# PX4FMUv2_4_6.net
KiCad netlist of a schematic drawn in EAGLE
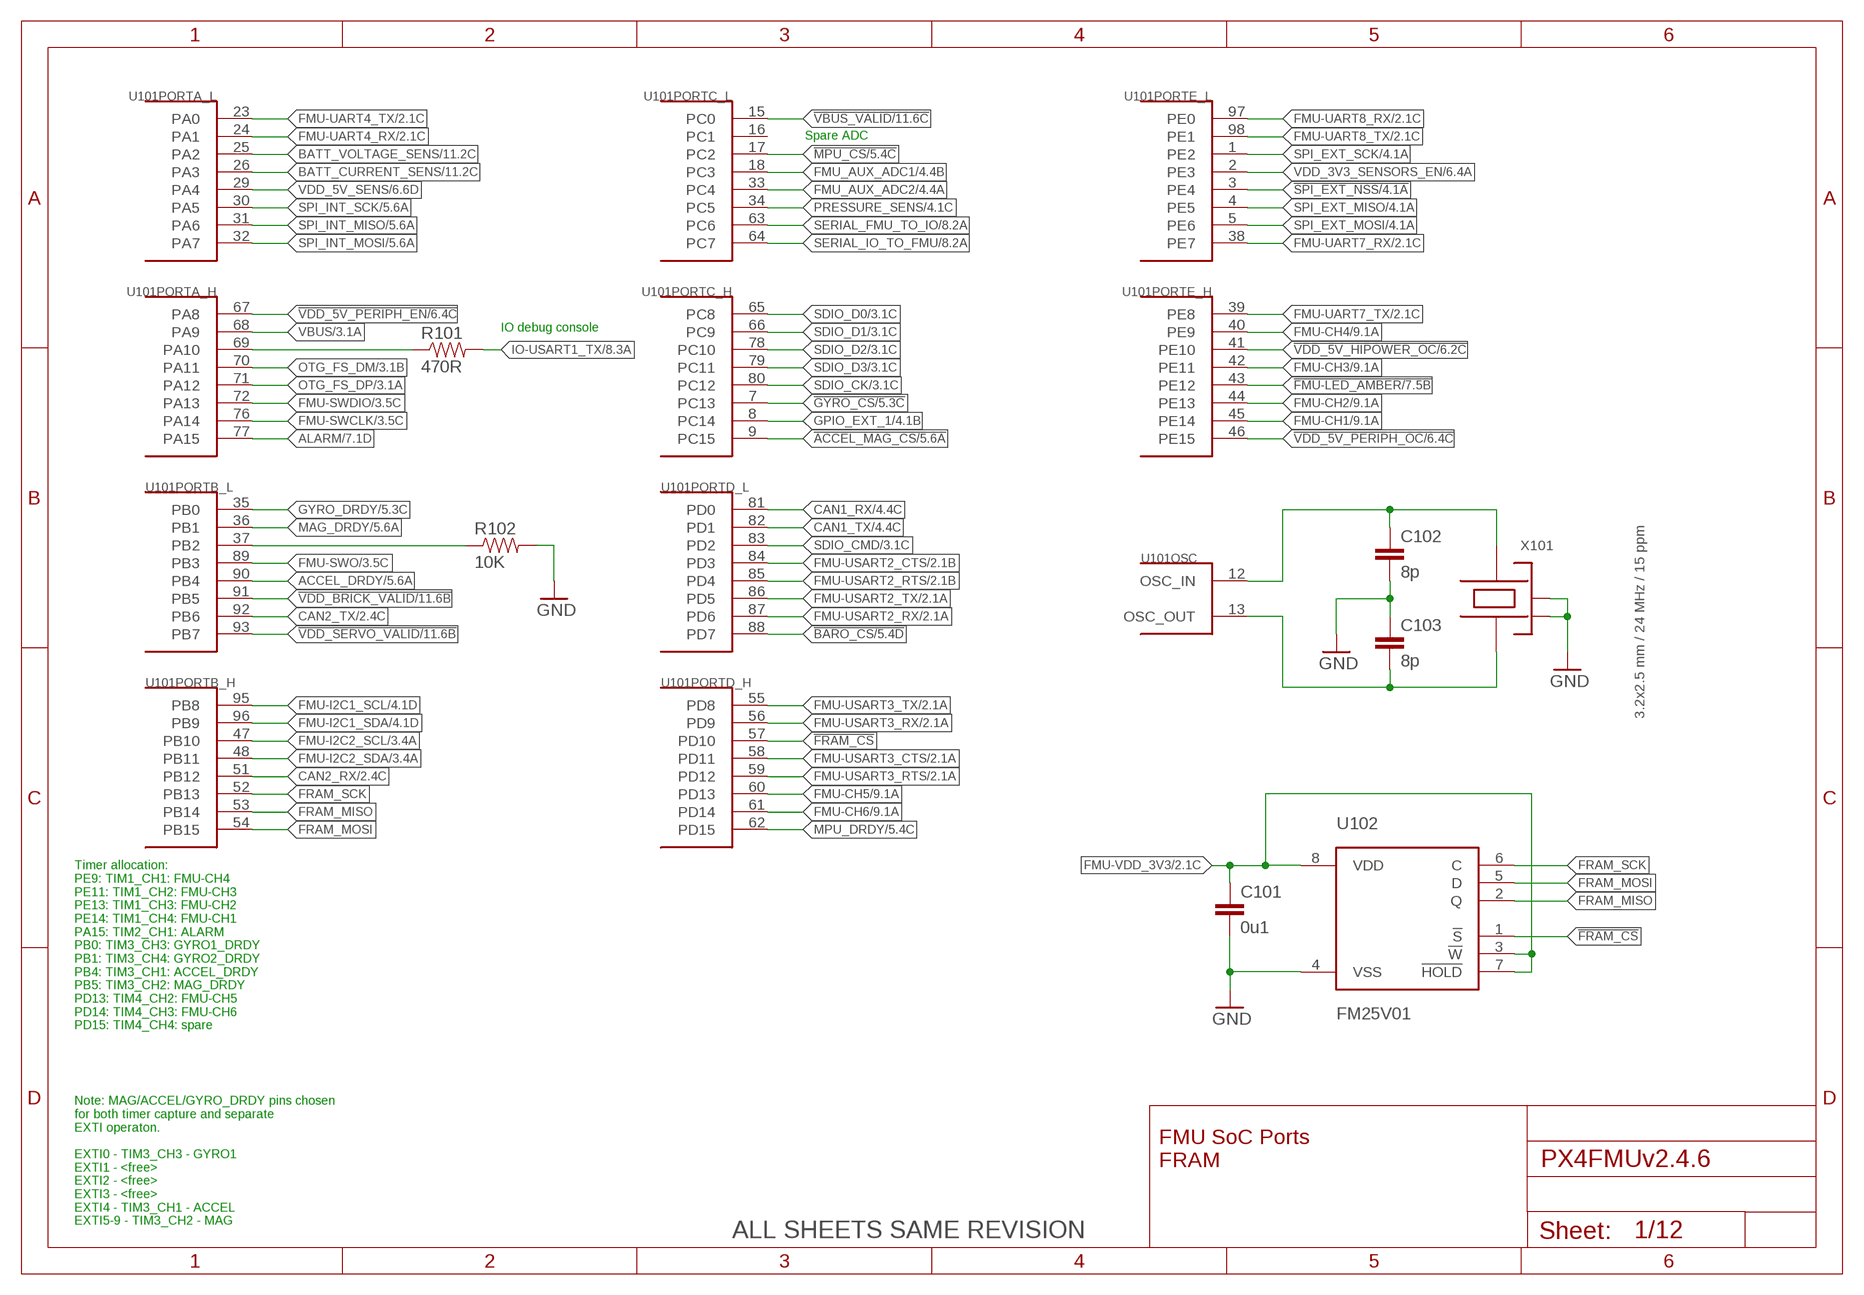
[diagram p0: schematic, sheet 1]
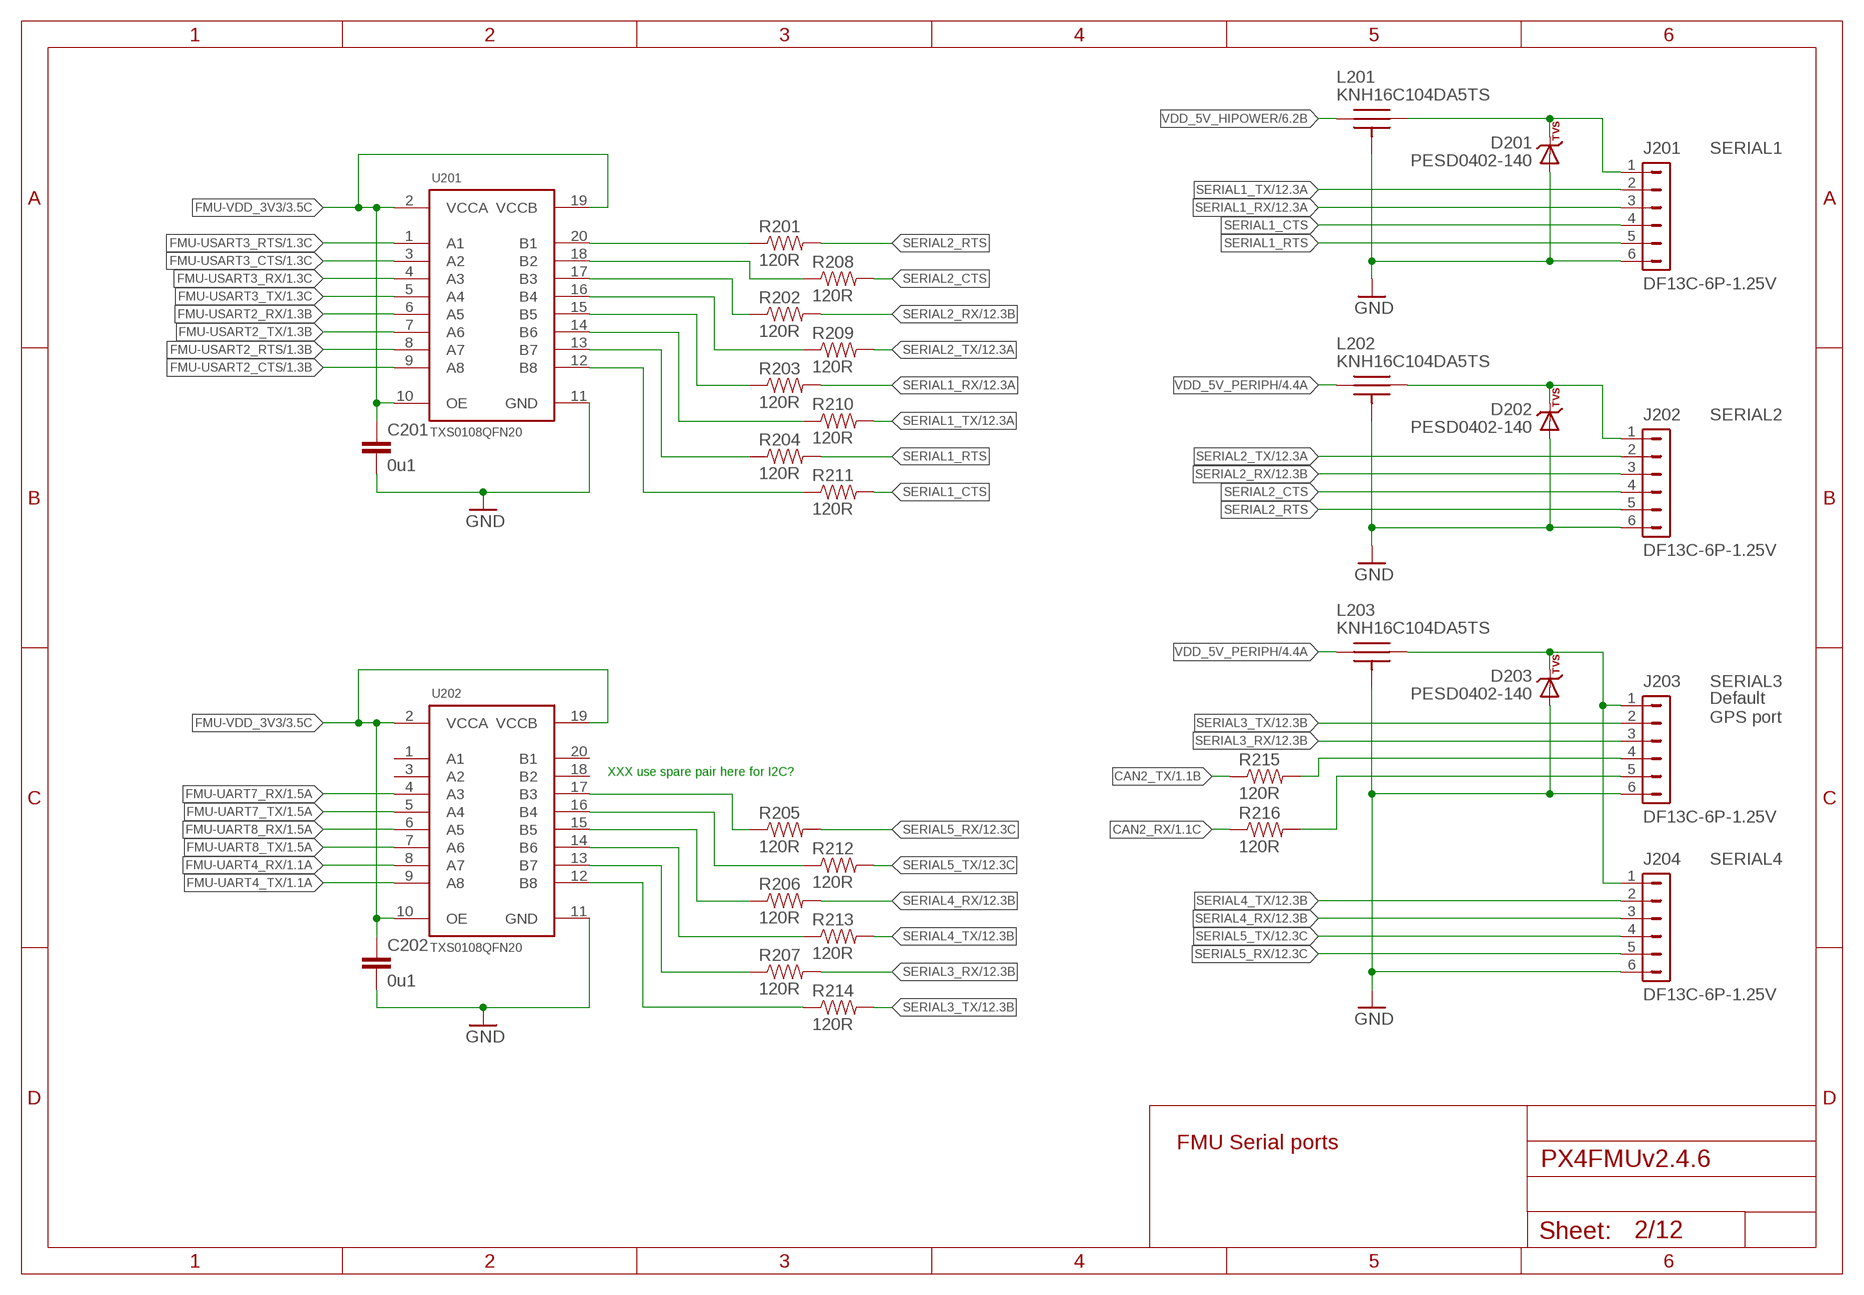
[diagram p1: schematic, sheet 2]
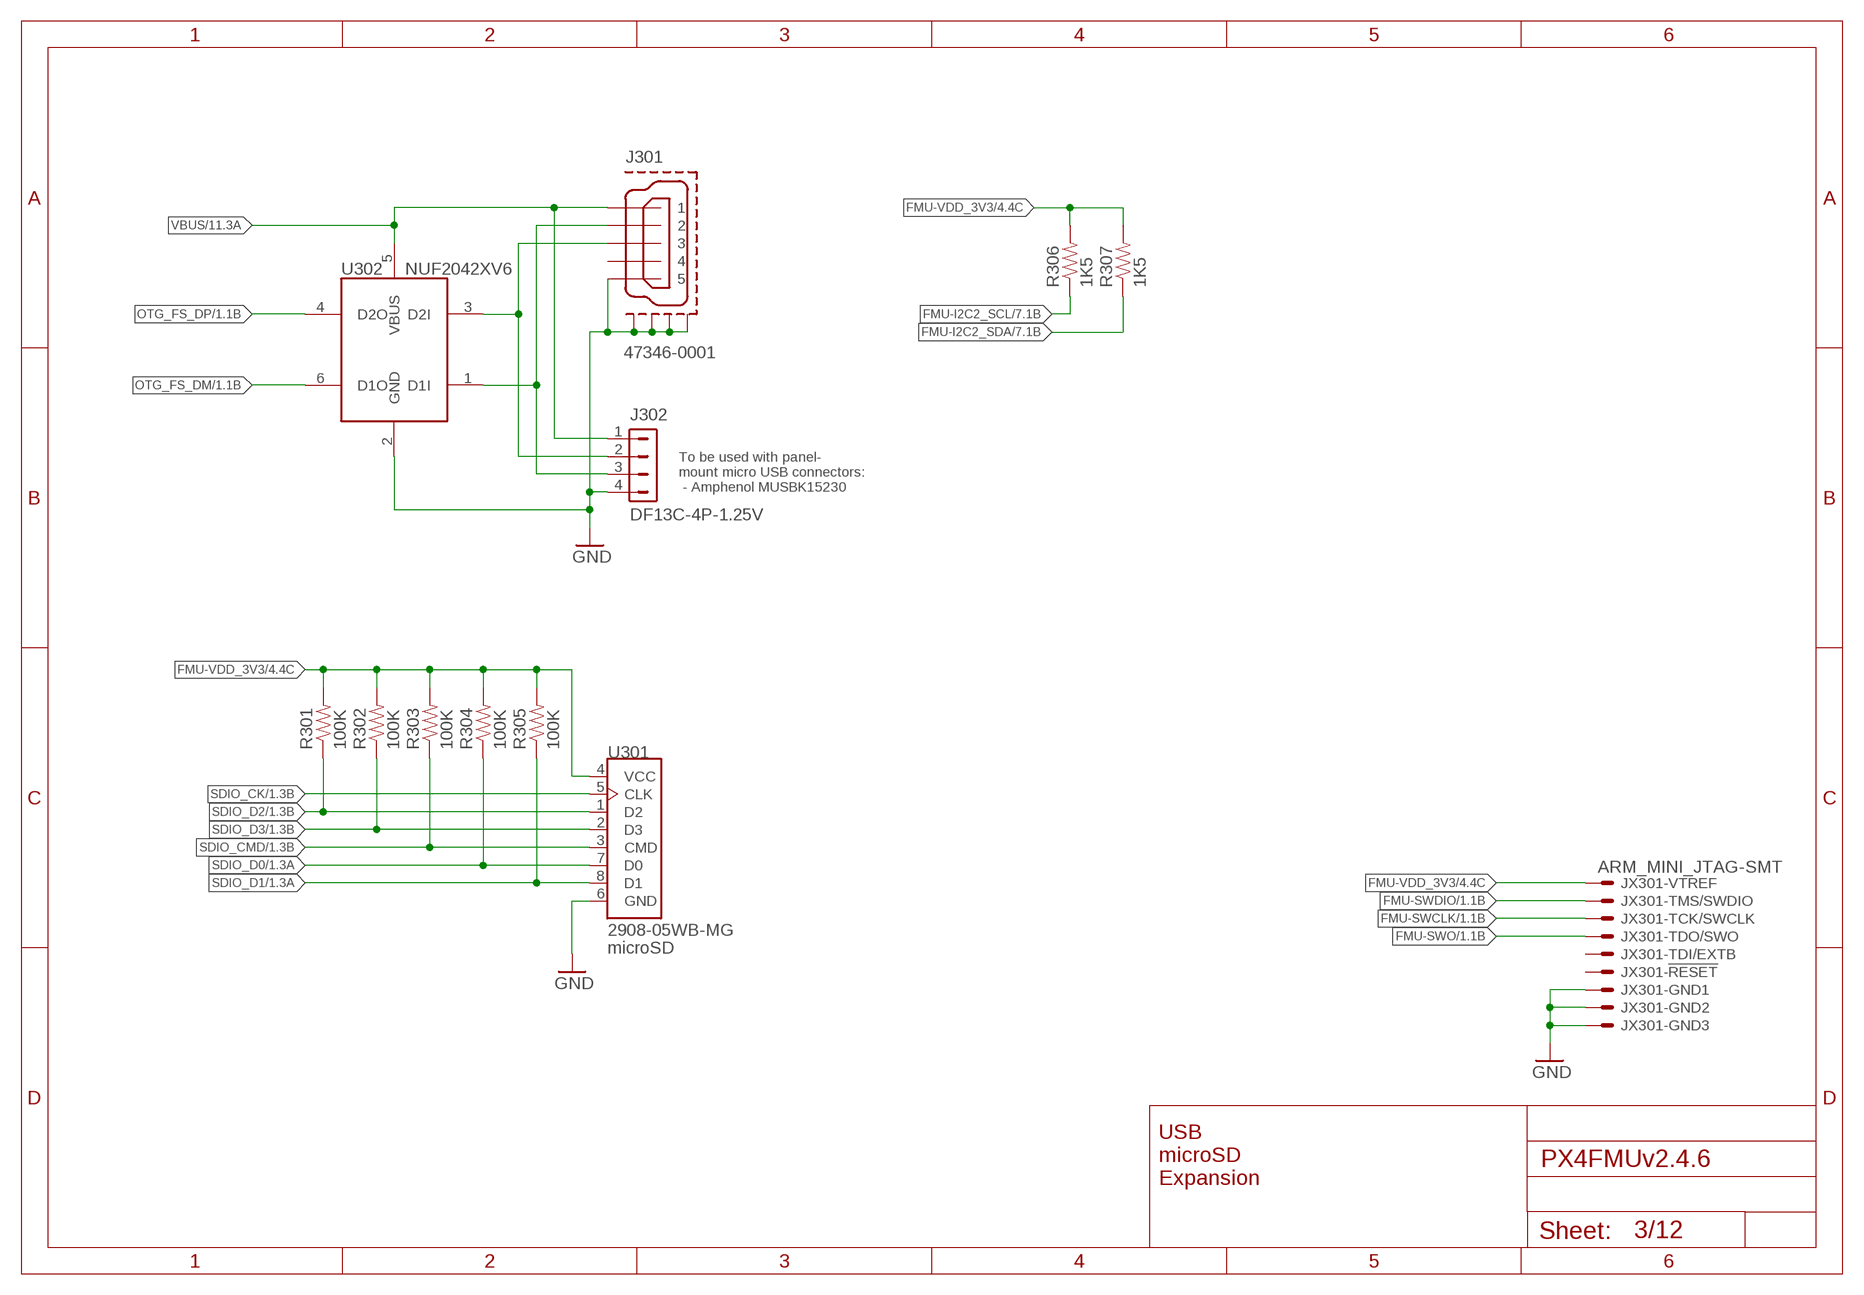
[diagram p2: schematic, sheet 3]
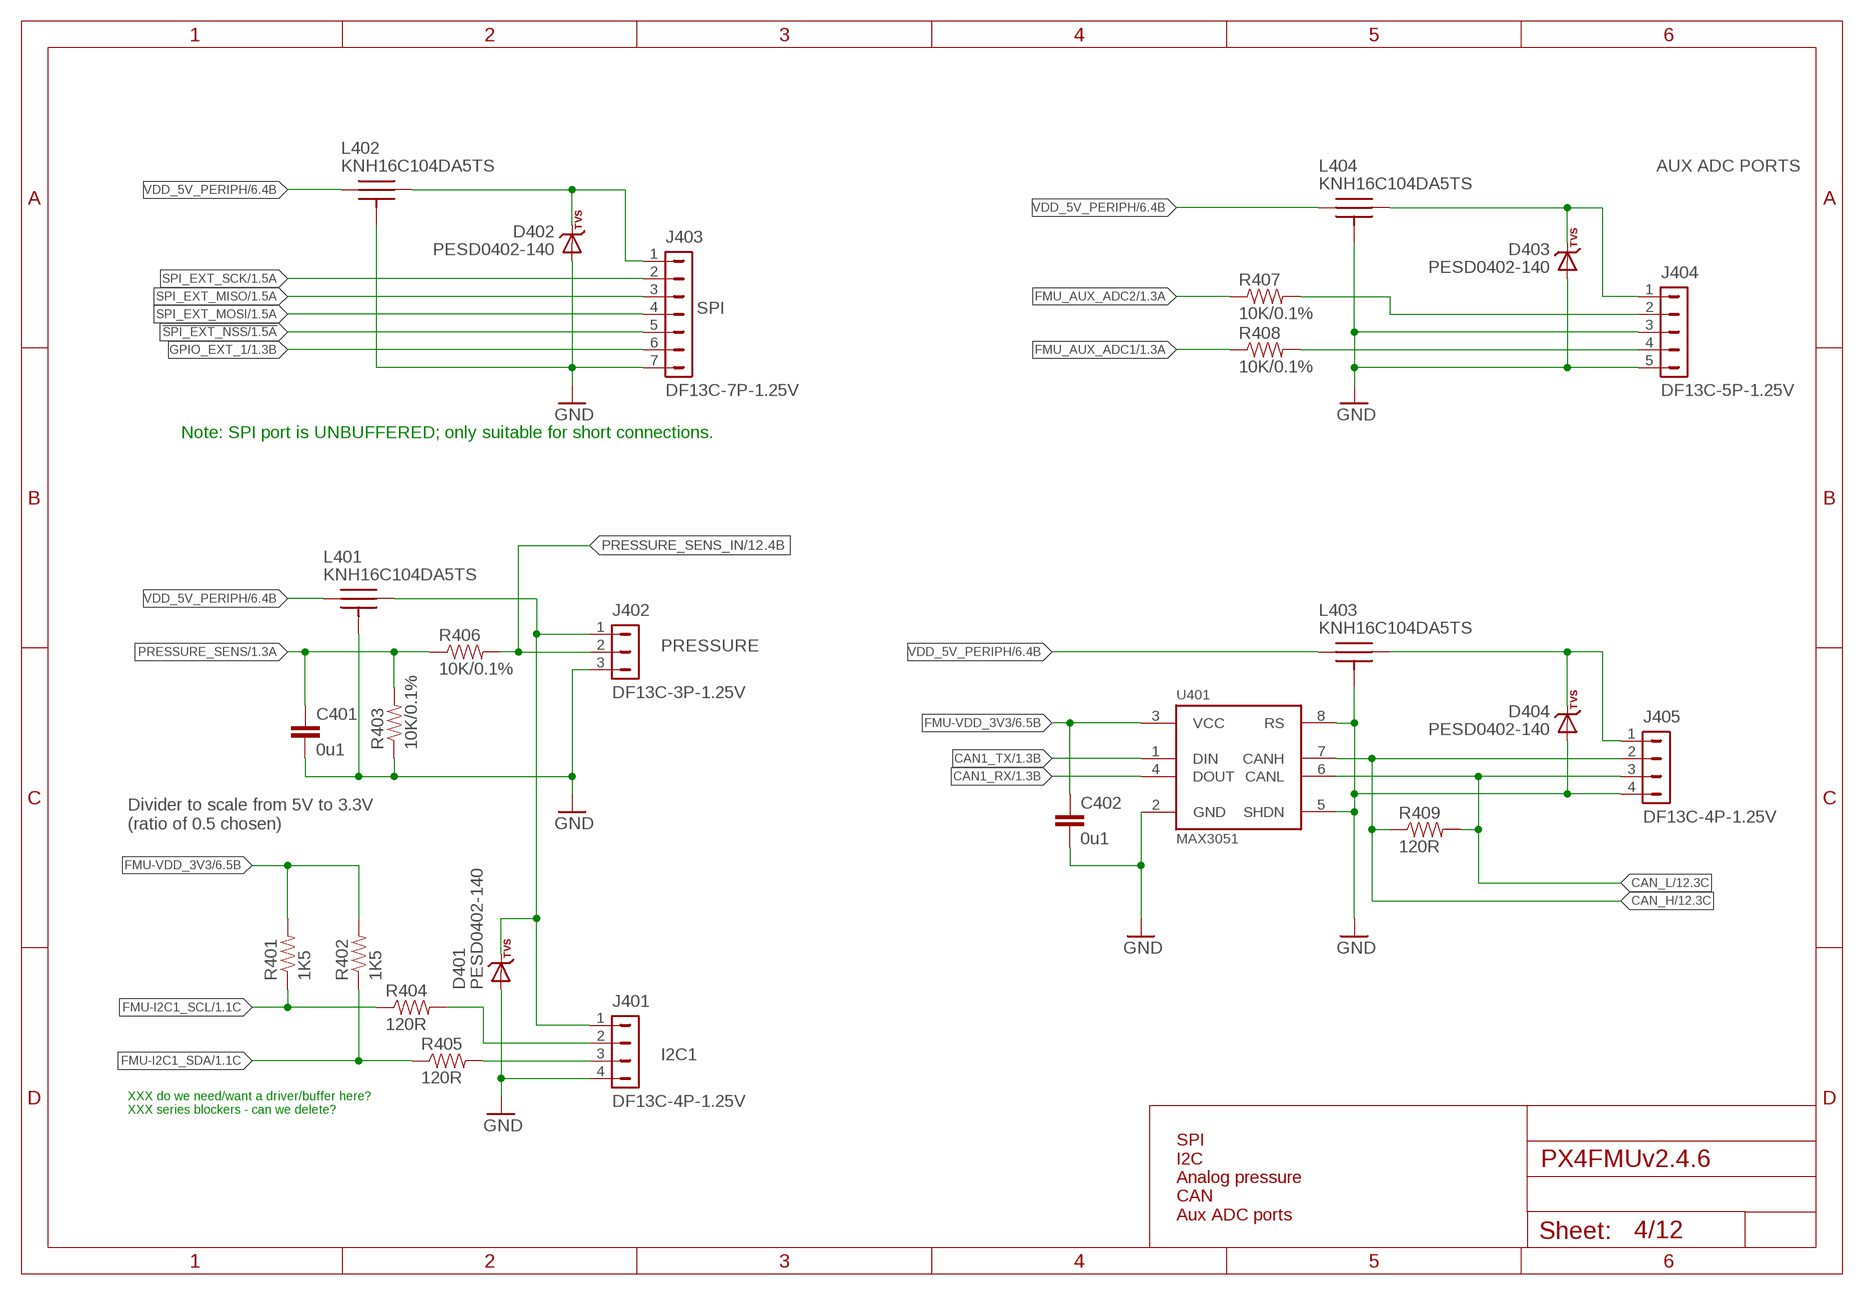
[diagram p3: schematic, sheet 4]
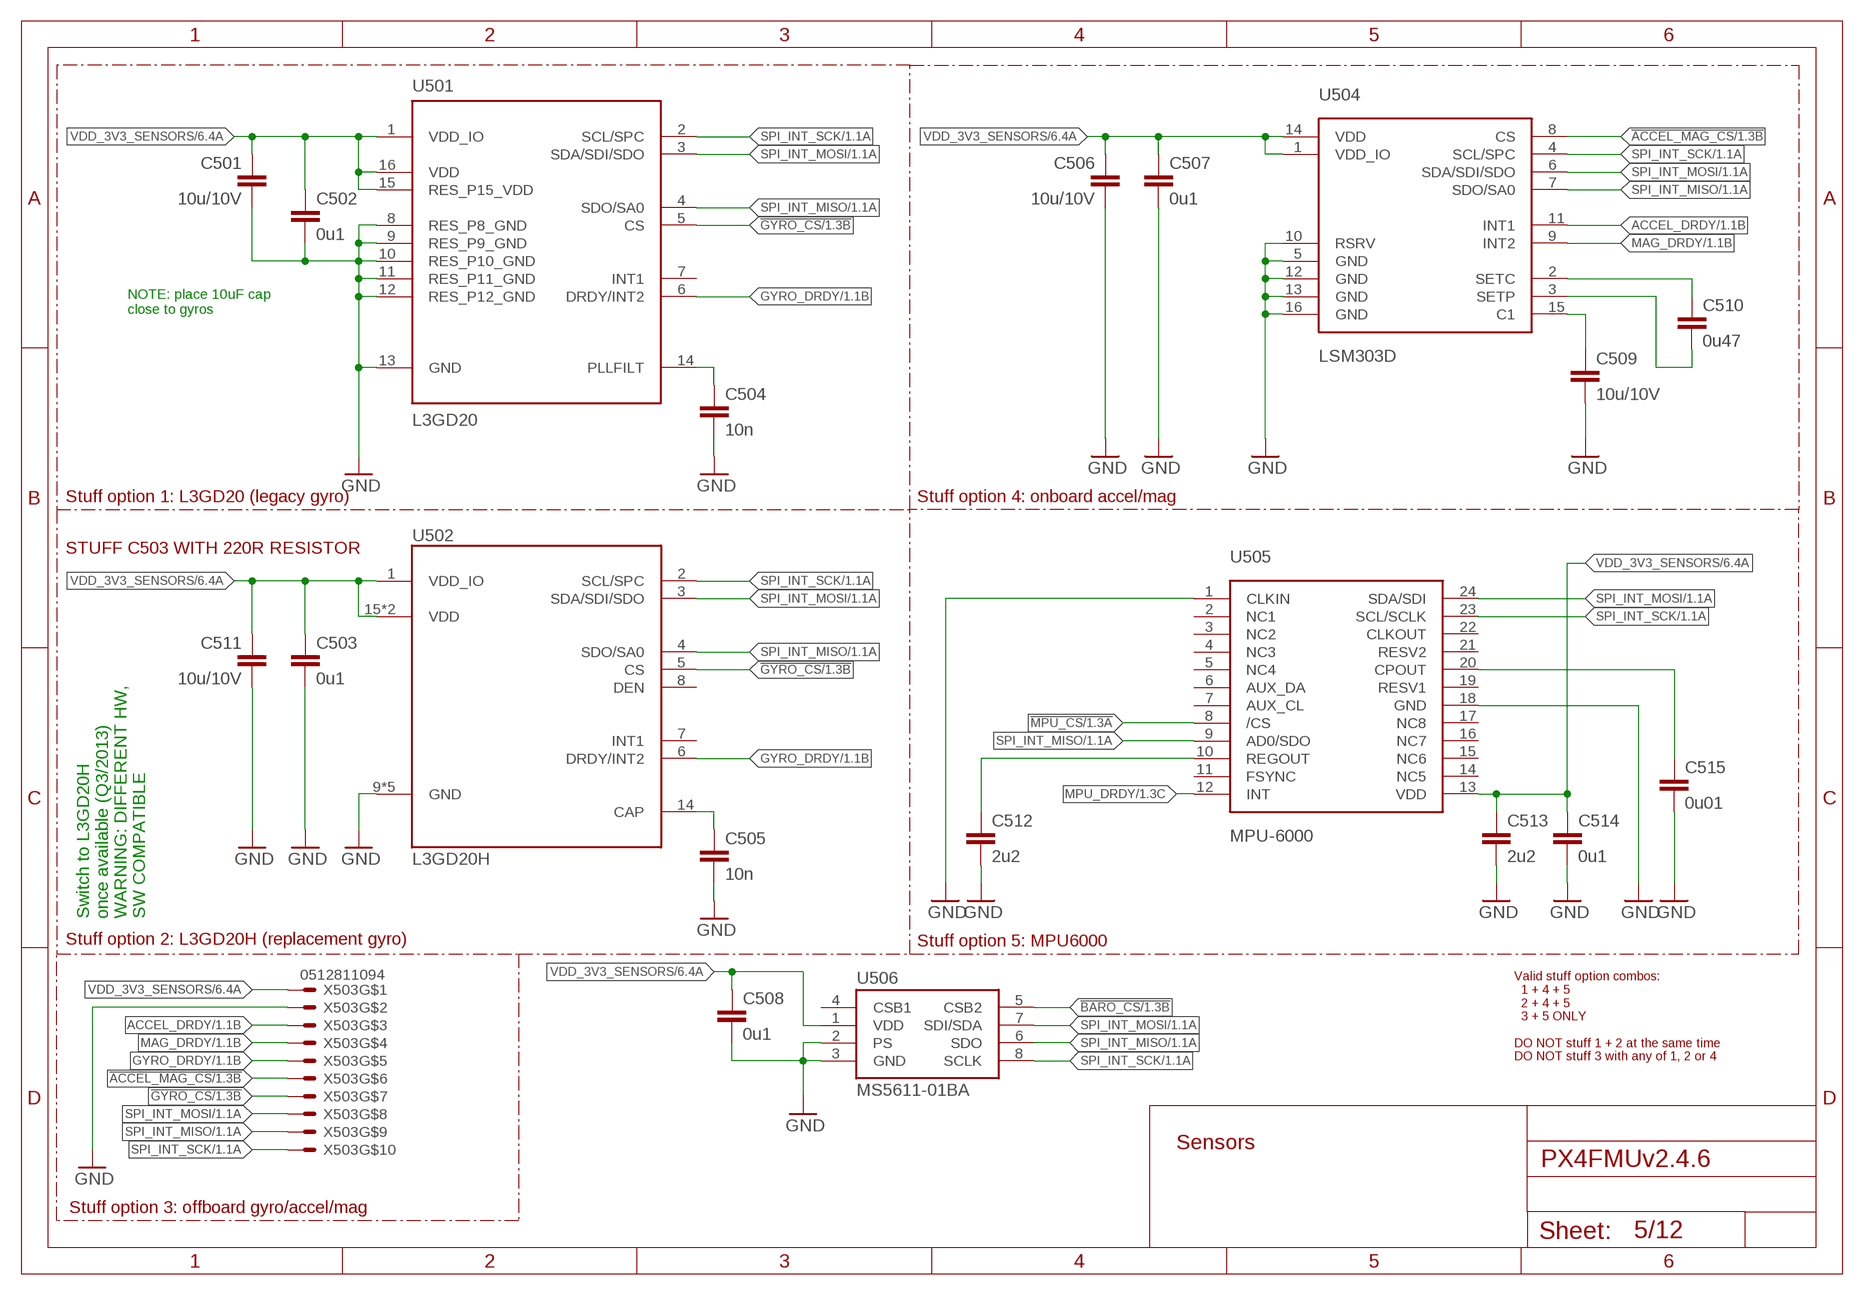
[diagram p4: schematic, sheet 5]
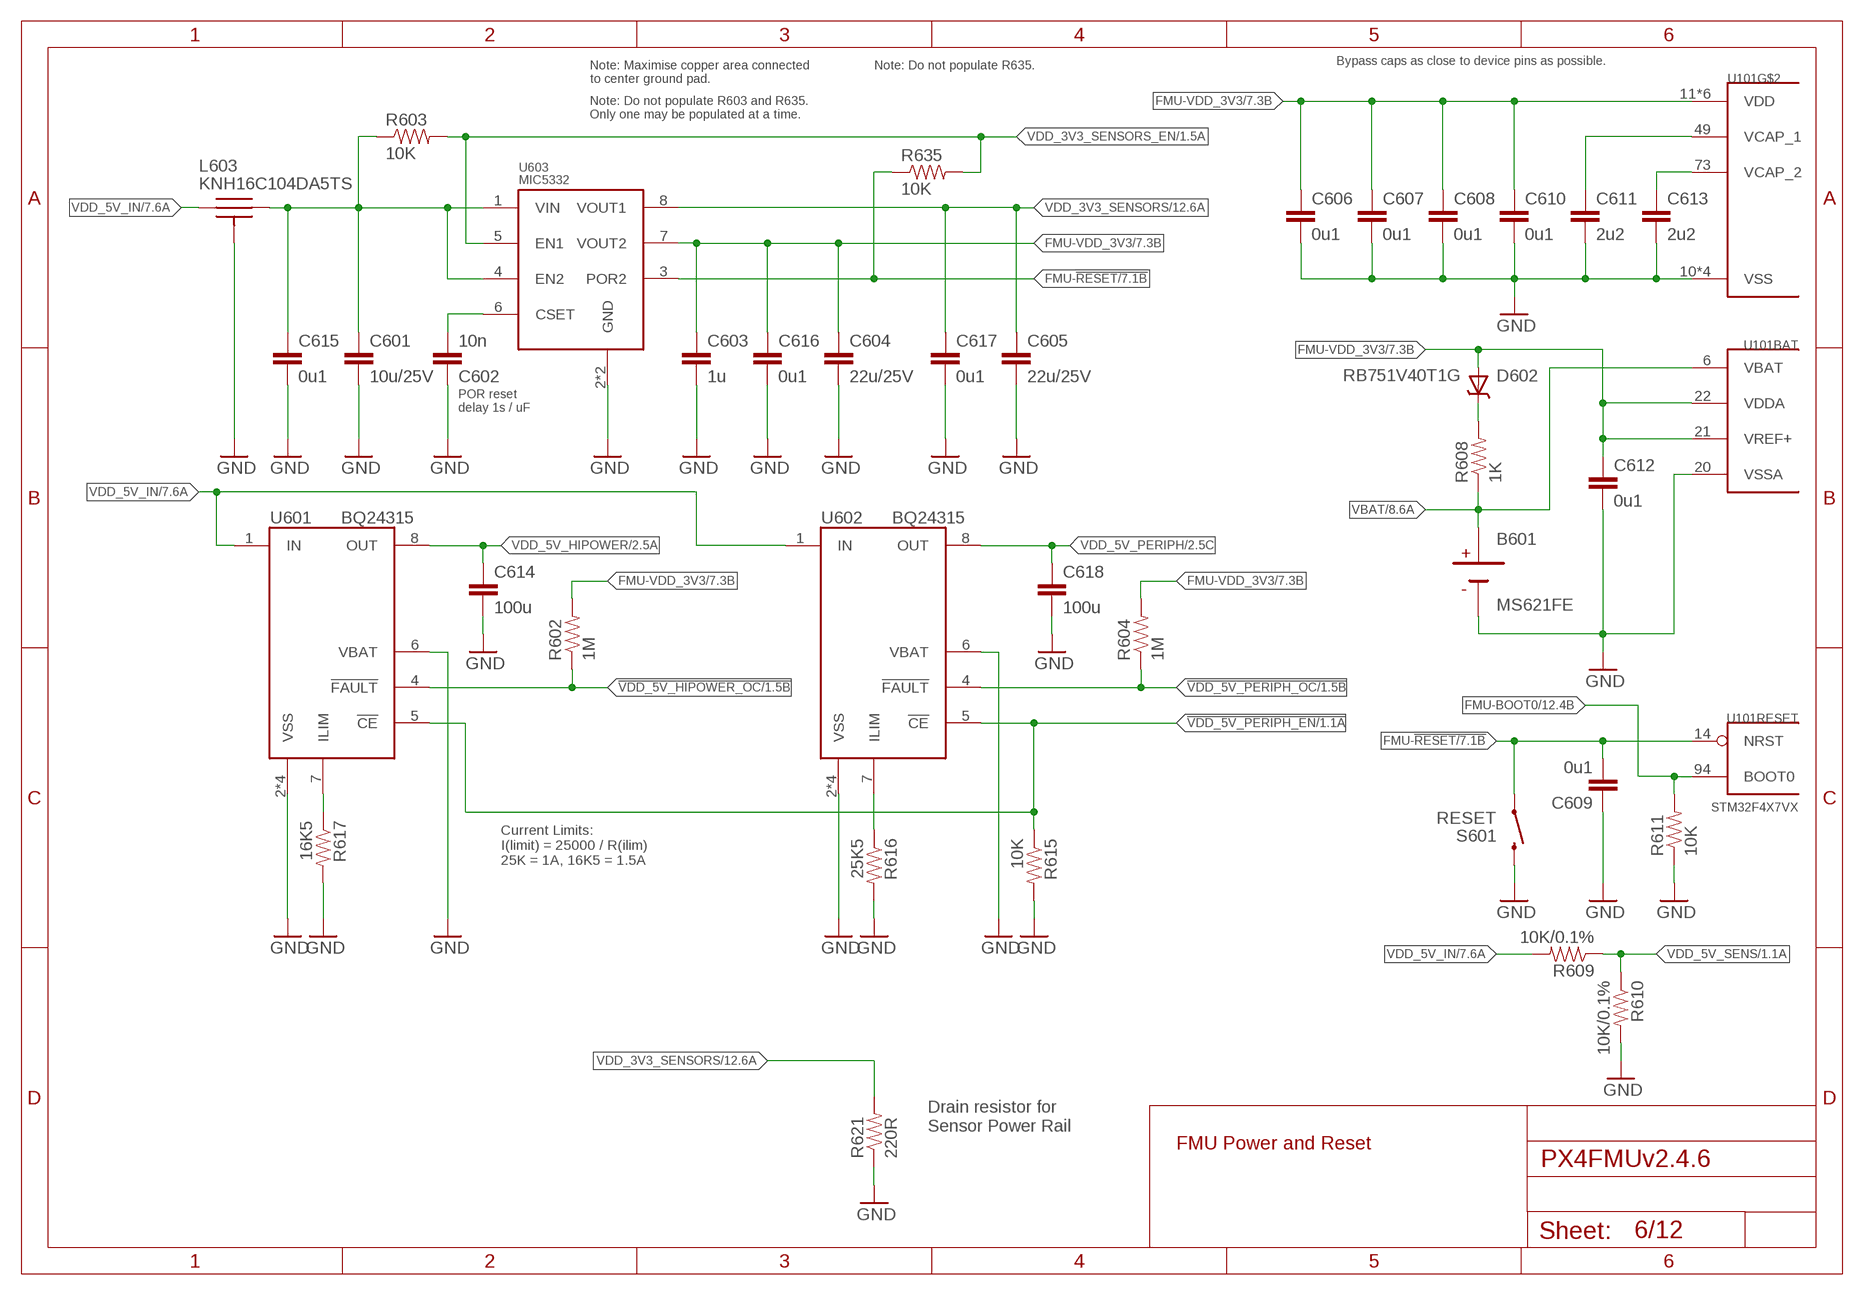
[diagram p5: schematic, sheet 6]
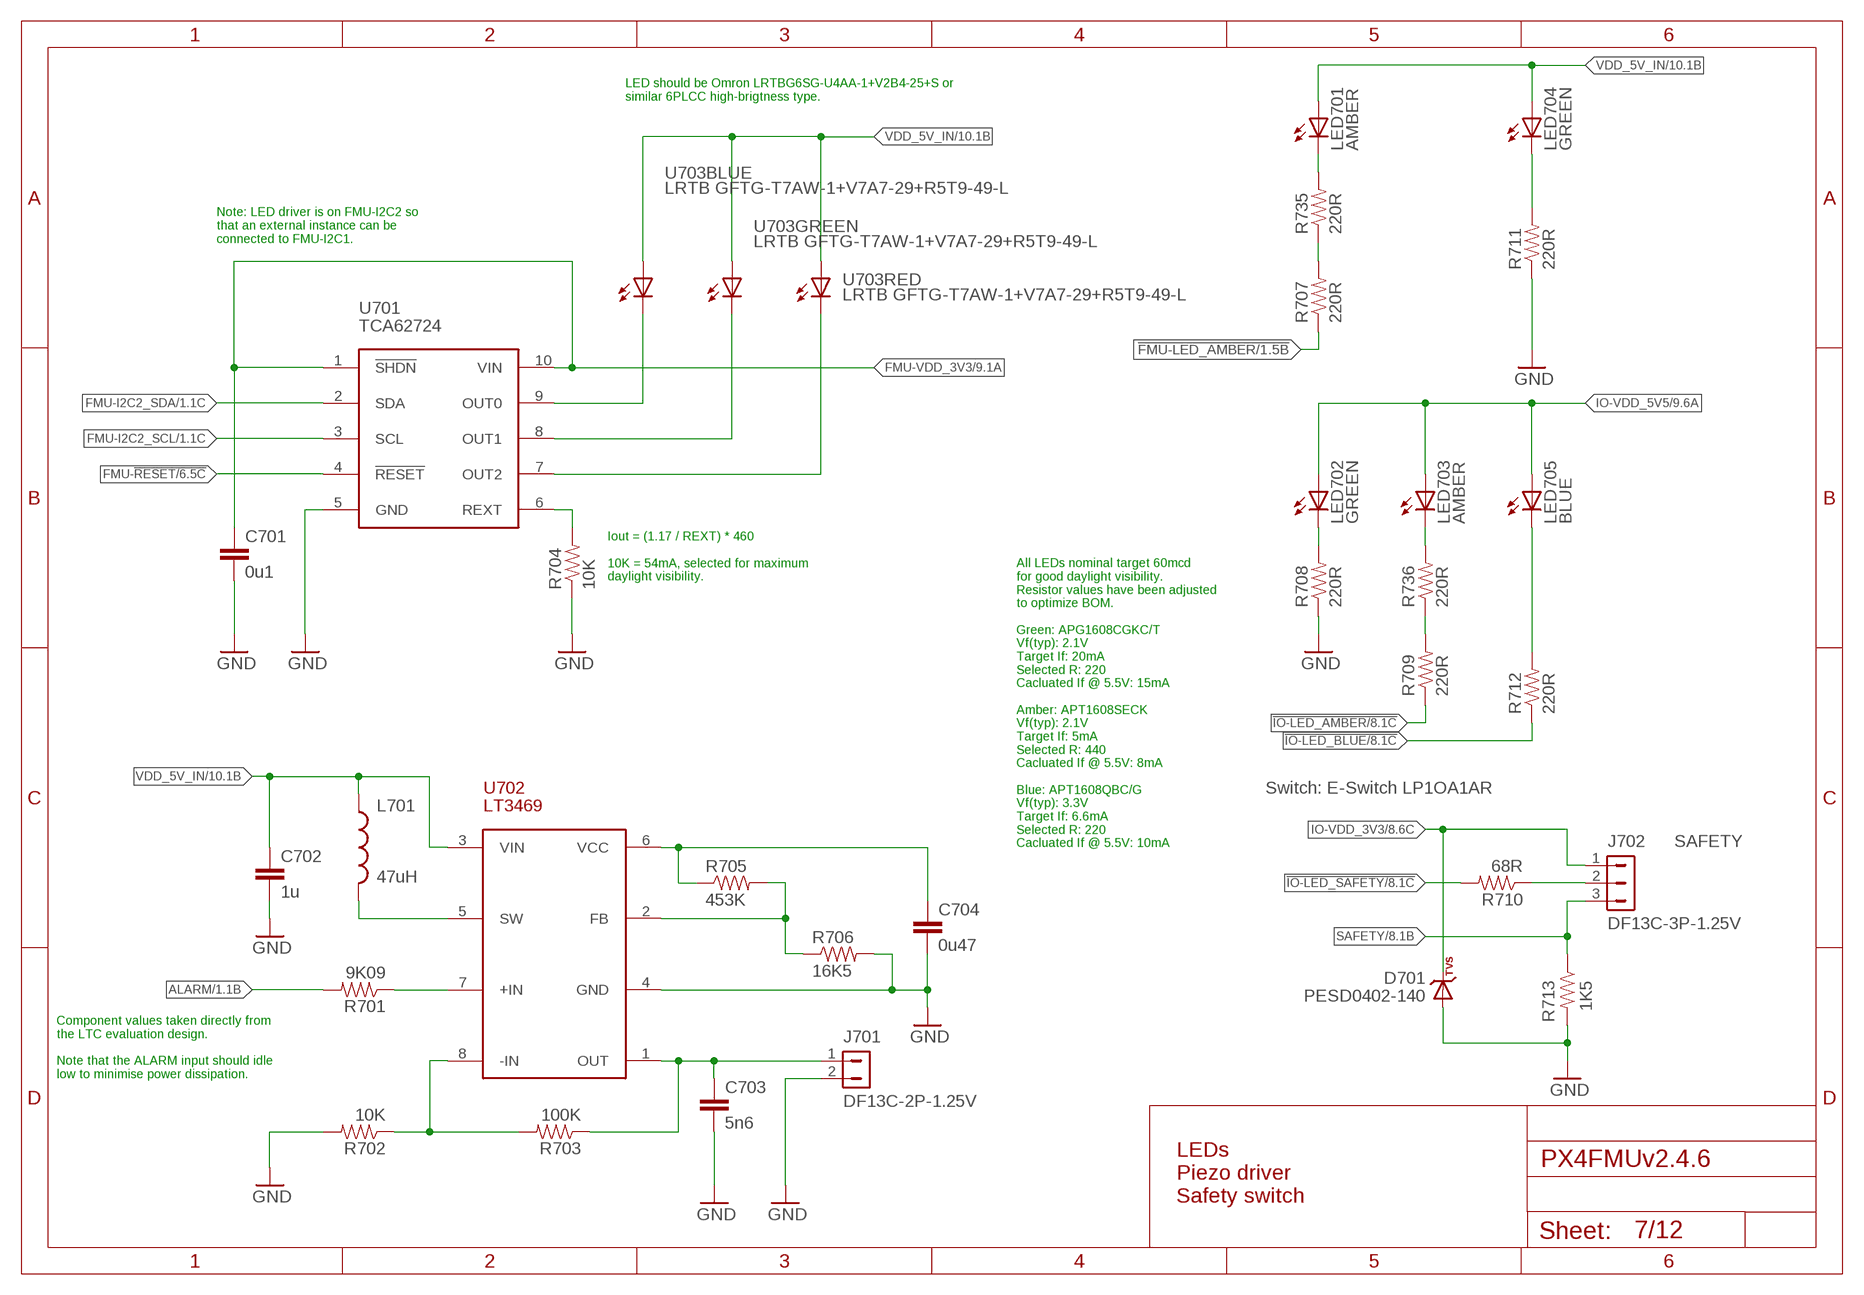
[diagram p6: schematic, sheet 7]
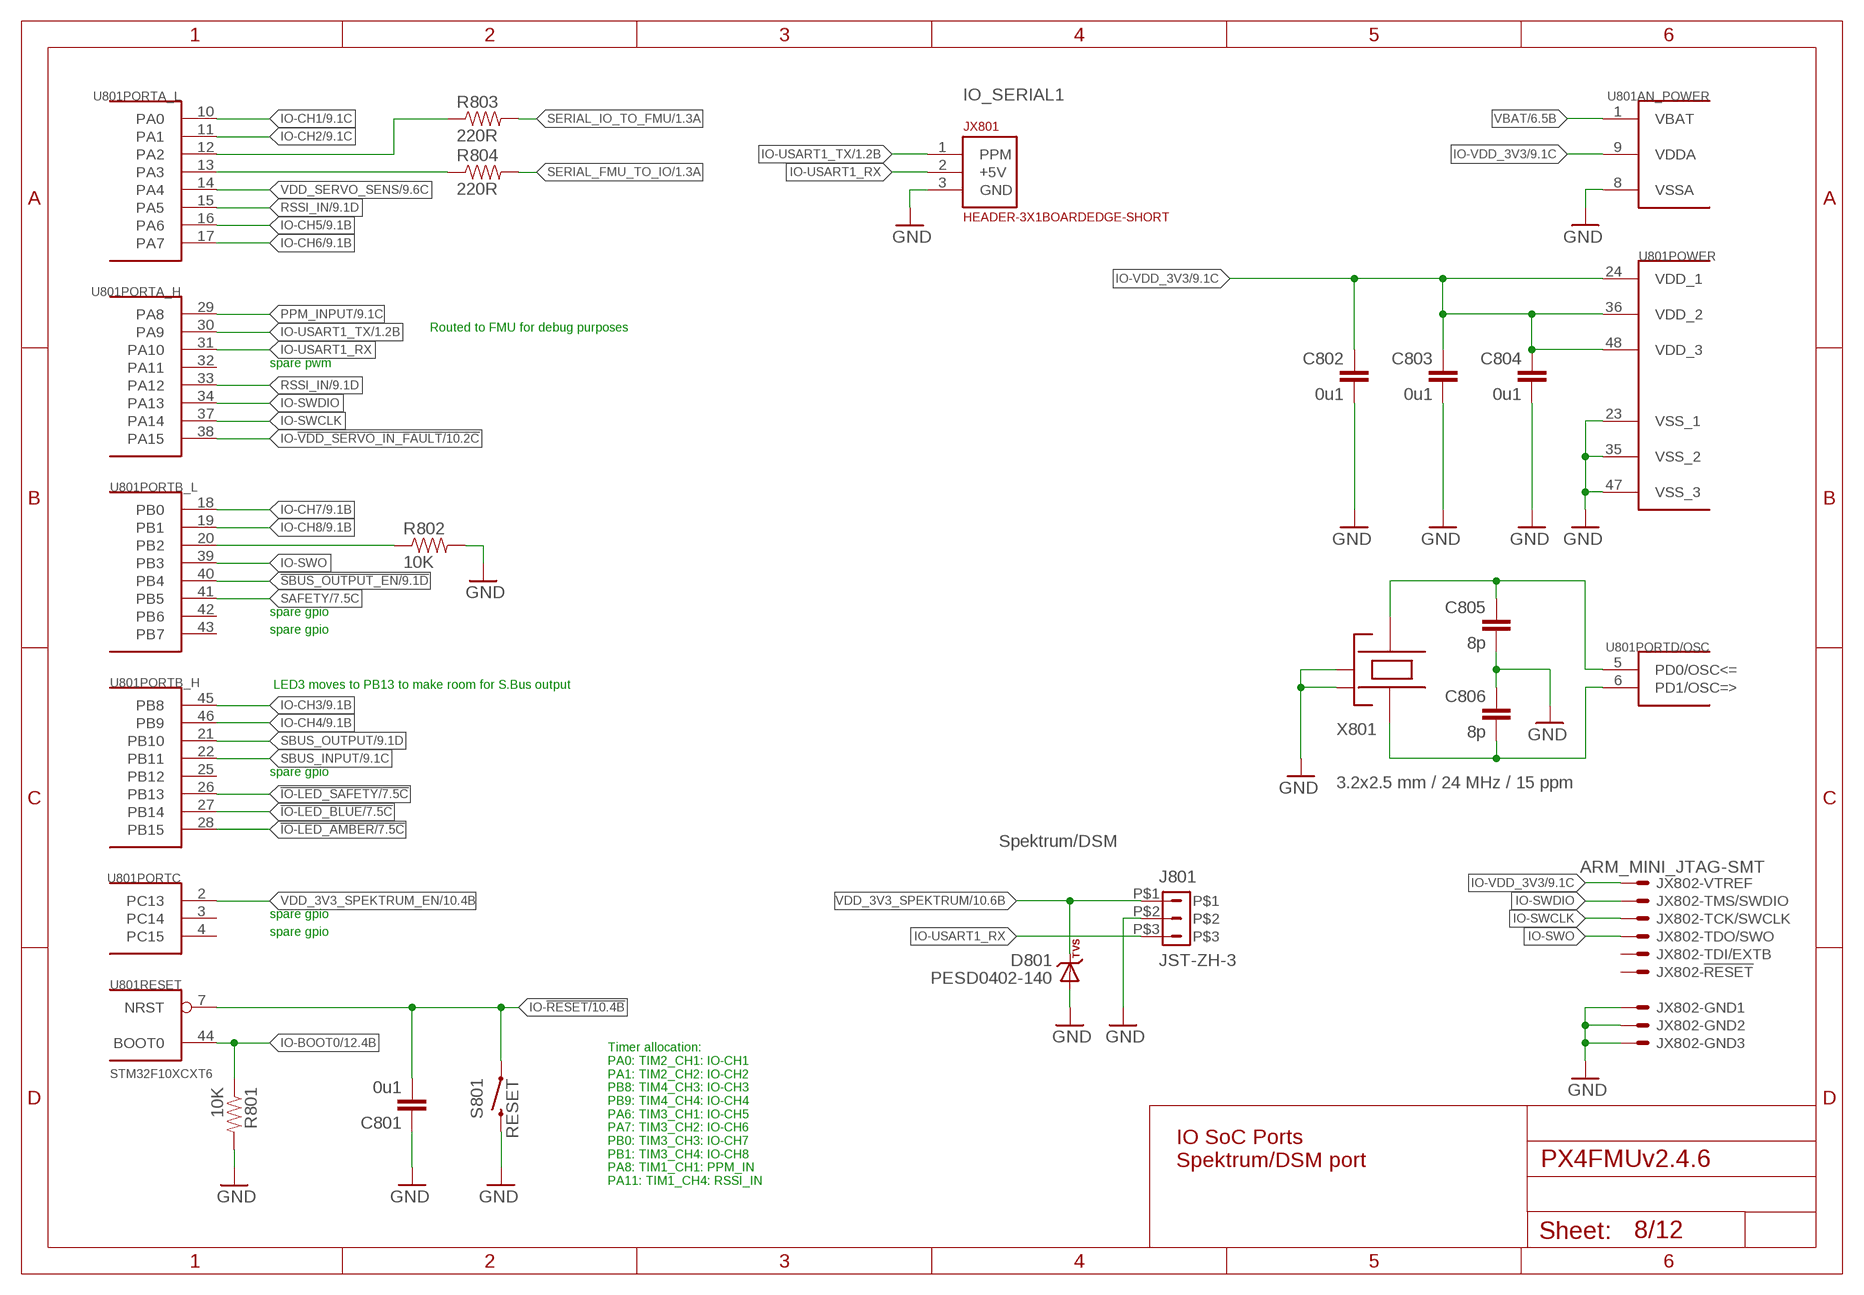
[diagram p7: schematic, sheet 8]
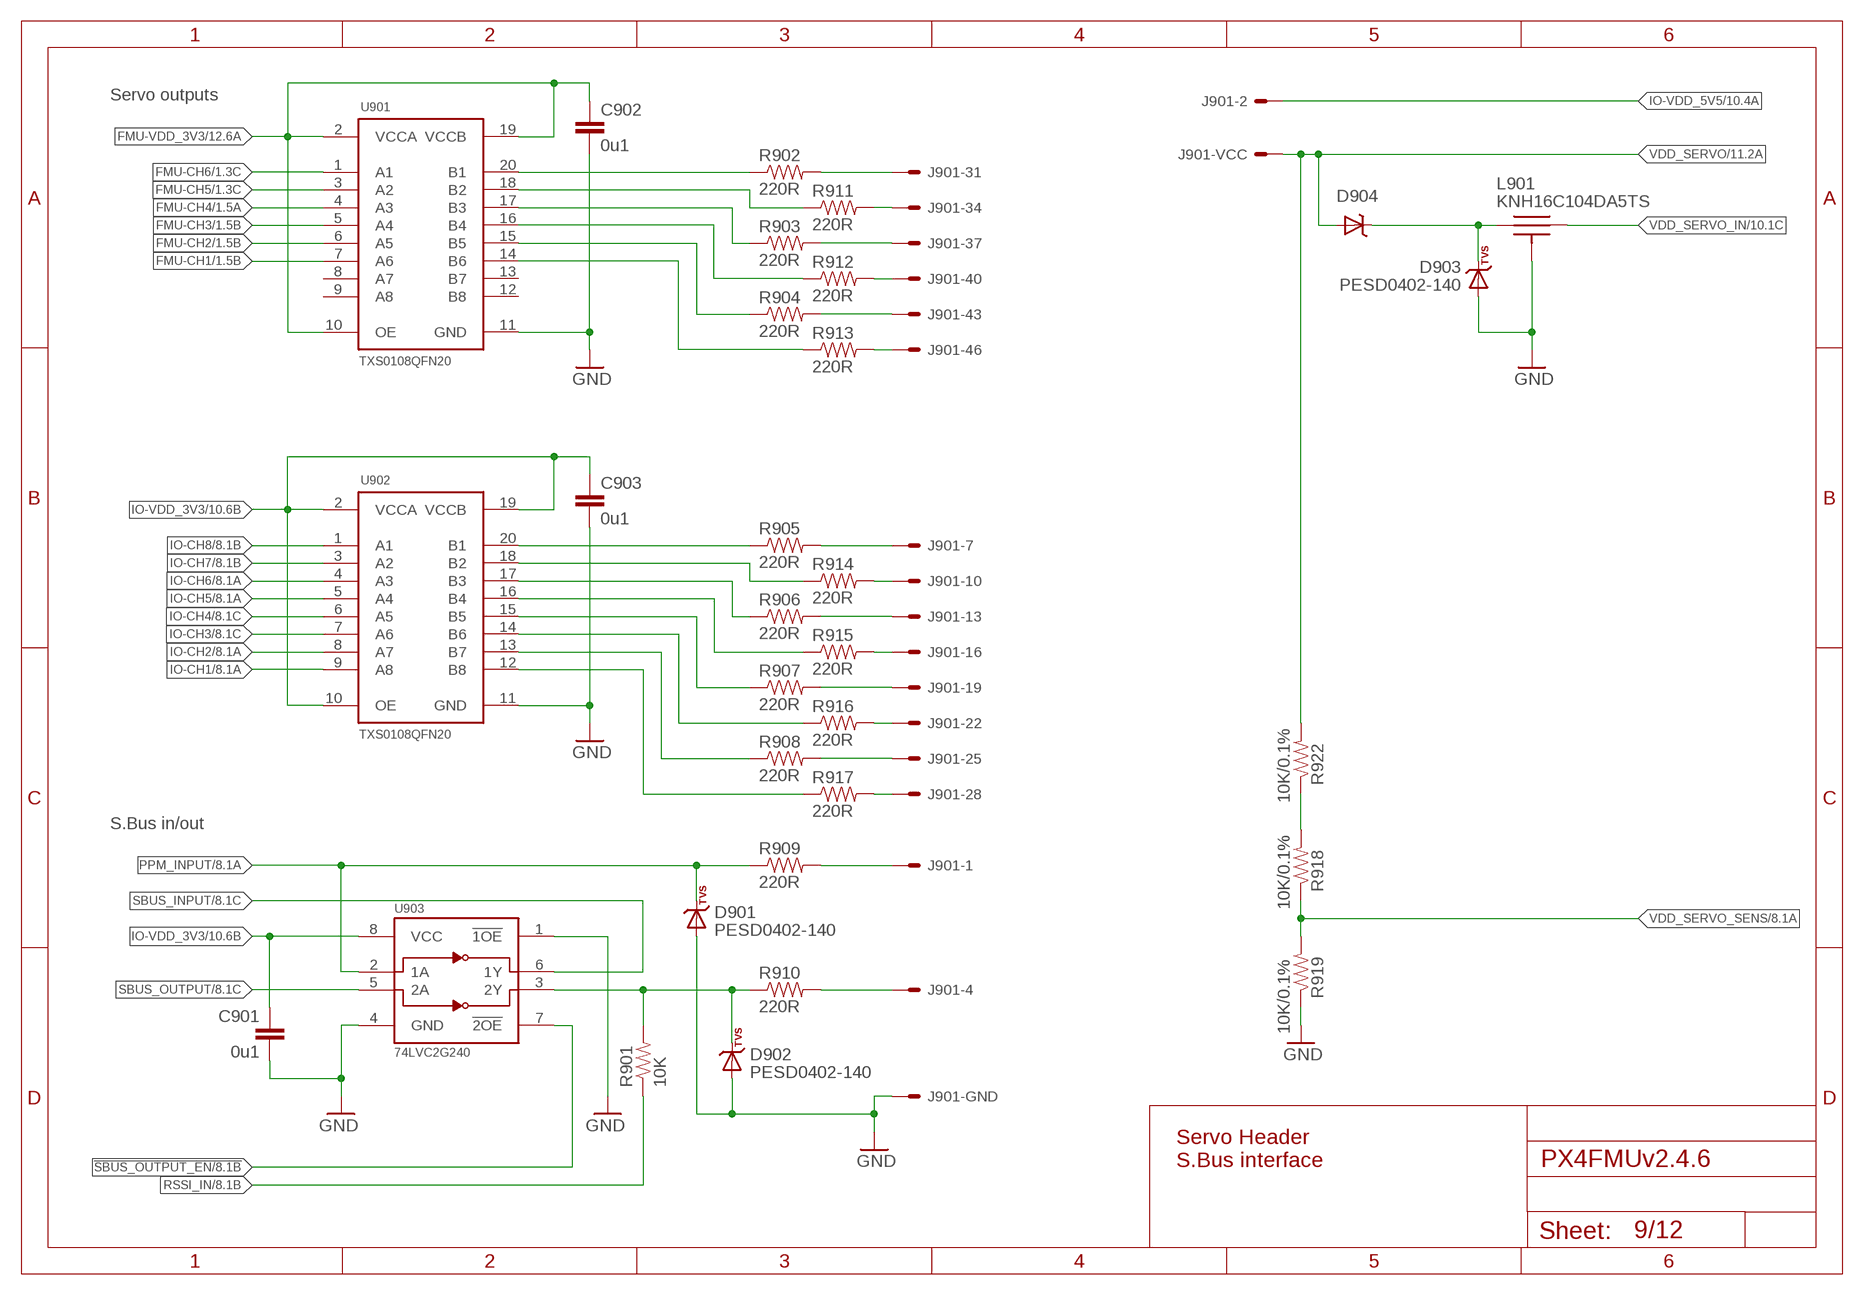
[diagram p8: schematic, sheet 9]
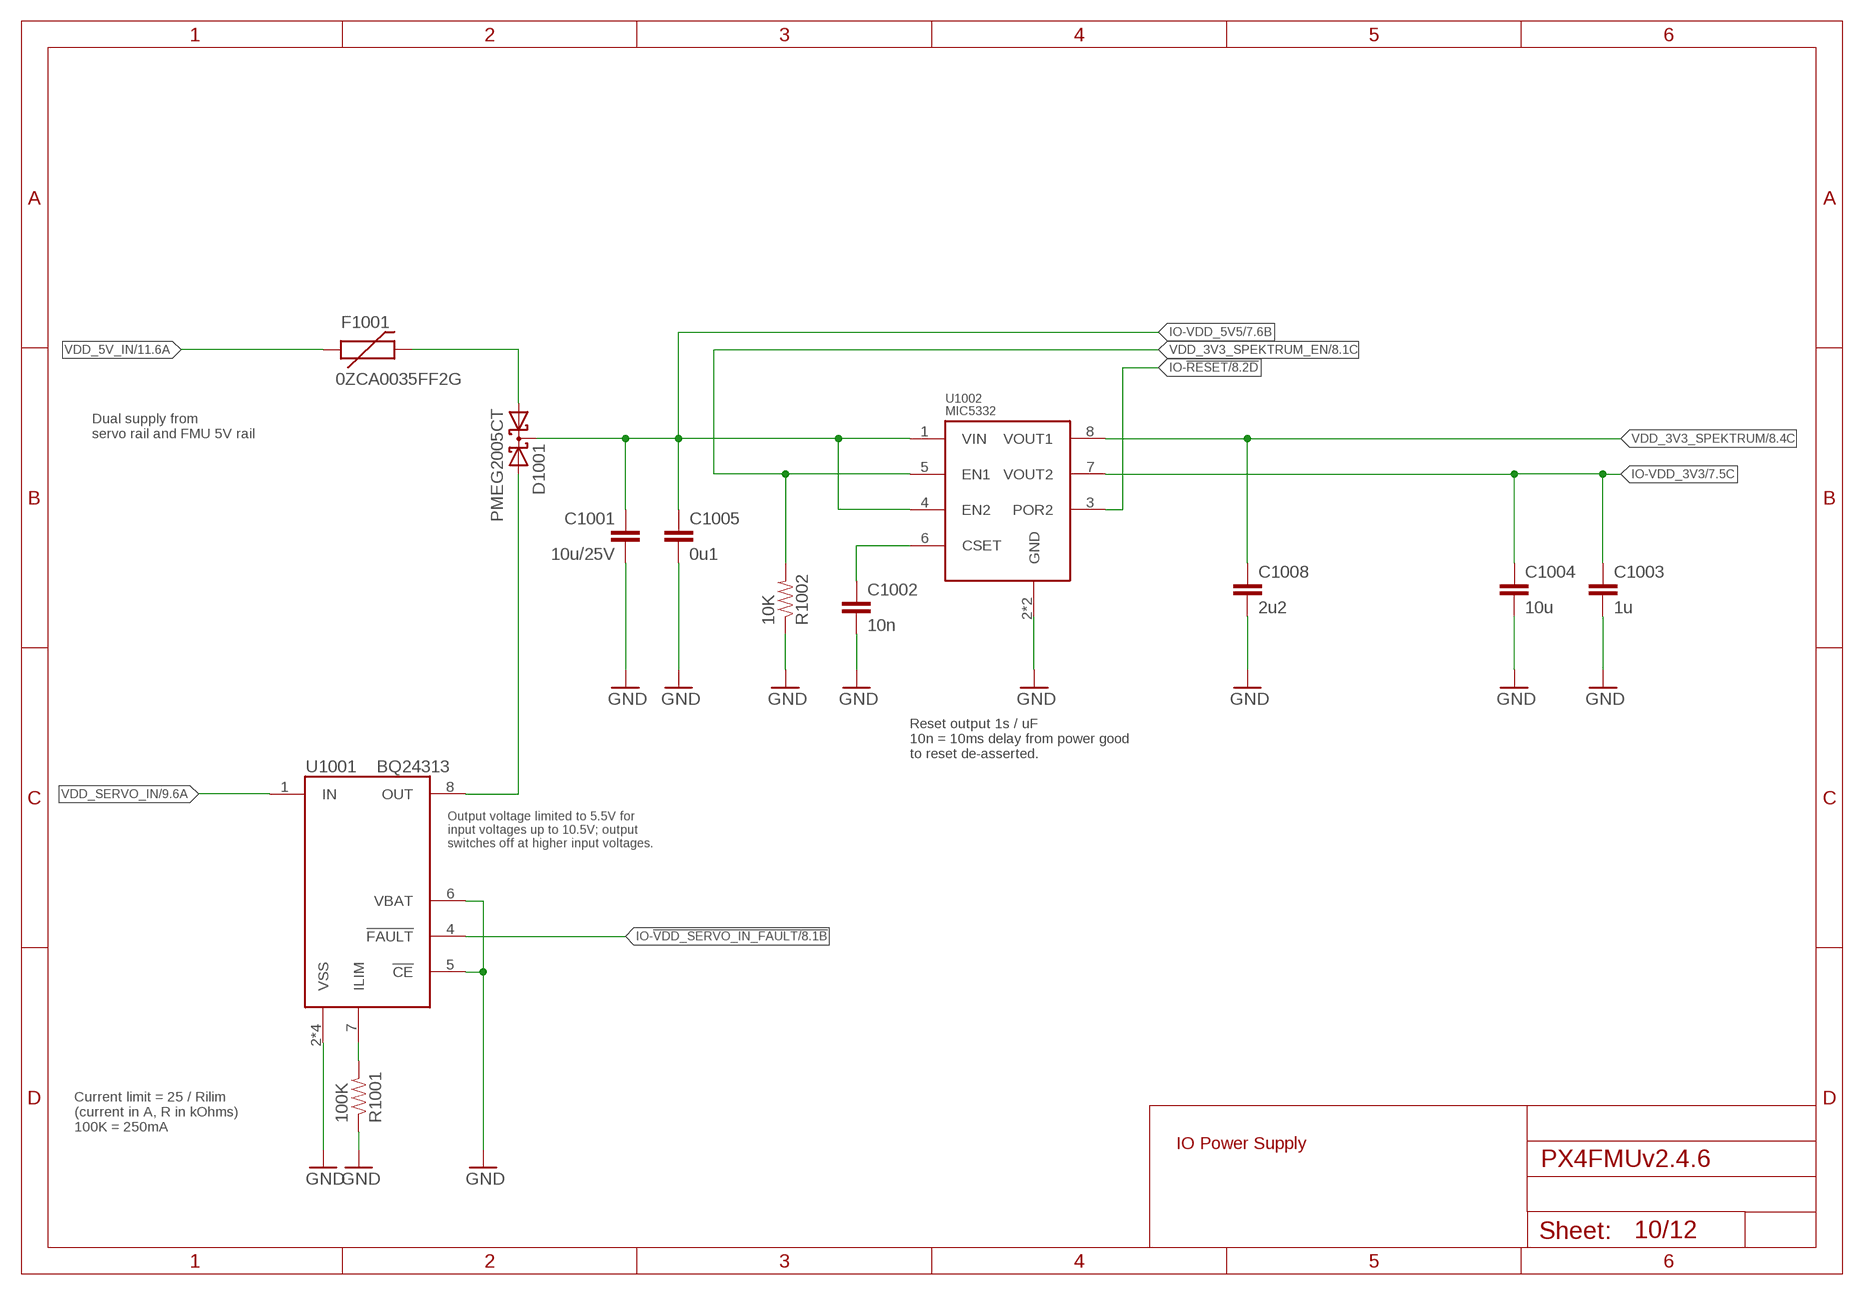
[diagram p9: schematic, sheet 10]
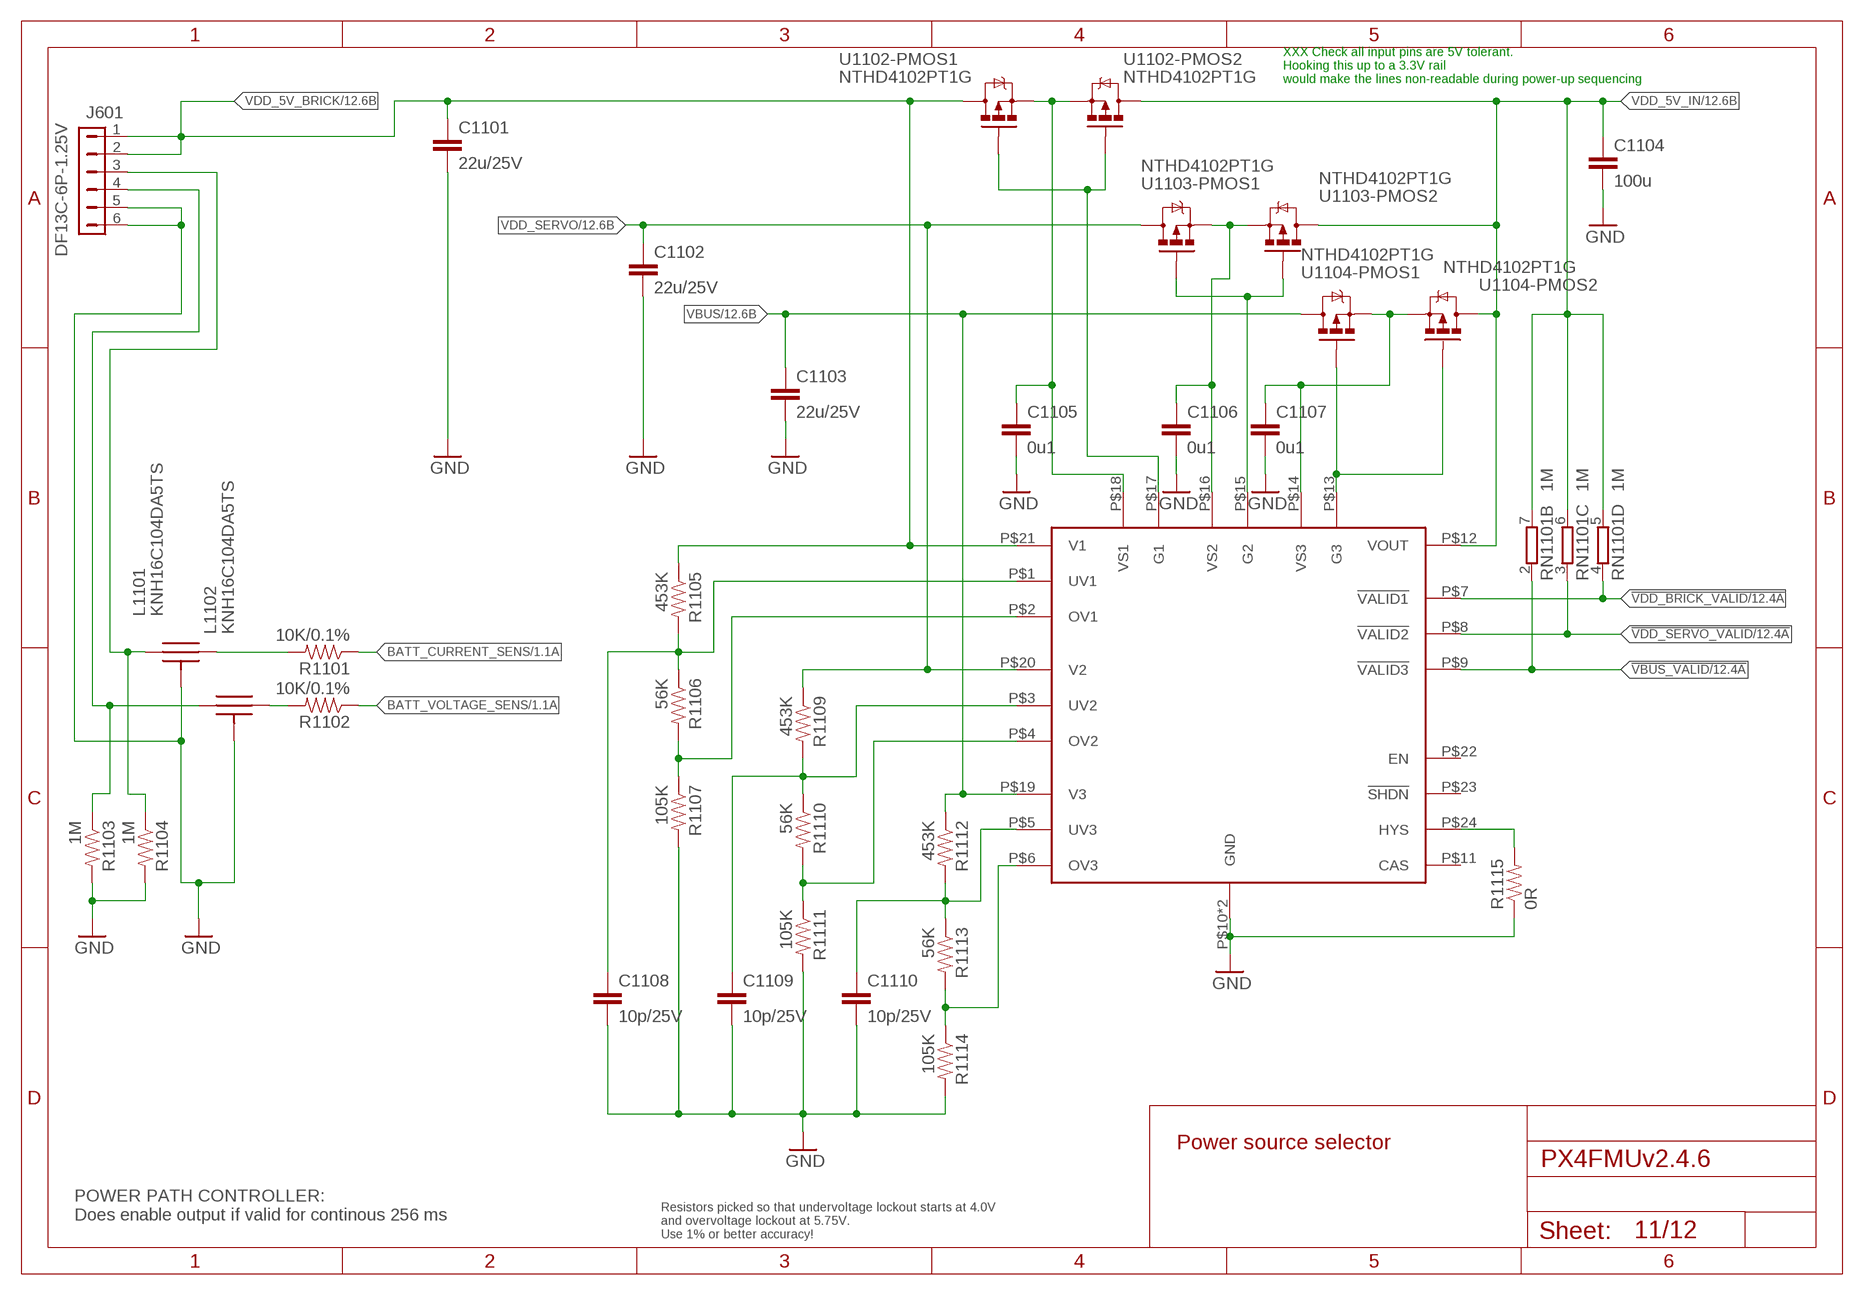
[diagram p10: schematic, sheet 11]
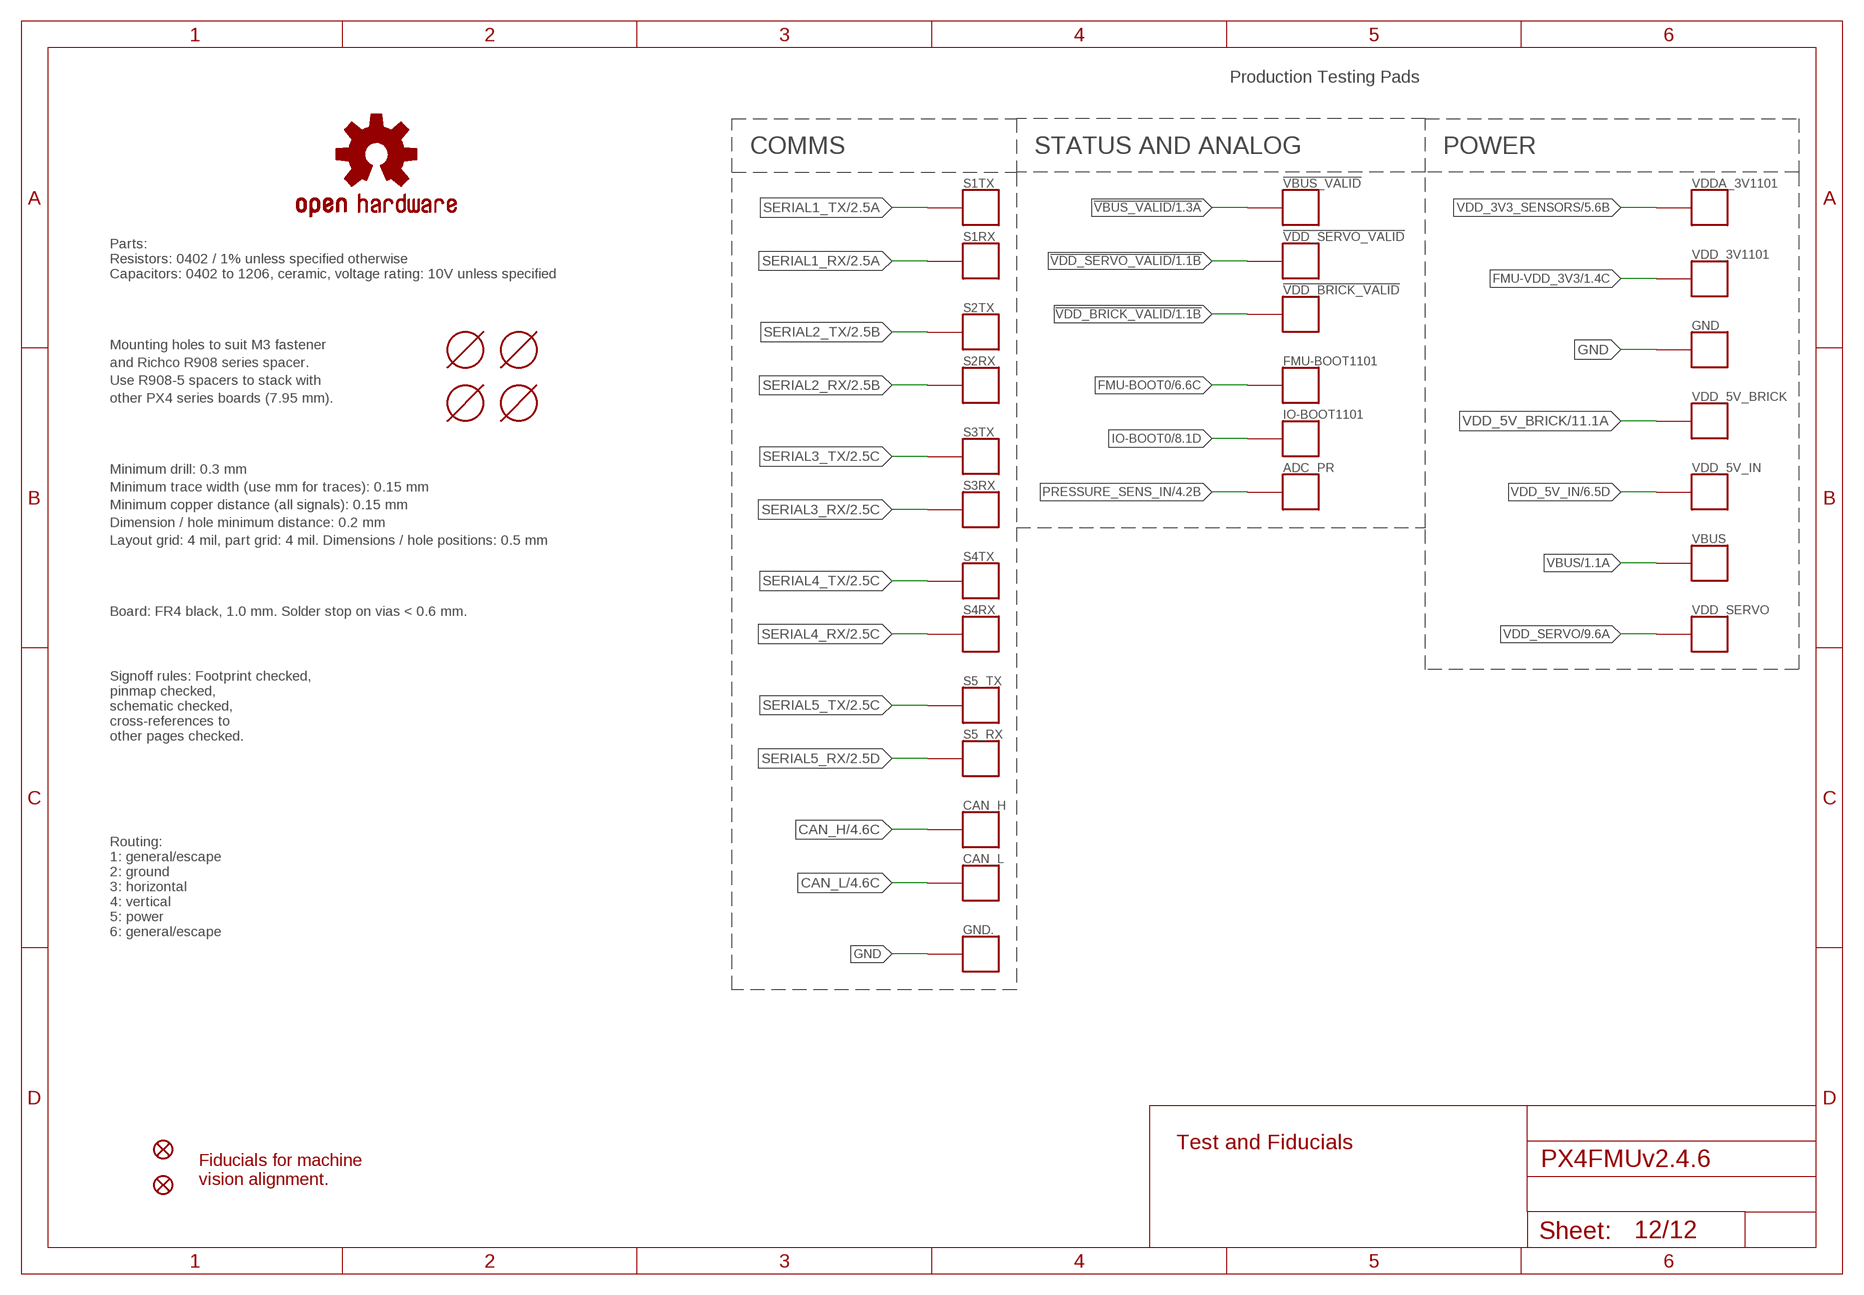
[diagram p11: schematic, sheet 12]

(export (version "E")
  (design (tool "Eeschema 10.0.6"))
  (components
    (comp (ref "C701")
      (value "0u1")
      (footprint "eagle-import:0402-CAP")
      (fields (field (name "PARTNO") "CC0402ZRY5V7BB104"))
      (libsource (lib "eagle-import") (part "CAP0402"))
    )
    (comp (ref "C702")
      (value "1u")
      (footprint "eagle-import:0603-CAP")
      (fields (field (name "PARTNO") "CC0603ZRY5V7BB105"))
      (libsource (lib "eagle-import") (part "CAP0603"))
    )
    (comp (ref "C703")
      (value "5n6")
      (footprint "eagle-import:0402-CAP")
      (fields (field (name "PARTNO") "C0402C562K5RACTU"))
      (libsource (lib "eagle-import") (part "CAP0402"))
    )
    (comp (ref "C704")
      (value "0u47")
      (footprint "eagle-import:0402-CAP")
      (fields (field (name "PARTNO") "C1005X5R1C474K050BC"))
      (libsource (lib "eagle-import") (part "CAP0402"))
    )
    (comp (ref "D701")
      (value "PESD0402-140")
      (footprint "eagle-import:0402-TVS")
      (libsource (lib "eagle-import") (part "DIODE-TVS"))
    )
    (comp (ref "J701")
      (value "DF13C-2P-1.25V")
      (footprint "eagle-import:DF13C-2P-1.25V")
      (fields (field (name "PARTNO") "DF13C-2P-1.25V(20)"))
      (libsource (lib "eagle-import") (part "DF13-2P-1.25V"))
    )
    (comp (ref "J702")
      (value "DF13C-3P-1.25V")
      (footprint "eagle-import:DF13C-3P-1.25V")
      (fields (field (name "PARTNO") "DF13C-3P-1.25V(20)"))
      (libsource (lib "eagle-import") (part "DF13-3P-1.25V"))
    )
    (comp (ref "L701")
      (value "47uH")
      (footprint "eagle-import:0805-IND")
      (fields (field (name "PARTNO") "MLZ2012M470W"))
      (libsource (lib "eagle-import") (part "INDUCTOR0805"))
    )
    (comp (ref "LED701")
      (value "AMBER")
      (footprint "eagle-import:0603-LED")
      (fields (field (name "PARTNO") "APTD1608SECK"))
      (libsource (lib "eagle-import") (part "LED0603"))
    )
    (comp (ref "LED702")
      (value "GREEN")
      (footprint "eagle-import:0603-LED")
      (fields (field (name "PARTNO") "APTD1608CGCK"))
      (libsource (lib "eagle-import") (part "LED0603"))
    )
    (comp (ref "LED703")
      (value "AMBER")
      (footprint "eagle-import:0603-LED")
      (fields (field (name "PARTNO") "APTD1608SECK"))
      (libsource (lib "eagle-import") (part "LED0603"))
    )
    (comp (ref "LED704")
      (value "GREEN")
      (footprint "eagle-import:0603-LED")
      (fields (field (name "PARTNO") "APTD1608CGCK"))
      (libsource (lib "eagle-import") (part "LED0603"))
    )
    (comp (ref "LED705")
      (value "BLUE")
      (footprint "eagle-import:0603-LED")
      (fields (field (name "PARTNO") "APTD1608QBC/D"))
      (libsource (lib "eagle-import") (part "LED0603"))
    )
    (comp (ref "R701")
      (value "9K09")
      (footprint "eagle-import:0402-RES")
      (fields (field (name "PARTNO") "RMCF0402FT9K09"))
      (libsource (lib "eagle-import") (part "RESISTOR0402-RES"))
    )
    (comp (ref "R702")
      (value "10K")
      (footprint "eagle-import:0402-RES")
      (fields (field (name "PARTNO") "RC0402FR-0710KL"))
      (libsource (lib "eagle-import") (part "RESISTOR0402-RES"))
    )
    (comp (ref "R703")
      (value "100K")
      (footprint "eagle-import:0402-RES")
      (fields (field (name "PARTNO") "RC0402FR-07100KL"))
      (libsource (lib "eagle-import") (part "RESISTOR0402-RES"))
    )
    (comp (ref "R704")
      (value "10K")
      (footprint "eagle-import:0402-RES")
      (fields (field (name "PARTNO") "RC0402FR-0710KL"))
      (libsource (lib "eagle-import") (part "RESISTOR0402-RES"))
    )
    (comp (ref "R705")
      (value "453K")
      (footprint "eagle-import:0402-RES")
      (fields (field (name "PARTNO") "RMCF0402FT453K"))
      (libsource (lib "eagle-import") (part "RESISTOR0402-RES"))
    )
    (comp (ref "R706")
      (value "16K5")
      (footprint "eagle-import:0402-RES")
      (fields (field (name "PARTNO") "RMCF0402FT16K5"))
      (libsource (lib "eagle-import") (part "RESISTOR0402-RES"))
    )
    (comp (ref "R707")
      (value "220R")
      (footprint "eagle-import:0402-RES")
      (fields (field (name "PARTNO") "RC0402FR-07220RL"))
      (libsource (lib "eagle-import") (part "RESISTOR0402-RES"))
    )
    (comp (ref "R708")
      (value "220R")
      (footprint "eagle-import:0402-RES")
      (fields (field (name "PARTNO") "RC0402FR-07220RL"))
      (libsource (lib "eagle-import") (part "RESISTOR0402-RES"))
    )
    (comp (ref "R709")
      (value "220R")
      (footprint "eagle-import:0402-RES")
      (fields (field (name "PARTNO") "RC0402FR-07220RL"))
      (libsource (lib "eagle-import") (part "RESISTOR0402-RES"))
    )
    (comp (ref "R710")
      (value "68R")
      (footprint "eagle-import:0402-RES")
      (fields (field (name "PARTNO") "ERJ-2GEJ680X"))
      (libsource (lib "eagle-import") (part "RESISTOR0402-RES"))
    )
    (comp (ref "R711")
      (value "220R")
      (footprint "eagle-import:0402-RES")
      (fields (field (name "PARTNO") "RC0402FR-07220RL"))
      (libsource (lib "eagle-import") (part "RESISTOR0402-RES"))
    )
    (comp (ref "R712")
      (value "220R")
      (footprint "eagle-import:0402-RES")
      (fields (field (name "PARTNO") "RC0402FR-07220RL"))
      (libsource (lib "eagle-import") (part "RESISTOR0402-RES"))
    )
    (comp (ref "R713")
      (value "1K5")
      (footprint "eagle-import:0402-RES")
      (fields (field (name "PARTNO") "RC0402FR-071K5L"))
      (libsource (lib "eagle-import") (part "RESISTOR0402-RES"))
    )
    (comp (ref "R735")
      (value "220R")
      (footprint "eagle-import:0402-RES")
      (fields (field (name "PARTNO") "RC0402FR-07220RL"))
      (libsource (lib "eagle-import") (part "RESISTOR0402-RES"))
    )
    (comp (ref "R736")
      (value "220R")
      (footprint "eagle-import:0402-RES")
      (fields (field (name "PARTNO") "RC0402FR-07220RL"))
      (libsource (lib "eagle-import") (part "RESISTOR0402-RES"))
    )
    (comp (ref "U701")
      (value "TCA62724FMG")
      (footprint "eagle-import:SON10")
      (libsource (lib "eagle-import") (part "TCA62724FMG"))
    )
    (comp (ref "U702")
      (value "LT3469")
      (footprint "eagle-import:SOT23-8")
      (fields (field (name "PARTNO") "LT3469ETS8"))
      (libsource (lib "eagle-import") (part "LT3469"))
    )
    (comp (ref "U703")
      (value "LRTB GFTG-T7AW-1+V7A7-29+R5T9-49-L")
      (footprint "eagle-import:6-PLCC")
      (fields (field (name "PARTNO") "LRTB GFTG-T7AW-1+V7A7-29+R5T9-49-L"))
      (libsource (lib "eagle-import") (part "RGB-LED6-PLCC"))
    )
    (comp (ref "C1101")
      (value "22u/25V")
      (footprint "eagle-import:0805-CAP")
      (fields (field (name "PARTNO") "CL21A226MAQNNNE"))
      (libsource (lib "eagle-import") (part "CAP0805"))
    )
    (comp (ref "C1102")
      (value "22u/25V")
      (footprint "eagle-import:0805-CAP")
      (fields (field (name "PARTNO") "CL21A226MAQNNNE"))
      (libsource (lib "eagle-import") (part "CAP0805"))
    )
    (comp (ref "C1103")
      (value "22u/25V")
      (footprint "eagle-import:0805-CAP")
      (fields (field (name "PARTNO") "CL21A226MAQNNNE"))
      (libsource (lib "eagle-import") (part "CAP0805"))
    )
    (comp (ref "C1104")
      (value "100u")
      (footprint "eagle-import:1206-CAP")
      (fields (field (name "PARTNO") "C3216X5R1A107M160AC"))
      (libsource (lib "eagle-import") (part "CAP1206"))
    )
    (comp (ref "C1105")
      (value "0u1")
      (footprint "eagle-import:0402-CAP")
      (fields (field (name "PARTNO") "C1005X7R1E104K050BB"))
      (libsource (lib "eagle-import") (part "CAP0402"))
    )
    (comp (ref "C1106")
      (value "0u1")
      (footprint "eagle-import:0402-CAP")
      (fields (field (name "PARTNO") "C1005X7R1E104K050BB"))
      (libsource (lib "eagle-import") (part "CAP0402"))
    )
    (comp (ref "C1107")
      (value "0u1")
      (footprint "eagle-import:0402-CAP")
      (fields (field (name "PARTNO") "C1005X7R1E104K050BB"))
      (libsource (lib "eagle-import") (part "CAP0402"))
    )
    (comp (ref "C1108")
      (value "10p/25V")
      (footprint "eagle-import:0402-CAP")
      (fields (field (name "PARTNO") "C0402C100J3GACTU"))
      (libsource (lib "eagle-import") (part "CAP0402"))
    )
    (comp (ref "C1109")
      (value "10p/25V")
      (footprint "eagle-import:0402-CAP")
      (fields (field (name "PARTNO") "C0402C100J3GACTU"))
      (libsource (lib "eagle-import") (part "CAP0402"))
    )
    (comp (ref "C1110")
      (value "10p/25V")
      (footprint "eagle-import:0402-CAP")
      (fields (field (name "PARTNO") "C0402C100J3GACTU"))
      (libsource (lib "eagle-import") (part "CAP0402"))
    )
    (comp (ref "J601")
      (value "DF13C-6P-1.25V")
      (footprint "eagle-import:DF13C-6P-1.25V")
      (fields (field (name "PARTNO") "DF13C-6P-1.25V(20)"))
      (libsource (lib "eagle-import") (part "DF13-6P-1.25V"))
    )
    (comp (ref "L1101")
      (value "KNH16C104DA5TS")
      (footprint "eagle-import:KYOCERA-KNH16-DA")
      (libsource (lib "eagle-import") (part "KNH16C104DA5TS"))
    )
    (comp (ref "L1102")
      (value "KNH16C104DA5TS")
      (footprint "eagle-import:KYOCERA-KNH16-DA")
      (libsource (lib "eagle-import") (part "KNH16C104DA5TS"))
    )
    (comp (ref "R1101")
      (value "10K/0.1%")
      (footprint "eagle-import:0402-RES")
      (fields (field (name "PARTNO") "ERA-2AEB103X"))
      (libsource (lib "eagle-import") (part "RESISTOR0402-RES"))
    )
    (comp (ref "R1102")
      (value "10K/0.1%")
      (footprint "eagle-import:0402-RES")
      (fields (field (name "PARTNO") "ERA-2AEB103X"))
      (libsource (lib "eagle-import") (part "RESISTOR0402-RES"))
    )
    (comp (ref "R1103")
      (value "1M")
      (footprint "eagle-import:0402-RES")
      (fields (field (name "PARTNO") "RC0402FR-071ML"))
      (libsource (lib "eagle-import") (part "RESISTOR0402-RES"))
    )
    (comp (ref "R1104")
      (value "1M")
      (footprint "eagle-import:0402-RES")
      (fields (field (name "PARTNO") "RC0402FR-071ML"))
      (libsource (lib "eagle-import") (part "RESISTOR0402-RES"))
    )
    (comp (ref "R1105")
      (value "453K")
      (footprint "eagle-import:0402-RES")
      (fields (field (name "PARTNO") "RMCF0402FT453K"))
      (libsource (lib "eagle-import") (part "RESISTOR0402-RES"))
    )
    (comp (ref "R1106")
      (value "56K")
      (footprint "eagle-import:0402-RES")
      (fields (field (name "PARTNO") "ERA-2AEB563X"))
      (libsource (lib "eagle-import") (part "RESISTOR0402-RES"))
    )
    (comp (ref "R1107")
      (value "105K")
      (footprint "eagle-import:0402-RES")
      (fields (field (name "PARTNO") "ERJ-2RKF1053X"))
      (libsource (lib "eagle-import") (part "RESISTOR0402-RES"))
    )
    (comp (ref "R1109")
      (value "453K")
      (footprint "eagle-import:0402-RES")
      (fields (field (name "PARTNO") "RMCF0402FT453K"))
      (libsource (lib "eagle-import") (part "RESISTOR0402-RES"))
    )
    (comp (ref "R1110")
      (value "56K")
      (footprint "eagle-import:0402-RES")
      (fields (field (name "PARTNO") "ERA-2AEB563X"))
      (libsource (lib "eagle-import") (part "RESISTOR0402-RES"))
    )
    (comp (ref "R1111")
      (value "105K")
      (footprint "eagle-import:0402-RES")
      (fields (field (name "PARTNO") "ERJ-2RKF1053X"))
      (libsource (lib "eagle-import") (part "RESISTOR0402-RES"))
    )
    (comp (ref "R1112")
      (value "453K")
      (footprint "eagle-import:0402-RES")
      (fields (field (name "PARTNO") "RMCF0402FT453K"))
      (libsource (lib "eagle-import") (part "RESISTOR0402-RES"))
    )
    (comp (ref "R1113")
      (value "56K")
      (footprint "eagle-import:0402-RES")
      (fields (field (name "PARTNO") "ERA-2AEB563X"))
      (libsource (lib "eagle-import") (part "RESISTOR0402-RES"))
    )
    (comp (ref "R1114")
      (value "105K")
      (footprint "eagle-import:0402-RES")
      (fields (field (name "PARTNO") "ERJ-2RKF1053X"))
      (libsource (lib "eagle-import") (part "RESISTOR0402-RES"))
    )
    (comp (ref "R1115")
      (value "0R")
      (footprint "eagle-import:0402-RES")
      (fields (field (name "PARTNO") "ERJ-2GE0R00X"))
      (libsource (lib "eagle-import") (part "RESISTOR0402-RES"))
    )
    (comp (ref "RN1101")
      (value "1M")
      (footprint "eagle-import:EXB28V")
      (fields (field (name "PARTNO") "EXB-28V105JX"))
      (libsource (lib "eagle-import") (part "4R-NEXB28V"))
    )
    (comp (ref "U1101")
      (value "LTC4417")
      (footprint "eagle-import:MO-220")
      (fields (field (name "PARTNO") "LTC4417IUF#PBF"))
      (libsource (lib "eagle-import") (part "LTC4117"))
    )
    (comp (ref "U1102")
      (value "NTHD4102PT1G")
      (footprint "eagle-import:1206-8")
      (fields (field (name "PARTNO") "NTHD4102PT1G"))
      (libsource (lib "eagle-import") (part "MOSFET-DUAL-PCHANNEL-CHIPFET"))
    )
    (comp (ref "U1103")
      (value "NTHD4102PT1G")
      (footprint "eagle-import:1206-8")
      (fields (field (name "PARTNO") "NTHD4102PT1G"))
      (libsource (lib "eagle-import") (part "MOSFET-DUAL-PCHANNEL-CHIPFET"))
    )
    (comp (ref "U1104")
      (value "NTHD4102PT1G")
      (footprint "eagle-import:1206-8")
      (fields (field (name "PARTNO") "NTHD4102PT1G"))
      (libsource (lib "eagle-import") (part "MOSFET-DUAL-PCHANNEL-CHIPFET"))
    )
    (comp (ref "C501")
      (value "10u/10V")
      (footprint "eagle-import:0805-CAP")
      (fields (field (name "PARTNO") "CC0805ZKY5V6BB106"))
      (libsource (lib "eagle-import") (part "CAP0805"))
    )
    (comp (ref "C502")
      (value "0u1")
      (footprint "eagle-import:0402-CAP")
      (fields (field (name "PARTNO") "CC0402ZRY5V7BB104"))
      (libsource (lib "eagle-import") (part "CAP0402"))
    )
    (comp (ref "C503")
      (value "0u1")
      (footprint "eagle-import:0402-CAP")
      (fields (field (name "PARTNO") "CC0402ZRY5V7BB104"))
      (libsource (lib "eagle-import") (part "CAP0402"))
    )
    (comp (ref "C504")
      (value "10n")
      (footprint "eagle-import:0402-CAP")
      (fields (field (name "PARTNO") "CC0402KRX7R7BB103"))
      (libsource (lib "eagle-import") (part "CAP0402"))
    )
    (comp (ref "C505")
      (value "10n")
      (footprint "eagle-import:0402-CAP")
      (fields (field (name "PARTNO") "CC0402KRX7R7BB103"))
      (libsource (lib "eagle-import") (part "CAP0402"))
    )
    (comp (ref "C506")
      (value "10u/10V")
      (footprint "eagle-import:0805-CAP")
      (fields (field (name "PARTNO") "CC0805ZKY5V6BB106"))
      (libsource (lib "eagle-import") (part "CAP0805"))
    )
    (comp (ref "C507")
      (value "0u1")
      (footprint "eagle-import:0402-CAP")
      (fields (field (name "PARTNO") "CC0402ZRY5V7BB104"))
      (libsource (lib "eagle-import") (part "CAP0402"))
    )
    (comp (ref "C508")
      (value "0u1")
      (footprint "eagle-import:0402-CAP")
      (fields (field (name "PARTNO") "CC0402ZRY5V7BB104"))
      (libsource (lib "eagle-import") (part "CAP0402"))
    )
    (comp (ref "C509")
      (value "10u/10V")
      (footprint "eagle-import:0805-CAP")
      (fields (field (name "PARTNO") "CC0805ZKY5V6BB106"))
      (libsource (lib "eagle-import") (part "CAP0805"))
    )
    (comp (ref "C510")
      (value "0u47")
      (footprint "eagle-import:0402-CAP")
      (fields (field (name "PARTNO") "C1005X5R1C474K050BC"))
      (libsource (lib "eagle-import") (part "CAP0402"))
    )
    (comp (ref "C511")
      (value "10u/10V")
      (footprint "eagle-import:0805-CAP")
      (fields (field (name "PARTNO") "CC0805ZKY5V6BB106"))
      (libsource (lib "eagle-import") (part "CAP0805"))
    )
    (comp (ref "C512")
      (value "2u2")
      (footprint "eagle-import:0603-CAP")
      (fields (field (name "PARTNO") "C1608X6S1C225K080AC"))
      (libsource (lib "eagle-import") (part "CAP0603"))
    )
    (comp (ref "C513")
      (value "2u2")
      (footprint "eagle-import:0603-CAP")
      (fields (field (name "PARTNO") "C1608X6S1C225K080AC"))
      (libsource (lib "eagle-import") (part "CAP0603"))
    )
    (comp (ref "C514")
      (value "0u1")
      (footprint "eagle-import:0402-CAP")
      (fields (field (name "PARTNO") "CC0402ZRY5V7BB104"))
      (libsource (lib "eagle-import") (part "CAP0402"))
    )
    (comp (ref "C515")
      (value "0u01")
      (footprint "eagle-import:0603-CAP")
      (fields (field (name "PARTNO") "06033C103JAT2A"))
      (libsource (lib "eagle-import") (part "CAP0603"))
    )
    (comp (ref "U501")
      (value "L3GD20")
      (footprint "eagle-import:L3G4200DH-MAN")
      (libsource (lib "eagle-import") (part "L3G4200DH-LL"))
    )
    (comp (ref "U502")
      (value "L3GD20H")
      (footprint "eagle-import:LGA-16L")
      (libsource (lib "eagle-import") (part "L3GD20H"))
    )
    (comp (ref "U504")
      (value "LSM303D")
      (footprint "eagle-import:LGA-16L")
      (libsource (lib "eagle-import") (part "LSM303D"))
    )
    (comp (ref "U505")
      (value "MPU-6000")
      (footprint "eagle-import:QFN-24")
      (libsource (lib "eagle-import") (part "MPU-6000"))
    )
    (comp (ref "U506")
      (value "MS5611-01BA")
      (footprint "eagle-import:MS5611-01BA")
      (libsource (lib "eagle-import") (part "MS5611-01BA"))
    )
    (comp (ref "X503")
      (value "0512811094")
      (footprint "eagle-import:51281-1094")
      (fields (field (name "PARTNO") "0781191109") (field (name "BOM") "EXCLUDE"))
      (libsource (lib "eagle-import") (part "CONN_FPC_10RA"))
    )
    (comp (ref "C901")
      (value "0u1")
      (footprint "eagle-import:0402-CAP")
      (fields (field (name "PARTNO") "CC0402ZRY5V7BB104"))
      (libsource (lib "eagle-import") (part "CAP0402"))
    )
    (comp (ref "C902")
      (value "0u1")
      (footprint "eagle-import:0402-CAP")
      (fields (field (name "PARTNO") "CC0402ZRY5V7BB104"))
      (libsource (lib "eagle-import") (part "CAP0402"))
    )
    (comp (ref "C903")
      (value "0u1")
      (footprint "eagle-import:0402-CAP")
      (fields (field (name "PARTNO") "CC0402ZRY5V7BB104"))
      (libsource (lib "eagle-import") (part "CAP0402"))
    )
    (comp (ref "D901")
      (value "PESD0402-140")
      (footprint "eagle-import:0402-TVS")
      (libsource (lib "eagle-import") (part "DIODE-TVS"))
    )
    (comp (ref "D902")
      (value "PESD0402-140")
      (footprint "eagle-import:0402-TVS")
      (libsource (lib "eagle-import") (part "DIODE-TVS"))
    )
    (comp (ref "D903")
      (value "PESD0402-140")
      (footprint "eagle-import:0402-TVS")
      (libsource (lib "eagle-import") (part "DIODE-TVS"))
    )
    (comp (ref "D904")
      (value "MSS1P4-M3")
      (footprint "eagle-import:MICROSMP")
      (fields (field (name "PARTNO") "MSS1P4-M3/89A"))
      (libsource (lib "eagle-import") (part "DIODE-SCHOTTKY_MSMP"))
    )
    (comp (ref "J901")
      (value "HEADER-3X163X16RA")
      (footprint "eagle-import:3X16RA")
      (fields (field (name "BOM") "EXCLUDE"))
      (libsource (lib "eagle-import") (part "HEADER-3X163X16RA"))
    )
    (comp (ref "L901")
      (value "KNH16C104DA5TS")
      (footprint "eagle-import:KYOCERA-KNH16-DA")
      (libsource (lib "eagle-import") (part "KNH16C104DA5TS"))
    )
    (comp (ref "R901")
      (value "10K")
      (footprint "eagle-import:0402-RES")
      (fields (field (name "PARTNO") "RC0402FR-0710KL"))
      (libsource (lib "eagle-import") (part "RESISTOR0402-RES"))
    )
    (comp (ref "R902")
      (value "220R")
      (footprint "eagle-import:0402-RES")
      (fields (field (name "PARTNO") "RC0402FR-07220RL"))
      (libsource (lib "eagle-import") (part "RESISTOR0402-RES"))
    )
    (comp (ref "R903")
      (value "220R")
      (footprint "eagle-import:0402-RES")
      (fields (field (name "PARTNO") "RC0402FR-07220RL"))
      (libsource (lib "eagle-import") (part "RESISTOR0402-RES"))
    )
    (comp (ref "R904")
      (value "220R")
      (footprint "eagle-import:0402-RES")
      (fields (field (name "PARTNO") "RC0402FR-07220RL"))
      (libsource (lib "eagle-import") (part "RESISTOR0402-RES"))
    )
    (comp (ref "R905")
      (value "220R")
      (footprint "eagle-import:0402-RES")
      (fields (field (name "PARTNO") "RC0402FR-07220RL"))
      (libsource (lib "eagle-import") (part "RESISTOR0402-RES"))
    )
    (comp (ref "R906")
      (value "220R")
      (footprint "eagle-import:0402-RES")
      (fields (field (name "PARTNO") "RC0402FR-07220RL"))
      (libsource (lib "eagle-import") (part "RESISTOR0402-RES"))
    )
    (comp (ref "R907")
      (value "220R")
      (footprint "eagle-import:0402-RES")
      (fields (field (name "PARTNO") "RC0402FR-07220RL"))
      (libsource (lib "eagle-import") (part "RESISTOR0402-RES"))
    )
    (comp (ref "R908")
      (value "220R")
      (footprint "eagle-import:0402-RES")
      (fields (field (name "PARTNO") "RC0402FR-07220RL"))
      (libsource (lib "eagle-import") (part "RESISTOR0402-RES"))
    )
    (comp (ref "R909")
      (value "220R")
      (footprint "eagle-import:0402-RES")
      (fields (field (name "PARTNO") "RC0402FR-07220RL"))
      (libsource (lib "eagle-import") (part "RESISTOR0402-RES"))
    )
    (comp (ref "R910")
      (value "220R")
      (footprint "eagle-import:0402-RES")
      (fields (field (name "PARTNO") "RC0402FR-07220RL"))
      (libsource (lib "eagle-import") (part "RESISTOR0402-RES"))
    )
    (comp (ref "R911")
      (value "220R")
      (footprint "eagle-import:0402-RES")
      (fields (field (name "PARTNO") "RC0402FR-07220RL"))
      (libsource (lib "eagle-import") (part "RESISTOR0402-RES"))
    )
    (comp (ref "R912")
      (value "220R")
      (footprint "eagle-import:0402-RES")
      (fields (field (name "PARTNO") "RC0402FR-07220RL"))
      (libsource (lib "eagle-import") (part "RESISTOR0402-RES"))
    )
    (comp (ref "R913")
      (value "220R")
      (footprint "eagle-import:0402-RES")
      (fields (field (name "PARTNO") "RC0402FR-07220RL"))
      (libsource (lib "eagle-import") (part "RESISTOR0402-RES"))
    )
    (comp (ref "R914")
      (value "220R")
      (footprint "eagle-import:0402-RES")
      (fields (field (name "PARTNO") "RC0402FR-07220RL"))
      (libsource (lib "eagle-import") (part "RESISTOR0402-RES"))
    )
    (comp (ref "R915")
      (value "220R")
      (footprint "eagle-import:0402-RES")
      (fields (field (name "PARTNO") "RC0402FR-07220RL"))
      (libsource (lib "eagle-import") (part "RESISTOR0402-RES"))
    )
    (comp (ref "R916")
      (value "220R")
      (footprint "eagle-import:0402-RES")
      (fields (field (name "PARTNO") "RC0402FR-07220RL"))
      (libsource (lib "eagle-import") (part "RESISTOR0402-RES"))
    )
    (comp (ref "R917")
      (value "220R")
      (footprint "eagle-import:0402-RES")
      (fields (field (name "PARTNO") "RC0402FR-07220RL"))
      (libsource (lib "eagle-import") (part "RESISTOR0402-RES"))
    )
    (comp (ref "R918")
      (value "10K/0.1%")
      (footprint "eagle-import:0402-RES")
      (fields (field (name "PARTNO") "ERA-2AEB103X"))
      (libsource (lib "eagle-import") (part "RESISTOR0402-RES"))
    )
    (comp (ref "R919")
      (value "10K/0.1%")
      (footprint "eagle-import:0402-RES")
      (fields (field (name "PARTNO") "ERA-2AEB103X"))
      (libsource (lib "eagle-import") (part "RESISTOR0402-RES"))
    )
    (comp (ref "R922")
      (value "10K/0.1%")
      (footprint "eagle-import:0402-RES")
      (fields (field (name "PARTNO") "ERA-2AEB103X"))
      (libsource (lib "eagle-import") (part "RESISTOR0402-RES"))
    )
    (comp (ref "U901")
      (value "TXS0108QFN20")
      (footprint "eagle-import:QFN20-RGY")
      (fields (field (name "PARTNO") "TXS0108ERGYR"))
      (libsource (lib "eagle-import") (part "TXS0108QFN20"))
    )
    (comp (ref "U902")
      (value "TXS0108QFN20")
      (footprint "eagle-import:QFN20-RGY")
      (fields (field (name "PARTNO") "TXS0108ERGYR"))
      (libsource (lib "eagle-import") (part "TXS0108QFN20"))
    )
    (comp (ref "U903")
      (value "74LVC2G240")
      (footprint "eagle-import:TSSOP8_SOT505-2")
      (fields (field (name "PARTNO") "74LVC2G240DP,125"))
      (libsource (lib "eagle-import") (part "74LVC2G240-TSSOP-8"))
    )
    (comp (ref "C801")
      (value "0u1")
      (footprint "eagle-import:0402-CAP")
      (fields (field (name "PARTNO") "CC0402ZRY5V7BB104"))
      (libsource (lib "eagle-import") (part "CAP0402"))
    )
    (comp (ref "C802")
      (value "0u1")
      (footprint "eagle-import:0402-CAP")
      (fields (field (name "PARTNO") "CC0402ZRY5V7BB104"))
      (libsource (lib "eagle-import") (part "CAP0402"))
    )
    (comp (ref "C803")
      (value "0u1")
      (footprint "eagle-import:0402-CAP")
      (fields (field (name "PARTNO") "CC0402ZRY5V7BB104"))
      (libsource (lib "eagle-import") (part "CAP0402"))
    )
    (comp (ref "C804")
      (value "0u1")
      (footprint "eagle-import:0402-CAP")
      (fields (field (name "PARTNO") "CC0402ZRY5V7BB104"))
      (libsource (lib "eagle-import") (part "CAP0402"))
    )
    (comp (ref "C805")
      (value "8p")
      (footprint "eagle-import:0402-CAP")
      (fields (field (name "PARTNO") "C1005C0G1H080C"))
      (libsource (lib "eagle-import") (part "CAP0402"))
    )
    (comp (ref "C806")
      (value "8p")
      (footprint "eagle-import:0402-CAP")
      (fields (field (name "PARTNO") "C1005C0G1H080C"))
      (libsource (lib "eagle-import") (part "CAP0402"))
    )
    (comp (ref "D801")
      (value "PESD0402-140")
      (footprint "eagle-import:0402-TVS")
      (libsource (lib "eagle-import") (part "DIODE-TVS"))
    )
    (comp (ref "J801")
      (value "JST-ZH-3")
      (footprint "eagle-import:JST-ZH-SMT-VERTICAL")
      (fields (field (name "PARTNO") "B3B-ZR-SM4-TF (LF)(SN)(P)"))
      (libsource (lib "eagle-import") (part "JST-ZH-3"))
    )
    (comp (ref "JX801")
      (value "HEADER-3X1BOARDEDGE-SHORT")
      (footprint "eagle-import:HEADER_3X01_SMD_H_BOARD_EDGE_SHORT")
      (libsource (lib "eagle-import") (part "HEADER-3X1BOARDEDGE-SHORT"))
    )
    (comp (ref "JX802")
      (value "ARM_MINI_JTAG-SMT")
      (footprint "eagle-import:FTSH-105-01-XXX-DV-K")
      (fields (field (name "BOM") "EXCLUDE") (field (name "PARTNO") "M50-3900542"))
      (libsource (lib "eagle-import") (part "ARM_MINI_JTAG-SMT"))
    )
    (comp (ref "R801")
      (value "10K")
      (footprint "eagle-import:0402-RES")
      (fields (field (name "PARTNO") "RC0402FR-0710KL"))
      (libsource (lib "eagle-import") (part "RESISTOR0402-RES"))
    )
    (comp (ref "R802")
      (value "10K")
      (footprint "eagle-import:0402-RES")
      (fields (field (name "PARTNO") "RC0402FR-0710KL"))
      (libsource (lib "eagle-import") (part "RESISTOR0402-RES"))
    )
    (comp (ref "R803")
      (value "220R")
      (footprint "eagle-import:0402-RES")
      (fields (field (name "PARTNO") "RC0402FR-07220RL"))
      (libsource (lib "eagle-import") (part "RESISTOR0402-RES"))
    )
    (comp (ref "R804")
      (value "220R")
      (footprint "eagle-import:0402-RES")
      (fields (field (name "PARTNO") "RC0402FR-07220RL"))
      (libsource (lib "eagle-import") (part "RESISTOR0402-RES"))
    )
    (comp (ref "S801")
      (value "RESET")
      (footprint "eagle-import:EVQP7J01K")
      (fields (field (name "PARTNO") "EVQ-P7J01P"))
      (libsource (lib "eagle-import") (part "SWITCH-MOMENTARY-2"))
    )
    (comp (ref "U801")
      (value "STM32F10XCXT6")
      (footprint "eagle-import:TQFP48")
      (fields (field (name "PARTNO") "STM32F100C8T6B"))
      (libsource (lib "eagle-import") (part "STM32F10XCXT6"))
    )
    (comp (ref "X801")
      (value "3.2x2.5 mm / 24 MHz / 15 ppm")
      (footprint "eagle-import:OSCILLATOR-3.2X2.5")
      (fields (field (name "PARTNO") "NX3225SA-24.000000MHZ"))
      (libsource (lib "eagle-import") (part "OSCILLATOR-3.2X2.5"))
    )
    (comp (ref "C101")
      (value "0u1")
      (footprint "eagle-import:0402-CAP")
      (fields (field (name "PARTNO") "CC0402ZRY5V7BB104"))
      (libsource (lib "eagle-import") (part "CAP0402"))
    )
    (comp (ref "C102")
      (value "8p")
      (footprint "eagle-import:0402-CAP")
      (fields (field (name "PARTNO") "C1005C0G1H080C"))
      (libsource (lib "eagle-import") (part "CAP0402"))
    )
    (comp (ref "C103")
      (value "8p")
      (footprint "eagle-import:0402-CAP")
      (fields (field (name "PARTNO") "C1005C0G1H080C"))
      (libsource (lib "eagle-import") (part "CAP0402"))
    )
    (comp (ref "R101")
      (value "470R")
      (footprint "eagle-import:0402-RES")
      (fields (field (name "PARTNO") "RC0402FR-07470RL"))
      (libsource (lib "eagle-import") (part "RESISTOR0402-RES"))
    )
    (comp (ref "R102")
      (value "10K")
      (footprint "eagle-import:0402-RES")
      (fields (field (name "PARTNO") "RC0402FR-0710KL"))
      (libsource (lib "eagle-import") (part "RESISTOR0402-RES"))
    )
    (comp (ref "U101")
      (value "STM32F4X7VX")
      (footprint "eagle-import:TQFP100")
      (fields (field (name "PARTNO") "STM32F427VI"))
      (libsource (lib "eagle-import") (part "STM32F4X7VX"))
    )
    (comp (ref "U102")
      (value "FM25V01")
      (footprint "eagle-import:SO08")
      (fields (field (name "PARTNO") "FM25V01-G"))
      (libsource (lib "eagle-import") (part "FM25V01"))
    )
    (comp (ref "X101")
      (value "3.2x2.5 mm / 24 MHz / 15 ppm")
      (footprint "eagle-import:OSCILLATOR-3.2X2.5")
      (fields (field (name "PARTNO") "NX3225SA-24.000000MHZ"))
      (libsource (lib "eagle-import") (part "OSCILLATOR-3.2X2.5"))
    )
    (comp (ref "B601")
      (value "MS621FE")
      (footprint "eagle-import:MS621FE")
      (fields (field (name "PARTNO") "MS621FE-FL11E"))
      (libsource (lib "eagle-import") (part "MS621FE"))
    )
    (comp (ref "C601")
      (value "10u/25V")
      (footprint "eagle-import:0805-CAP")
      (fields (field (name "PARTNO") "CL21A106KAYNNNE"))
      (libsource (lib "eagle-import") (part "CAP0805"))
    )
    (comp (ref "C602")
      (value "10n")
      (footprint "eagle-import:0402-CAP")
      (fields (field (name "PARTNO") "CC0402KRX7R7BB103"))
      (libsource (lib "eagle-import") (part "CAP0402"))
    )
    (comp (ref "C603")
      (value "1u")
      (footprint "eagle-import:0603-CAP")
      (fields (field (name "PARTNO") "CC0603ZRY5V7BB105"))
      (libsource (lib "eagle-import") (part "CAP0603"))
    )
    (comp (ref "C604")
      (value "22u/25V")
      (footprint "eagle-import:0805-CAP")
      (fields (field (name "PARTNO") "CL21A226MAQNNNE"))
      (libsource (lib "eagle-import") (part "CAP0805"))
    )
    (comp (ref "C605")
      (value "22u/25V")
      (footprint "eagle-import:0805-CAP")
      (fields (field (name "PARTNO") "CL21A226MAQNNNE"))
      (libsource (lib "eagle-import") (part "CAP0805"))
    )
    (comp (ref "C606")
      (value "0u1")
      (footprint "eagle-import:0402-CAP")
      (fields (field (name "PARTNO") "CC0402ZRY5V7BB104"))
      (libsource (lib "eagle-import") (part "CAP0402"))
    )
    (comp (ref "C607")
      (value "0u1")
      (footprint "eagle-import:0402-CAP")
      (fields (field (name "PARTNO") "CC0402ZRY5V7BB104"))
      (libsource (lib "eagle-import") (part "CAP0402"))
    )
    (comp (ref "C608")
      (value "0u1")
      (footprint "eagle-import:0402-CAP")
      (fields (field (name "PARTNO") "CC0402ZRY5V7BB104"))
      (libsource (lib "eagle-import") (part "CAP0402"))
    )
    (comp (ref "C609")
      (value "0u1")
      (footprint "eagle-import:0402-CAP")
      (fields (field (name "PARTNO") "CC0402ZRY5V7BB104"))
      (libsource (lib "eagle-import") (part "CAP0402"))
    )
    (comp (ref "C610")
      (value "0u1")
      (footprint "eagle-import:0402-CAP")
      (fields (field (name "PARTNO") "CC0402ZRY5V7BB104"))
      (libsource (lib "eagle-import") (part "CAP0402"))
    )
    (comp (ref "C611")
      (value "2u2")
      (footprint "eagle-import:0603-CAP")
      (fields (field (name "PARTNO") "C1608X6S1C225K080AC"))
      (libsource (lib "eagle-import") (part "CAP0603"))
    )
    (comp (ref "C612")
      (value "0u1")
      (footprint "eagle-import:0402-CAP")
      (fields (field (name "PARTNO") "CC0402ZRY5V7BB104"))
      (libsource (lib "eagle-import") (part "CAP0402"))
    )
    (comp (ref "C613")
      (value "2u2")
      (footprint "eagle-import:0603-CAP")
      (fields (field (name "PARTNO") "C1608X6S1C225K080AC"))
      (libsource (lib "eagle-import") (part "CAP0603"))
    )
    (comp (ref "C614")
      (value "100u")
      (footprint "eagle-import:1206-CAP")
      (fields (field (name "PARTNO") "C3216X5R1A107M160AC"))
      (libsource (lib "eagle-import") (part "CAP1206"))
    )
    (comp (ref "C615")
      (value "0u1")
      (footprint "eagle-import:0402-CAP")
      (fields (field (name "PARTNO") "CC0402ZRY5V7BB104"))
      (libsource (lib "eagle-import") (part "CAP0402"))
    )
    (comp (ref "C616")
      (value "0u1")
      (footprint "eagle-import:0402-CAP")
      (fields (field (name "PARTNO") "CC0402ZRY5V7BB104"))
      (libsource (lib "eagle-import") (part "CAP0402"))
    )
    (comp (ref "C617")
      (value "0u1")
      (footprint "eagle-import:0402-CAP")
      (fields (field (name "PARTNO") "CC0402ZRY5V7BB104"))
      (libsource (lib "eagle-import") (part "CAP0402"))
    )
    (comp (ref "C618")
      (value "100u")
      (footprint "eagle-import:1206-CAP")
      (fields (field (name "PARTNO") "C3216X5R1A107M160AC"))
      (libsource (lib "eagle-import") (part "CAP1206"))
    )
    (comp (ref "D602")
      (value "RB751V40T1G")
      (footprint "eagle-import:SOD323")
      (libsource (lib "eagle-import") (part "DIODE-SCHOTTKY_SOD323"))
    )
    (comp (ref "L603")
      (value "KNH16C104DA5TS")
      (footprint "eagle-import:KYOCERA-KNH16-DA")
      (libsource (lib "eagle-import") (part "KNH16C104DA5TS"))
    )
    (comp (ref "R602")
      (value "1M")
      (footprint "eagle-import:0402-RES")
      (fields (field (name "PARTNO") "RC0402FR-071ML"))
      (libsource (lib "eagle-import") (part "RESISTOR0402-RES"))
    )
    (comp (ref "R603")
      (value "10K")
      (footprint "eagle-import:0402-RES")
      (fields (field (name "PARTNO") "RC0402FR-0710KL"))
      (libsource (lib "eagle-import") (part "RESISTOR0402-RES"))
    )
    (comp (ref "R604")
      (value "1M")
      (footprint "eagle-import:0402-RES")
      (fields (field (name "PARTNO") "RC0402FR-071ML"))
      (libsource (lib "eagle-import") (part "RESISTOR0402-RES"))
    )
    (comp (ref "R608")
      (value "1K")
      (footprint "eagle-import:0402-RES")
      (fields (field (name "PARTNO") "RC0402FR-071KL"))
      (libsource (lib "eagle-import") (part "RESISTOR0402-RES"))
    )
    (comp (ref "R609")
      (value "10K/0.1%")
      (footprint "eagle-import:0402-RES")
      (fields (field (name "PARTNO") "ERA-2AEB103X"))
      (libsource (lib "eagle-import") (part "RESISTOR0402-RES"))
    )
    (comp (ref "R610")
      (value "10K/0.1%")
      (footprint "eagle-import:0402-RES")
      (fields (field (name "PARTNO") "ERA-2AEB103X"))
      (libsource (lib "eagle-import") (part "RESISTOR0402-RES"))
    )
    (comp (ref "R611")
      (value "10K")
      (footprint "eagle-import:0402-RES")
      (fields (field (name "PARTNO") "RC0402FR-0710KL"))
      (libsource (lib "eagle-import") (part "RESISTOR0402-RES"))
    )
    (comp (ref "R615")
      (value "10K")
      (footprint "eagle-import:0402-RES")
      (fields (field (name "PARTNO") "RC0402FR-0710KL"))
      (libsource (lib "eagle-import") (part "RESISTOR0402-RES"))
    )
    (comp (ref "R616")
      (value "25K5")
      (footprint "eagle-import:0402-RES")
      (fields (field (name "PARTNO") "RMCF0402FT25K5"))
      (libsource (lib "eagle-import") (part "RESISTOR0402-RES"))
    )
    (comp (ref "R617")
      (value "16K5")
      (footprint "eagle-import:0402-RES")
      (fields (field (name "PARTNO") "RMCF0402FT16K5"))
      (libsource (lib "eagle-import") (part "RESISTOR0402-RES"))
    )
    (comp (ref "R621")
      (value "220R")
      (footprint "eagle-import:0603-RES")
      (fields (field (name "PARTNO") "RC1608J100CS"))
      (libsource (lib "eagle-import") (part "RESISTOR0603-RES"))
    )
    (comp (ref "R635")
      (value "10K")
      (footprint "eagle-import:0402-RES")
      (fields (field (name "PARTNO") "RC0402FR-0710KL"))
      (libsource (lib "eagle-import") (part "RESISTOR0402-RES"))
    )
    (comp (ref "S601")
      (value "RESET")
      (footprint "eagle-import:EVQP7J01K")
      (fields (field (name "PARTNO") "EVQ-P7J01P"))
      (libsource (lib "eagle-import") (part "SWITCH-MOMENTARY-2"))
    )
    (comp (ref "U601")
      (value "BQ24315")
      (footprint "eagle-import:QFN8-DSG")
      (fields (field (name "PARTNO") "BQ24315DSGR"))
      (libsource (lib "eagle-import") (part "BQ24315"))
    )
    (comp (ref "U602")
      (value "BQ24315")
      (footprint "eagle-import:QFN8-DSG")
      (fields (field (name "PARTNO") "BQ24315DSGR"))
      (libsource (lib "eagle-import") (part "BQ24315"))
    )
    (comp (ref "U603")
      (value "MIC5332")
      (footprint "eagle-import:MLF-8-EPAD")
      (fields (field (name "PARTNO") "MIC5332-SSYMT"))
      (libsource (lib "eagle-import") (part "MIC5332"))
    )
    (comp (ref "C401")
      (value "0u1")
      (footprint "eagle-import:0402-CAP")
      (fields (field (name "PARTNO") "CC0402ZRY5V7BB104"))
      (libsource (lib "eagle-import") (part "CAP0402"))
    )
    (comp (ref "C402")
      (value "0u1")
      (footprint "eagle-import:0402-CAP")
      (fields (field (name "PARTNO") "CC0402ZRY5V7BB104"))
      (libsource (lib "eagle-import") (part "CAP0402"))
    )
    (comp (ref "D401")
      (value "PESD0402-140")
      (footprint "eagle-import:0402-TVS")
      (libsource (lib "eagle-import") (part "DIODE-TVS"))
    )
    (comp (ref "D402")
      (value "PESD0402-140")
      (footprint "eagle-import:0402-TVS")
      (libsource (lib "eagle-import") (part "DIODE-TVS"))
    )
    (comp (ref "D403")
      (value "PESD0402-140")
      (footprint "eagle-import:0402-TVS")
      (libsource (lib "eagle-import") (part "DIODE-TVS"))
    )
    (comp (ref "D404")
      (value "PESD0402-140")
      (footprint "eagle-import:0402-TVS")
      (libsource (lib "eagle-import") (part "DIODE-TVS"))
    )
    (comp (ref "J401")
      (value "DF13C-4P-1.25V")
      (footprint "eagle-import:DF13C-4P-1.25V")
      (fields (field (name "PARTNO") "DF13C-4P-1.25V(20)"))
      (libsource (lib "eagle-import") (part "DF13-4P-1.25V"))
    )
    (comp (ref "J402")
      (value "DF13C-3P-1.25V")
      (footprint "eagle-import:DF13C-3P-1.25V")
      (fields (field (name "PARTNO") "DF13C-3P-1.25V(20)"))
      (libsource (lib "eagle-import") (part "DF13-3P-1.25V"))
    )
    (comp (ref "J403")
      (value "DF13C-7P-1.25V")
      (footprint "eagle-import:DF13C-7P-1.25V")
      (fields (field (name "PARTNO") "DF13C-7P-1.25V(20)"))
      (libsource (lib "eagle-import") (part "DF13-7P-1.25V"))
    )
    (comp (ref "J404")
      (value "DF13C-5P-1.25V")
      (footprint "eagle-import:DF13C-5P-1.25V")
      (fields (field (name "PARTNO") "DF13C-5P-1.25V(20)"))
      (libsource (lib "eagle-import") (part "DF13-5P-1.25V"))
    )
    (comp (ref "J405")
      (value "DF13C-4P-1.25V")
      (footprint "eagle-import:DF13C-4P-1.25V")
      (fields (field (name "PARTNO") "DF13C-4P-1.25V(20)"))
      (libsource (lib "eagle-import") (part "DF13-4P-1.25V"))
    )
    (comp (ref "L401")
      (value "KNH16C104DA5TS")
      (footprint "eagle-import:KYOCERA-KNH16-DA")
      (libsource (lib "eagle-import") (part "KNH16C104DA5TS"))
    )
    (comp (ref "L402")
      (value "KNH16C104DA5TS")
      (footprint "eagle-import:KYOCERA-KNH16-DA")
      (libsource (lib "eagle-import") (part "KNH16C104DA5TS"))
    )
    (comp (ref "L403")
      (value "KNH16C104DA5TS")
      (footprint "eagle-import:KYOCERA-KNH16-DA")
      (libsource (lib "eagle-import") (part "KNH16C104DA5TS"))
    )
    (comp (ref "L404")
      (value "KNH16C104DA5TS")
      (footprint "eagle-import:KYOCERA-KNH16-DA")
      (libsource (lib "eagle-import") (part "KNH16C104DA5TS"))
    )
    (comp (ref "R401")
      (value "1K5")
      (footprint "eagle-import:0402-RES")
      (fields (field (name "PARTNO") "RC0402FR-071K5L"))
      (libsource (lib "eagle-import") (part "RESISTOR0402-RES"))
    )
    (comp (ref "R402")
      (value "1K5")
      (footprint "eagle-import:0402-RES")
      (fields (field (name "PARTNO") "RC0402FR-071K5L"))
      (libsource (lib "eagle-import") (part "RESISTOR0402-RES"))
    )
    (comp (ref "R403")
      (value "10K/0.1%")
      (footprint "eagle-import:0402-RES")
      (fields (field (name "PARTNO") "ERA-2AEB103X"))
      (libsource (lib "eagle-import") (part "RESISTOR0402-RES"))
    )
    (comp (ref "R404")
      (value "120R")
      (footprint "eagle-import:0402-RES")
      (fields (field (name "PARTNO") "RC0402FR-07120RL"))
      (libsource (lib "eagle-import") (part "RESISTOR0402-RES"))
    )
    (comp (ref "R405")
      (value "120R")
      (footprint "eagle-import:0402-RES")
      (fields (field (name "PARTNO") "RC0402FR-07120RL"))
      (libsource (lib "eagle-import") (part "RESISTOR0402-RES"))
    )
    (comp (ref "R406")
      (value "10K/0.1%")
      (footprint "eagle-import:0402-RES")
      (fields (field (name "PARTNO") "ERA-2AEB103X"))
      (libsource (lib "eagle-import") (part "RESISTOR0402-RES"))
    )
    (comp (ref "R407")
      (value "10K/0.1%")
      (footprint "eagle-import:0402-RES")
      (fields (field (name "PARTNO") "ERA-2AEB103X"))
      (libsource (lib "eagle-import") (part "RESISTOR0402-RES"))
    )
    (comp (ref "R408")
      (value "10K/0.1%")
      (footprint "eagle-import:0402-RES")
      (fields (field (name "PARTNO") "ERA-2AEB103X"))
      (libsource (lib "eagle-import") (part "RESISTOR0402-RES"))
    )
    (comp (ref "R409")
      (value "120R")
      (footprint "eagle-import:0402-RES")
      (fields (field (name "PARTNO") "RC0402FR-07120RL"))
      (libsource (lib "eagle-import") (part "RESISTOR0402-RES"))
    )
    (comp (ref "U401")
      (value "MAX3051")
      (footprint "eagle-import:SOT23-8")
      (fields (field (name "PARTNO") "MAX3051EKA"))
      (libsource (lib "eagle-import") (part "MAX3051MAX3051EKA"))
    )
    (comp (ref "J301")
      (value "47346-0001")
      (footprint "eagle-import:MOLEX-47346-0001")
      (libsource (lib "eagle-import") (part "MOLEX-47346-0001"))
    )
    (comp (ref "J302")
      (value "DF13C-4P-1.25V")
      (footprint "eagle-import:DF13C-4P-1.25V")
      (fields (field (name "PARTNO") "DF13C-4P-1.25V(20)"))
      (libsource (lib "eagle-import") (part "DF13-4P-1.25V"))
    )
    (comp (ref "JX301")
      (value "ARM_MINI_JTAG-SMT")
      (footprint "eagle-import:FTSH-105-01-XXX-DV-K")
      (fields (field (name "BOM") "EXCLUDE") (field (name "PARTNO") "M50-3900542"))
      (libsource (lib "eagle-import") (part "ARM_MINI_JTAG-SMT"))
    )
    (comp (ref "R301")
      (value "100K")
      (footprint "eagle-import:0402-RES")
      (fields (field (name "PARTNO") "RC0402FR-07100KL"))
      (libsource (lib "eagle-import") (part "RESISTOR0402-RES"))
    )
    (comp (ref "R302")
      (value "100K")
      (footprint "eagle-import:0402-RES")
      (fields (field (name "PARTNO") "RC0402FR-07100KL"))
      (libsource (lib "eagle-import") (part "RESISTOR0402-RES"))
    )
    (comp (ref "R303")
      (value "100K")
      (footprint "eagle-import:0402-RES")
      (fields (field (name "PARTNO") "RC0402FR-07100KL"))
      (libsource (lib "eagle-import") (part "RESISTOR0402-RES"))
    )
    (comp (ref "R304")
      (value "100K")
      (footprint "eagle-import:0402-RES")
      (fields (field (name "PARTNO") "RC0402FR-07100KL"))
      (libsource (lib "eagle-import") (part "RESISTOR0402-RES"))
    )
    (comp (ref "R305")
      (value "100K")
      (footprint "eagle-import:0402-RES")
      (fields (field (name "PARTNO") "RC0402FR-07100KL"))
      (libsource (lib "eagle-import") (part "RESISTOR0402-RES"))
    )
    (comp (ref "R306")
      (value "1K5")
      (footprint "eagle-import:0402-RES")
      (fields (field (name "PARTNO") "RC0402FR-071K5L"))
      (libsource (lib "eagle-import") (part "RESISTOR0402-RES"))
    )
    (comp (ref "R307")
      (value "1K5")
      (footprint "eagle-import:0402-RES")
      (fields (field (name "PARTNO") "RC0402FR-071K5L"))
      (libsource (lib "eagle-import") (part "RESISTOR0402-RES"))
    )
    (comp (ref "U301")
      (value "2908-05WB-MG")
      (footprint "eagle-import:MICROSD")
      (libsource (lib "eagle-import") (part "MICROSDSDI"))
    )
    (comp (ref "U302")
      (value "NUF2042XV6")
      (footprint "eagle-import:SOT563-6")
      (fields (field (name "PARTNO") "NUF2042XV6T1G"))
      (libsource (lib "eagle-import") (part "NUF2042XV6"))
    )
    (comp (ref "C201")
      (value "0u1")
      (footprint "eagle-import:0402-CAP")
      (fields (field (name "PARTNO") "CC0402ZRY5V7BB104"))
      (libsource (lib "eagle-import") (part "CAP0402"))
    )
    (comp (ref "C202")
      (value "0u1")
      (footprint "eagle-import:0402-CAP")
      (fields (field (name "PARTNO") "CC0402ZRY5V7BB104"))
      (libsource (lib "eagle-import") (part "CAP0402"))
    )
    (comp (ref "D201")
      (value "PESD0402-140")
      (footprint "eagle-import:0402-TVS")
      (libsource (lib "eagle-import") (part "DIODE-TVS"))
    )
    (comp (ref "D202")
      (value "PESD0402-140")
      (footprint "eagle-import:0402-TVS")
      (libsource (lib "eagle-import") (part "DIODE-TVS"))
    )
    (comp (ref "D203")
      (value "PESD0402-140")
      (footprint "eagle-import:0402-TVS")
      (libsource (lib "eagle-import") (part "DIODE-TVS"))
    )
    (comp (ref "J201")
      (value "DF13C-6P-1.25V")
      (footprint "eagle-import:DF13C-6P-1.25V")
      (fields (field (name "PARTNO") "DF13C-6P-1.25V(20)"))
      (libsource (lib "eagle-import") (part "DF13-6P-1.25V"))
    )
    (comp (ref "J202")
      (value "DF13C-6P-1.25V")
      (footprint "eagle-import:DF13C-6P-1.25V")
      (fields (field (name "PARTNO") "DF13C-6P-1.25V(20)"))
      (libsource (lib "eagle-import") (part "DF13-6P-1.25V"))
    )
    (comp (ref "J203")
      (value "DF13C-6P-1.25V")
      (footprint "eagle-import:DF13C-6P-1.25V")
      (fields (field (name "PARTNO") "DF13C-6P-1.25V(20)"))
      (libsource (lib "eagle-import") (part "DF13-6P-1.25V"))
    )
    (comp (ref "J204")
      (value "DF13C-6P-1.25V")
      (footprint "eagle-import:DF13C-6P-1.25V")
      (fields (field (name "PARTNO") "DF13C-6P-1.25V(20)"))
      (libsource (lib "eagle-import") (part "DF13-6P-1.25V"))
    )
    (comp (ref "L201")
      (value "KNH16C104DA5TS")
      (footprint "eagle-import:KYOCERA-KNH16-DA")
      (libsource (lib "eagle-import") (part "KNH16C104DA5TS"))
    )
    (comp (ref "L202")
      (value "KNH16C104DA5TS")
      (footprint "eagle-import:KYOCERA-KNH16-DA")
      (libsource (lib "eagle-import") (part "KNH16C104DA5TS"))
    )
    (comp (ref "L203")
      (value "KNH16C104DA5TS")
      (footprint "eagle-import:KYOCERA-KNH16-DA")
      (libsource (lib "eagle-import") (part "KNH16C104DA5TS"))
    )
    (comp (ref "R201")
      (value "120R")
      (footprint "eagle-import:0402-RES")
      (fields (field (name "PARTNO") "RC0402FR-07120RL"))
      (libsource (lib "eagle-import") (part "RESISTOR0402-RES"))
    )
    (comp (ref "R202")
      (value "120R")
      (footprint "eagle-import:0402-RES")
      (fields (field (name "PARTNO") "RC0402FR-07120RL"))
      (libsource (lib "eagle-import") (part "RESISTOR0402-RES"))
    )
    (comp (ref "R203")
      (value "120R")
      (footprint "eagle-import:0402-RES")
      (fields (field (name "PARTNO") "RC0402FR-07120RL"))
      (libsource (lib "eagle-import") (part "RESISTOR0402-RES"))
    )
    (comp (ref "R204")
      (value "120R")
      (footprint "eagle-import:0402-RES")
      (fields (field (name "PARTNO") "RC0402FR-07120RL"))
      (libsource (lib "eagle-import") (part "RESISTOR0402-RES"))
    )
    (comp (ref "R205")
      (value "120R")
      (footprint "eagle-import:0402-RES")
      (fields (field (name "PARTNO") "RC0402FR-07120RL"))
      (libsource (lib "eagle-import") (part "RESISTOR0402-RES"))
    )
    (comp (ref "R206")
      (value "120R")
      (footprint "eagle-import:0402-RES")
      (fields (field (name "PARTNO") "RC0402FR-07120RL"))
      (libsource (lib "eagle-import") (part "RESISTOR0402-RES"))
    )
    (comp (ref "R207")
      (value "120R")
      (footprint "eagle-import:0402-RES")
      (fields (field (name "PARTNO") "RC0402FR-07120RL"))
      (libsource (lib "eagle-import") (part "RESISTOR0402-RES"))
    )
    (comp (ref "R208")
      (value "120R")
      (footprint "eagle-import:0402-RES")
      (fields (field (name "PARTNO") "RC0402FR-07120RL"))
      (libsource (lib "eagle-import") (part "RESISTOR0402-RES"))
    )
    (comp (ref "R209")
      (value "120R")
      (footprint "eagle-import:0402-RES")
      (fields (field (name "PARTNO") "RC0402FR-07120RL"))
      (libsource (lib "eagle-import") (part "RESISTOR0402-RES"))
    )
    (comp (ref "R210")
      (value "120R")
      (footprint "eagle-import:0402-RES")
      (fields (field (name "PARTNO") "RC0402FR-07120RL"))
      (libsource (lib "eagle-import") (part "RESISTOR0402-RES"))
    )
    (comp (ref "R211")
      (value "120R")
      (footprint "eagle-import:0402-RES")
      (fields (field (name "PARTNO") "RC0402FR-07120RL"))
      (libsource (lib "eagle-import") (part "RESISTOR0402-RES"))
    )
    (comp (ref "R212")
      (value "120R")
      (footprint "eagle-import:0402-RES")
      (fields (field (name "PARTNO") "RC0402FR-07120RL"))
      (libsource (lib "eagle-import") (part "RESISTOR0402-RES"))
    )
    (comp (ref "R213")
      (value "120R")
      (footprint "eagle-import:0402-RES")
      (fields (field (name "PARTNO") "RC0402FR-07120RL"))
      (libsource (lib "eagle-import") (part "RESISTOR0402-RES"))
    )
    (comp (ref "R214")
      (value "120R")
      (footprint "eagle-import:0402-RES")
      (fields (field (name "PARTNO") "RC0402FR-07120RL"))
      (libsource (lib "eagle-import") (part "RESISTOR0402-RES"))
    )
    (comp (ref "R215")
      (value "120R")
      (footprint "eagle-import:0402-RES")
      (fields (field (name "PARTNO") "RC0402FR-07120RL"))
      (libsource (lib "eagle-import") (part "RESISTOR0402-RES"))
    )
    (comp (ref "R216")
      (value "120R")
      (footprint "eagle-import:0402-RES")
      (fields (field (name "PARTNO") "RC0402FR-07120RL"))
      (libsource (lib "eagle-import") (part "RESISTOR0402-RES"))
    )
    (comp (ref "U201")
      (value "TXS0108QFN20")
      (footprint "eagle-import:QFN20-RGY")
      (fields (field (name "PARTNO") "TXS0108ERGYR"))
      (libsource (lib "eagle-import") (part "TXS0108QFN20"))
    )
    (comp (ref "U202")
      (value "TXS0108QFN20")
      (footprint "eagle-import:QFN20-RGY")
      (fields (field (name "PARTNO") "TXS0108ERGYR"))
      (libsource (lib "eagle-import") (part "TXS0108QFN20"))
    )
    (comp (ref "C1001")
      (value "10u/25V")
      (footprint "eagle-import:0805-CAP")
      (fields (field (name "PARTNO") "CL21A106KAYNNNE"))
      (libsource (lib "eagle-import") (part "CAP0805"))
    )
    (comp (ref "C1002")
      (value "10n")
      (footprint "eagle-import:0402-CAP")
      (fields (field (name "PARTNO") "CC0402KRX7R7BB103"))
      (libsource (lib "eagle-import") (part "CAP0402"))
    )
    (comp (ref "C1003")
      (value "1u")
      (footprint "eagle-import:0603-CAP")
      (fields (field (name "PARTNO") "CC0603ZRY5V7BB105"))
      (libsource (lib "eagle-import") (part "CAP0603"))
    )
    (comp (ref "C1004")
      (value "10u")
      (footprint "eagle-import:0603-CAP")
      (fields (field (name "PARTNO") "C1608X5R1A106K080AC"))
      (libsource (lib "eagle-import") (part "CAP0603"))
    )
    (comp (ref "C1005")
      (value "0u1")
      (footprint "eagle-import:0402-CAP")
      (fields (field (name "PARTNO") "CC0402ZRY5V7BB104"))
      (libsource (lib "eagle-import") (part "CAP0402"))
    )
    (comp (ref "C1008")
      (value "2u2")
      (footprint "eagle-import:0402-CAP")
      (fields (field (name "PARTNO") "C1005X6S1C225K050BC"))
      (libsource (lib "eagle-import") (part "CAP0402"))
    )
    (comp (ref "D1001")
      (value "PMEG2005CT")
      (footprint "eagle-import:SOT23-3")
      (libsource (lib "eagle-import") (part "PMEG2005CT"))
    )
    (comp (ref "F1001")
      (value "0ZCA0035FF2G")
      (footprint "eagle-import:PTC-1206")
      (libsource (lib "eagle-import") (part "PTCSMD"))
    )
    (comp (ref "R1001")
      (value "100K")
      (footprint "eagle-import:0402-RES")
      (fields (field (name "PARTNO") "RC0402FR-07100KL"))
      (libsource (lib "eagle-import") (part "RESISTOR0402-RES"))
    )
    (comp (ref "R1002")
      (value "10K")
      (footprint "eagle-import:0402-RES")
      (fields (field (name "PARTNO") "RC0402FR-0710KL"))
      (libsource (lib "eagle-import") (part "RESISTOR0402-RES"))
    )
    (comp (ref "U1001")
      (value "BQ24313")
      (footprint "eagle-import:QFN8-DSG")
      (fields (field (name "PARTNO") "BQ24313DSGT"))
      (libsource (lib "eagle-import") (part "BQ24313"))
    )
    (comp (ref "U1002")
      (value "MIC5332")
      (footprint "eagle-import:MLF-8-EPAD")
      (fields (field (name "PARTNO") "MIC5332-SSYMT"))
      (libsource (lib "eagle-import") (part "MIC5332"))
    )
    (comp (ref "!VBUS_VALID")
      (value "PAD.04")
      (footprint "eagle-import:PAD.04X.04")
      (libsource (lib "eagle-import") (part "PAD.04"))
    )
    (comp (ref "!VDD_BRICK_VALID")
      (value "PAD.04")
      (footprint "eagle-import:PAD.04X.04")
      (libsource (lib "eagle-import") (part "PAD.04"))
    )
    (comp (ref "!VDD_SERVO_VALID")
      (value "PAD.04")
      (footprint "eagle-import:PAD.04X.04")
      (libsource (lib "eagle-import") (part "PAD.04"))
    )
    (comp (ref "ADC_PR")
      (value "PAD.04")
      (footprint "eagle-import:PAD.04X.04")
      (libsource (lib "eagle-import") (part "PAD.04"))
    )
    (comp (ref "CAN_H")
      (value "PAD.04")
      (footprint "eagle-import:PAD.04X.04")
      (libsource (lib "eagle-import") (part "PAD.04"))
    )
    (comp (ref "CAN_L")
      (value "PAD.04")
      (footprint "eagle-import:PAD.04X.04")
      (libsource (lib "eagle-import") (part "PAD.04"))
    )
    (comp (ref "FMU-BOOT1101")
      (value "PAD.04")
      (footprint "eagle-import:PAD.04X.04")
      (libsource (lib "eagle-import") (part "PAD.04"))
    )
    (comp (ref "GND")
      (value "PAD.04")
      (footprint "eagle-import:PAD.04X.04")
      (libsource (lib "eagle-import") (part "PAD.04"))
    )
    (comp (ref "GND.")
      (value "PAD.04")
      (footprint "eagle-import:PAD.04X.04")
      (libsource (lib "eagle-import") (part "PAD.04"))
    )
    (comp (ref "IO-BOOT1101")
      (value "PAD.04")
      (footprint "eagle-import:PAD.04X.04")
      (libsource (lib "eagle-import") (part "PAD.04"))
    )
    (comp (ref "JP1")
      (value "FIDUCIAL1.5X3")
      (footprint "eagle-import:FIDUCIAL-1.5X3")
      (libsource (lib "eagle-import") (part "FIDUCIAL1.5X3"))
    )
    (comp (ref "JP2")
      (value "FIDUCIAL1.5X3")
      (footprint "eagle-import:FIDUCIAL-1.5X3")
      (libsource (lib "eagle-import") (part "FIDUCIAL1.5X3"))
    )
    (comp (ref "M3_MOUNT1101")
      (value "MOUNT-HOLE3.1MM")
      (footprint "eagle-import:MOUNT-HOLE3.1")
      (libsource (lib "eagle-import") (part "MOUNT-HOLE3.1MM"))
    )
    (comp (ref "M3_MOUNT1102")
      (value "MOUNT-HOLE3.1MM")
      (footprint "eagle-import:MOUNT-HOLE3.1")
      (libsource (lib "eagle-import") (part "MOUNT-HOLE3.1MM"))
    )
    (comp (ref "M3_MOUNT1103")
      (value "MOUNT-HOLE3.1MM")
      (footprint "eagle-import:MOUNT-HOLE3.1")
      (libsource (lib "eagle-import") (part "MOUNT-HOLE3.1MM"))
    )
    (comp (ref "M3_MOUNT1104")
      (value "MOUNT-HOLE3.1MM")
      (footprint "eagle-import:MOUNT-HOLE3.1")
      (libsource (lib "eagle-import") (part "MOUNT-HOLE3.1MM"))
    )
    (comp (ref "OSHW_LOGO")
      (value "OSHW-LOGOS")
      (footprint "eagle-import:OSHW-LOGO-S")
      (libsource (lib "eagle-import") (part "OSHW-LOGOS"))
    )
    (comp (ref "S1RX")
      (value "PAD.04")
      (footprint "eagle-import:PAD.04X.04")
      (libsource (lib "eagle-import") (part "PAD.04"))
    )
    (comp (ref "S1TX")
      (value "PAD.04")
      (footprint "eagle-import:PAD.04X.04")
      (libsource (lib "eagle-import") (part "PAD.04"))
    )
    (comp (ref "S2RX")
      (value "PAD.04")
      (footprint "eagle-import:PAD.04X.04")
      (libsource (lib "eagle-import") (part "PAD.04"))
    )
    (comp (ref "S2TX")
      (value "PAD.04")
      (footprint "eagle-import:PAD.04X.04")
      (libsource (lib "eagle-import") (part "PAD.04"))
    )
    (comp (ref "S3RX")
      (value "PAD.04")
      (footprint "eagle-import:PAD.04X.04")
      (libsource (lib "eagle-import") (part "PAD.04"))
    )
    (comp (ref "S3TX")
      (value "PAD.04")
      (footprint "eagle-import:PAD.04X.04")
      (libsource (lib "eagle-import") (part "PAD.04"))
    )
    (comp (ref "S4RX")
      (value "PAD.04")
      (footprint "eagle-import:PAD.04X.04")
      (libsource (lib "eagle-import") (part "PAD.04"))
    )
    (comp (ref "S4TX")
      (value "PAD.04")
      (footprint "eagle-import:PAD.04X.04")
      (libsource (lib "eagle-import") (part "PAD.04"))
    )
    (comp (ref "S5_RX")
      (value "PAD.04")
      (footprint "eagle-import:PAD.04X.04")
      (libsource (lib "eagle-import") (part "PAD.04"))
    )
    (comp (ref "S5_TX")
      (value "PAD.04")
      (footprint "eagle-import:PAD.04X.04")
      (libsource (lib "eagle-import") (part "PAD.04"))
    )
    (comp (ref "VBUS")
      (value "PAD.04")
      (footprint "eagle-import:PAD.04X.04")
      (libsource (lib "eagle-import") (part "PAD.04"))
    )
    (comp (ref "VDDA_3V1101")
      (value "PAD.04")
      (footprint "eagle-import:PAD.04X.04")
      (libsource (lib "eagle-import") (part "PAD.04"))
    )
    (comp (ref "VDD_3V1101")
      (value "PAD.04")
      (footprint "eagle-import:PAD.04X.04")
      (libsource (lib "eagle-import") (part "PAD.04"))
    )
    (comp (ref "VDD_5V_BRICK")
      (value "PAD.04")
      (footprint "eagle-import:PAD.04X.04")
      (libsource (lib "eagle-import") (part "PAD.04"))
    )
    (comp (ref "VDD_5V_IN")
      (value "PAD.04")
      (footprint "eagle-import:PAD.04X.04")
      (libsource (lib "eagle-import") (part "PAD.04"))
    )
    (comp (ref "VDD_SERVO")
      (value "PAD.04")
      (footprint "eagle-import:PAD.04X.04")
      (libsource (lib "eagle-import") (part "PAD.04"))
    )
  )
  (nets
    (net (code "1") (name "ACCEL_DRDY") (class "Default")
      (node (ref "U101") (pin "90") (pinfunction "PB4_90") (pintype "bidirectional"))
      (node (ref "U504") (pin "11") (pinfunction "INT1_11") (pintype "bidirectional"))
      (node (ref "X503") (pin "3") (pinfunction "S_3") (pintype "passive"))
    )
    (net (code "2") (name "ALARM") (class "Default")
      (node (ref "R701") (pin "P$2") (pinfunction "2_P$2") (pintype "passive"))
      (node (ref "U101") (pin "77") (pinfunction "PA15_77") (pintype "bidirectional"))
    )
    (net (code "3") (name "BATT_CURRENT_SENS") (class "Default")
      (node (ref "R1101") (pin "P$1") (pinfunction "1_P$1") (pintype "passive"))
      (node (ref "U101") (pin "26") (pinfunction "PA3_26") (pintype "bidirectional"))
    )
    (net (code "4") (name "BATT_VOLTAGE_SENS") (class "Default")
      (node (ref "R1102") (pin "P$1") (pinfunction "1_P$1") (pintype "passive"))
      (node (ref "U101") (pin "25") (pinfunction "PA2_25") (pintype "bidirectional"))
    )
    (net (code "5") (name "CAN1_RX") (class "Default")
      (node (ref "U101") (pin "81") (pinfunction "PD0_81") (pintype "bidirectional"))
      (node (ref "U401") (pin "4") (pinfunction "DOUT_4") (pintype "output"))
    )
    (net (code "6") (name "CAN1_TX") (class "Default")
      (node (ref "U101") (pin "82") (pinfunction "PD1_82") (pintype "bidirectional"))
      (node (ref "U401") (pin "1") (pinfunction "DIN_1") (pintype "input"))
    )
    (net (code "7") (name "CAN2_RX") (class "Default")
      (node (ref "R216") (pin "P$1") (pinfunction "1_P$1") (pintype "passive"))
      (node (ref "U101") (pin "51") (pinfunction "PB12_51") (pintype "bidirectional"))
    )
    (net (code "8") (name "CAN2_TX") (class "Default")
      (node (ref "R215") (pin "P$1") (pinfunction "1_P$1") (pintype "passive"))
      (node (ref "U101") (pin "92") (pinfunction "PB6_92") (pintype "bidirectional"))
    )
    (net (code "9") (name "CAN_H") (class "Default")
      (node (ref "CAN_H") (pin "P$1") (pinfunction "P$1_P$1") (pintype "passive"))
      (node (ref "J405") (pin "2") (pinfunction "2_2") (pintype "passive"))
      (node (ref "R409") (pin "P$1") (pinfunction "1_P$1") (pintype "passive"))
      (node (ref "U401") (pin "7") (pinfunction "CANH_7") (pintype "bidirectional"))
    )
    (net (code "10") (name "CAN_L") (class "Default")
      (node (ref "CAN_L") (pin "P$1") (pinfunction "P$1_P$1") (pintype "passive"))
      (node (ref "J405") (pin "3") (pinfunction "3_3") (pintype "passive"))
      (node (ref "R409") (pin "P$2") (pinfunction "2_P$2") (pintype "passive"))
      (node (ref "U401") (pin "6") (pinfunction "CANL_6") (pintype "bidirectional"))
    )
    (net (code "11") (name "FMU-BOOT0") (class "Default")
      (node (ref "FMU-BOOT1101") (pin "P$1") (pinfunction "P$1_P$1") (pintype "passive"))
      (node (ref "R611") (pin "P$2") (pinfunction "2_P$2") (pintype "passive"))
      (node (ref "U101") (pin "94") (pinfunction "BOOT0_94") (pintype "input"))
    )
    (net (code "12") (name "FMU-CH1") (class "Default")
      (node (ref "U101") (pin "45") (pinfunction "PE14_45") (pintype "bidirectional"))
      (node (ref "U901") (pin "7") (pinfunction "A6_7") (pintype "bidirectional"))
    )
    (net (code "13") (name "FMU-CH2") (class "Default")
      (node (ref "U101") (pin "44") (pinfunction "PE13_44") (pintype "bidirectional"))
      (node (ref "U901") (pin "6") (pinfunction "A5_6") (pintype "bidirectional"))
    )
    (net (code "14") (name "FMU-CH3") (class "Default")
      (node (ref "U101") (pin "42") (pinfunction "PE11_42") (pintype "bidirectional"))
      (node (ref "U901") (pin "5") (pinfunction "A4_5") (pintype "bidirectional"))
    )
    (net (code "15") (name "FMU-CH4") (class "Default")
      (node (ref "U101") (pin "40") (pinfunction "PE9_40") (pintype "bidirectional"))
      (node (ref "U901") (pin "4") (pinfunction "A3_4") (pintype "bidirectional"))
    )
    (net (code "16") (name "FMU-CH5") (class "Default")
      (node (ref "U101") (pin "60") (pinfunction "PD13_60") (pintype "bidirectional"))
      (node (ref "U901") (pin "3") (pinfunction "A2_3") (pintype "bidirectional"))
    )
    (net (code "17") (name "FMU-CH6") (class "Default")
      (node (ref "U101") (pin "61") (pinfunction "PD14_61") (pintype "bidirectional"))
      (node (ref "U901") (pin "1") (pinfunction "A1_1") (pintype "bidirectional"))
    )
    (net (code "18") (name "FMU-I2C1_SCL") (class "Default")
      (node (ref "R401") (pin "P$1") (pinfunction "1_P$1") (pintype "passive"))
      (node (ref "R404") (pin "P$1") (pinfunction "1_P$1") (pintype "passive"))
      (node (ref "U101") (pin "95") (pinfunction "PB8_95") (pintype "bidirectional"))
    )
    (net (code "19") (name "FMU-I2C1_SDA") (class "Default")
      (node (ref "R402") (pin "P$1") (pinfunction "1_P$1") (pintype "passive"))
      (node (ref "R405") (pin "P$1") (pinfunction "1_P$1") (pintype "passive"))
      (node (ref "U101") (pin "96") (pinfunction "PB9_96") (pintype "bidirectional"))
    )
    (net (code "20") (name "FMU-I2C2_SCL") (class "Default")
      (node (ref "R306") (pin "P$1") (pinfunction "1_P$1") (pintype "passive"))
      (node (ref "U101") (pin "47") (pinfunction "PB10_47") (pintype "bidirectional"))
      (node (ref "U701") (pin "3") (pinfunction "SCL_3") (pintype "bidirectional"))
    )
    (net (code "21") (name "FMU-I2C2_SDA") (class "Default")
      (node (ref "R307") (pin "P$1") (pinfunction "1_P$1") (pintype "passive"))
      (node (ref "U101") (pin "48") (pinfunction "PB11_48") (pintype "bidirectional"))
      (node (ref "U701") (pin "2") (pinfunction "SDA_2") (pintype "bidirectional"))
    )
    (net (code "22") (name "FMU-SWCLK") (class "Default")
      (node (ref "JX301") (pin "4") (pinfunction "S_4") (pintype "passive"))
      (node (ref "U101") (pin "76") (pinfunction "PA14_76") (pintype "bidirectional"))
    )
    (net (code "23") (name "FMU-SWDIO") (class "Default")
      (node (ref "JX301") (pin "2") (pinfunction "S_2") (pintype "passive"))
      (node (ref "U101") (pin "72") (pinfunction "PA13_72") (pintype "bidirectional"))
    )
    (net (code "24") (name "FMU-SWO") (class "Default")
      (node (ref "JX301") (pin "6") (pinfunction "S_6") (pintype "passive"))
      (node (ref "U101") (pin "89") (pinfunction "PB3_89") (pintype "bidirectional"))
    )
    (net (code "25") (name "FMU-UART4_RX") (class "Default")
      (node (ref "U101") (pin "24") (pinfunction "PA1_24") (pintype "bidirectional"))
      (node (ref "U202") (pin "8") (pinfunction "A7_8") (pintype "bidirectional"))
    )
    (net (code "26") (name "FMU-UART4_TX") (class "Default")
      (node (ref "U101") (pin "23") (pinfunction "PA0_23") (pintype "bidirectional"))
      (node (ref "U202") (pin "9") (pinfunction "A8_9") (pintype "bidirectional"))
    )
    (net (code "27") (name "FMU-UART7_RX") (class "Default")
      (node (ref "U101") (pin "38") (pinfunction "PE7_38") (pintype "bidirectional"))
      (node (ref "U202") (pin "4") (pinfunction "A3_4") (pintype "bidirectional"))
    )
    (net (code "28") (name "FMU-UART7_TX") (class "Default")
      (node (ref "U101") (pin "39") (pinfunction "PE8_39") (pintype "bidirectional"))
      (node (ref "U202") (pin "5") (pinfunction "A4_5") (pintype "bidirectional"))
    )
    (net (code "29") (name "FMU-UART8_RX") (class "Default")
      (node (ref "U101") (pin "97") (pinfunction "PE0_97") (pintype "bidirectional"))
      (node (ref "U202") (pin "6") (pinfunction "A5_6") (pintype "bidirectional"))
    )
    (net (code "30") (name "FMU-UART8_TX") (class "Default")
      (node (ref "U101") (pin "98") (pinfunction "PE1_98") (pintype "bidirectional"))
      (node (ref "U202") (pin "7") (pinfunction "A6_7") (pintype "bidirectional"))
    )
    (net (code "31") (name "FMU-USART2_CTS") (class "Default")
      (node (ref "U101") (pin "84") (pinfunction "PD3_84") (pintype "bidirectional"))
      (node (ref "U201") (pin "9") (pinfunction "A8_9") (pintype "bidirectional"))
    )
    (net (code "32") (name "FMU-USART2_RTS") (class "Default")
      (node (ref "U101") (pin "85") (pinfunction "PD4_85") (pintype "bidirectional"))
      (node (ref "U201") (pin "8") (pinfunction "A7_8") (pintype "bidirectional"))
    )
    (net (code "33") (name "FMU-USART2_RX") (class "Default")
      (node (ref "U101") (pin "87") (pinfunction "PD6_87") (pintype "bidirectional"))
      (node (ref "U201") (pin "6") (pinfunction "A5_6") (pintype "bidirectional"))
    )
    (net (code "34") (name "FMU-USART2_TX") (class "Default")
      (node (ref "U101") (pin "86") (pinfunction "PD5_86") (pintype "bidirectional"))
      (node (ref "U201") (pin "7") (pinfunction "A6_7") (pintype "bidirectional"))
    )
    (net (code "35") (name "FMU-USART3_CTS") (class "Default")
      (node (ref "U101") (pin "58") (pinfunction "PD11_58") (pintype "bidirectional"))
      (node (ref "U201") (pin "3") (pinfunction "A2_3") (pintype "bidirectional"))
    )
    (net (code "36") (name "FMU-USART3_RTS") (class "Default")
      (node (ref "U101") (pin "59") (pinfunction "PD12_59") (pintype "bidirectional"))
      (node (ref "U201") (pin "1") (pinfunction "A1_1") (pintype "bidirectional"))
    )
    (net (code "37") (name "FMU-USART3_RX") (class "Default")
      (node (ref "U101") (pin "56") (pinfunction "PD9_56") (pintype "bidirectional"))
      (node (ref "U201") (pin "4") (pinfunction "A3_4") (pintype "bidirectional"))
    )
    (net (code "38") (name "FMU-USART3_TX") (class "Default")
      (node (ref "U101") (pin "55") (pinfunction "PD8_55") (pintype "bidirectional"))
      (node (ref "U201") (pin "5") (pinfunction "A4_5") (pintype "bidirectional"))
    )
    (net (code "39") (name "FMU-VDD_3V3") (class "Default")
      (node (ref "C101") (pin "P$1") (pinfunction "1_P$1") (pintype "passive"))
      (node (ref "C201") (pin "P$1") (pinfunction "1_P$1") (pintype "passive"))
      (node (ref "C202") (pin "P$1") (pinfunction "1_P$1") (pintype "passive"))
      (node (ref "C402") (pin "P$1") (pinfunction "1_P$1") (pintype "passive"))
      (node (ref "C603") (pin "P$1") (pinfunction "1_P$1") (pintype "passive"))
      (node (ref "C604") (pin "P$1") (pinfunction "1_P$1") (pintype "passive"))
      (node (ref "C606") (pin "P$1") (pinfunction "1_P$1") (pintype "passive"))
      (node (ref "C607") (pin "P$1") (pinfunction "1_P$1") (pintype "passive"))
      (node (ref "C608") (pin "P$1") (pinfunction "1_P$1") (pintype "passive"))
      (node (ref "C610") (pin "P$1") (pinfunction "1_P$1") (pintype "passive"))
      (node (ref "C612") (pin "P$1") (pinfunction "1_P$1") (pintype "passive"))
      (node (ref "C616") (pin "P$1") (pinfunction "1_P$1") (pintype "passive"))
      (node (ref "C701") (pin "P$1") (pinfunction "1_P$1") (pintype "passive"))
      (node (ref "C902") (pin "P$1") (pinfunction "1_P$1") (pintype "passive"))
      (node (ref "D602") (pin "A") (pinfunction "A_A") (pintype "passive"))
      (node (ref "JX301") (pin "1") (pinfunction "S_1") (pintype "passive"))
      (node (ref "R301") (pin "P$2") (pinfunction "2_P$2") (pintype "passive"))
      (node (ref "R302") (pin "P$2") (pinfunction "2_P$2") (pintype "passive"))
      (node (ref "R303") (pin "P$2") (pinfunction "2_P$2") (pintype "passive"))
      (node (ref "R304") (pin "P$2") (pinfunction "2_P$2") (pintype "passive"))
      (node (ref "R305") (pin "P$2") (pinfunction "2_P$2") (pintype "passive"))
      (node (ref "R306") (pin "P$2") (pinfunction "2_P$2") (pintype "passive"))
      (node (ref "R307") (pin "P$2") (pinfunction "2_P$2") (pintype "passive"))
      (node (ref "R401") (pin "P$2") (pinfunction "2_P$2") (pintype "passive"))
      (node (ref "R402") (pin "P$2") (pinfunction "2_P$2") (pintype "passive"))
      (node (ref "R602") (pin "P$2") (pinfunction "2_P$2") (pintype "passive"))
      (node (ref "R604") (pin "P$2") (pinfunction "2_P$2") (pintype "passive"))
      (node (ref "U101") (pin "100") (pinfunction "VDD_100") (pintype "power_in"))
      (node (ref "U101") (pin "11") (pinfunction "VDD_11") (pintype "power_in"))
      (node (ref "U101") (pin "19") (pinfunction "VDD_19") (pintype "power_in"))
      (node (ref "U101") (pin "21") (pinfunction "VREF+_21") (pintype "input"))
      (node (ref "U101") (pin "22") (pinfunction "VDDA_22") (pintype "power_in"))
      (node (ref "U101") (pin "28") (pinfunction "VDD_28") (pintype "power_in"))
      (node (ref "U101") (pin "50") (pinfunction "VDD_50") (pintype "power_in"))
      (node (ref "U101") (pin "75") (pinfunction "VDD_75") (pintype "power_in"))
      (node (ref "U102") (pin "3") (pinfunction "~{W}_3") (pintype "bidirectional"))
      (node (ref "U102") (pin "7") (pinfunction "~{HOLD}_7") (pintype "bidirectional"))
      (node (ref "U102") (pin "8") (pinfunction "VDD_8") (pintype "bidirectional"))
      (node (ref "U201") (pin "10") (pinfunction "OE_10") (pintype "input"))
      (node (ref "U201") (pin "19") (pinfunction "VCCB_19") (pintype "input"))
      (node (ref "U201") (pin "2") (pinfunction "VCCA_2") (pintype "input"))
      (node (ref "U202") (pin "10") (pinfunction "OE_10") (pintype "input"))
      (node (ref "U202") (pin "19") (pinfunction "VCCB_19") (pintype "input"))
      (node (ref "U202") (pin "2") (pinfunction "VCCA_2") (pintype "input"))
      (node (ref "U301") (pin "4") (pinfunction "VCC_4") (pintype "passive"))
      (node (ref "U401") (pin "3") (pinfunction "VCC_3") (pintype "input"))
      (node (ref "U603") (pin "7") (pinfunction "VOUT2_7") (pintype "bidirectional"))
      (node (ref "U701") (pin "1") (pinfunction "~{SHDN}_1") (pintype "input"))
      (node (ref "U701") (pin "10") (pinfunction "VIN_10") (pintype "power_in"))
      (node (ref "U901") (pin "10") (pinfunction "OE_10") (pintype "input"))
      (node (ref "U901") (pin "19") (pinfunction "VCCB_19") (pintype "input"))
      (node (ref "U901") (pin "2") (pinfunction "VCCA_2") (pintype "input"))
      (node (ref "VDD_3V1101") (pin "P$1") (pinfunction "P$1_P$1") (pintype "passive"))
    )
    (net (code "40") (name "FMU-~{RESET}") (class "Default")
      (node (ref "C609") (pin "P$2") (pinfunction "2_P$2") (pintype "passive"))
      (node (ref "R635") (pin "P$1") (pinfunction "1_P$1") (pintype "passive"))
      (node (ref "S601") (pin "A1") (pinfunction "1_A1") (pintype "passive"))
      (node (ref "U101") (pin "14") (pinfunction "NRST_14") (pintype "input"))
      (node (ref "U603") (pin "3") (pinfunction "POR2_3") (pintype "bidirectional"))
      (node (ref "U701") (pin "4") (pinfunction "~{RESET}_4") (pintype "input"))
    )
    (net (code "41") (name "FMU_AUX_ADC1") (class "Default")
      (node (ref "R408") (pin "P$1") (pinfunction "1_P$1") (pintype "passive"))
      (node (ref "U101") (pin "18") (pinfunction "PC3_18") (pintype "bidirectional"))
    )
    (net (code "42") (name "FMU_AUX_ADC2") (class "Default")
      (node (ref "R407") (pin "P$1") (pinfunction "1_P$1") (pintype "passive"))
      (node (ref "U101") (pin "33") (pinfunction "PC4_33") (pintype "bidirectional"))
    )
    (net (code "43") (name "FRAM_MISO") (class "Default")
      (node (ref "U101") (pin "53") (pinfunction "PB14_53") (pintype "bidirectional"))
      (node (ref "U102") (pin "2") (pinfunction "Q_2") (pintype "bidirectional"))
    )
    (net (code "44") (name "FRAM_MOSI") (class "Default")
      (node (ref "U101") (pin "54") (pinfunction "PB15_54") (pintype "bidirectional"))
      (node (ref "U102") (pin "5") (pinfunction "D_5") (pintype "bidirectional"))
    )
    (net (code "45") (name "FRAM_SCK") (class "Default")
      (node (ref "U101") (pin "52") (pinfunction "PB13_52") (pintype "bidirectional"))
      (node (ref "U102") (pin "6") (pinfunction "C_6") (pintype "bidirectional"))
    )
    (net (code "46") (name "GND") (class "Default")
      (node (ref "B601") (pin "2") (pinfunction "NEG_2") (pintype "bidirectional"))
      (node (ref "C1001") (pin "P$2") (pinfunction "2_P$2") (pintype "passive"))
      (node (ref "C1002") (pin "P$2") (pinfunction "2_P$2") (pintype "passive"))
      (node (ref "C1003") (pin "P$2") (pinfunction "2_P$2") (pintype "passive"))
      (node (ref "C1004") (pin "P$2") (pinfunction "2_P$2") (pintype "passive"))
      (node (ref "C1005") (pin "P$2") (pinfunction "2_P$2") (pintype "passive"))
      (node (ref "C1008") (pin "P$2") (pinfunction "2_P$2") (pintype "passive"))
      (node (ref "C101") (pin "P$2") (pinfunction "2_P$2") (pintype "passive"))
      (node (ref "C102") (pin "P$2") (pinfunction "2_P$2") (pintype "passive"))
      (node (ref "C103") (pin "P$1") (pinfunction "1_P$1") (pintype "passive"))
      (node (ref "C1101") (pin "P$2") (pinfunction "2_P$2") (pintype "passive"))
      (node (ref "C1102") (pin "P$2") (pinfunction "2_P$2") (pintype "passive"))
      (node (ref "C1103") (pin "P$2") (pinfunction "2_P$2") (pintype "passive"))
      (node (ref "C1104") (pin "P$2") (pinfunction "2_P$2") (pintype "passive"))
      (node (ref "C1105") (pin "P$2") (pinfunction "2_P$2") (pintype "passive"))
      (node (ref "C1106") (pin "P$2") (pinfunction "2_P$2") (pintype "passive"))
      (node (ref "C1107") (pin "P$2") (pinfunction "2_P$2") (pintype "passive"))
      (node (ref "C1108") (pin "P$2") (pinfunction "2_P$2") (pintype "passive"))
      (node (ref "C1109") (pin "P$2") (pinfunction "2_P$2") (pintype "passive"))
      (node (ref "C1110") (pin "P$2") (pinfunction "2_P$2") (pintype "passive"))
      (node (ref "C201") (pin "P$2") (pinfunction "2_P$2") (pintype "passive"))
      (node (ref "C202") (pin "P$2") (pinfunction "2_P$2") (pintype "passive"))
      (node (ref "C401") (pin "P$2") (pinfunction "2_P$2") (pintype "passive"))
      (node (ref "C402") (pin "P$2") (pinfunction "2_P$2") (pintype "passive"))
      (node (ref "C501") (pin "P$2") (pinfunction "2_P$2") (pintype "passive"))
      (node (ref "C502") (pin "P$2") (pinfunction "2_P$2") (pintype "passive"))
      (node (ref "C503") (pin "P$2") (pinfunction "2_P$2") (pintype "passive"))
      (node (ref "C504") (pin "P$2") (pinfunction "2_P$2") (pintype "passive"))
      (node (ref "C505") (pin "P$2") (pinfunction "2_P$2") (pintype "passive"))
      (node (ref "C506") (pin "P$2") (pinfunction "2_P$2") (pintype "passive"))
      (node (ref "C507") (pin "P$2") (pinfunction "2_P$2") (pintype "passive"))
      (node (ref "C508") (pin "P$2") (pinfunction "2_P$2") (pintype "passive"))
      (node (ref "C509") (pin "P$2") (pinfunction "2_P$2") (pintype "passive"))
      (node (ref "C511") (pin "P$2") (pinfunction "2_P$2") (pintype "passive"))
      (node (ref "C512") (pin "P$2") (pinfunction "2_P$2") (pintype "passive"))
      (node (ref "C513") (pin "P$2") (pinfunction "2_P$2") (pintype "passive"))
      (node (ref "C514") (pin "P$2") (pinfunction "2_P$2") (pintype "passive"))
      (node (ref "C515") (pin "P$2") (pinfunction "2_P$2") (pintype "passive"))
      (node (ref "C601") (pin "P$2") (pinfunction "2_P$2") (pintype "passive"))
      (node (ref "C602") (pin "P$1") (pinfunction "1_P$1") (pintype "passive"))
      (node (ref "C603") (pin "P$2") (pinfunction "2_P$2") (pintype "passive"))
      (node (ref "C604") (pin "P$2") (pinfunction "2_P$2") (pintype "passive"))
      (node (ref "C605") (pin "P$2") (pinfunction "2_P$2") (pintype "passive"))
      (node (ref "C606") (pin "P$2") (pinfunction "2_P$2") (pintype "passive"))
      (node (ref "C607") (pin "P$2") (pinfunction "2_P$2") (pintype "passive"))
      (node (ref "C608") (pin "P$2") (pinfunction "2_P$2") (pintype "passive"))
      (node (ref "C609") (pin "P$1") (pinfunction "1_P$1") (pintype "passive"))
      (node (ref "C610") (pin "P$2") (pinfunction "2_P$2") (pintype "passive"))
      (node (ref "C611") (pin "P$2") (pinfunction "2_P$2") (pintype "passive"))
      (node (ref "C612") (pin "P$2") (pinfunction "2_P$2") (pintype "passive"))
      (node (ref "C613") (pin "P$2") (pinfunction "2_P$2") (pintype "passive"))
      (node (ref "C614") (pin "P$2") (pinfunction "2_P$2") (pintype "passive"))
      (node (ref "C615") (pin "P$2") (pinfunction "2_P$2") (pintype "passive"))
      (node (ref "C616") (pin "P$2") (pinfunction "2_P$2") (pintype "passive"))
      (node (ref "C617") (pin "P$2") (pinfunction "2_P$2") (pintype "passive"))
      (node (ref "C618") (pin "P$2") (pinfunction "2_P$2") (pintype "passive"))
      (node (ref "C701") (pin "P$2") (pinfunction "2_P$2") (pintype "passive"))
      (node (ref "C702") (pin "P$2") (pinfunction "2_P$2") (pintype "passive"))
      (node (ref "C703") (pin "P$2") (pinfunction "2_P$2") (pintype "passive"))
      (node (ref "C704") (pin "P$2") (pinfunction "2_P$2") (pintype "passive"))
      (node (ref "C801") (pin "P$1") (pinfunction "1_P$1") (pintype "passive"))
      (node (ref "C802") (pin "P$2") (pinfunction "2_P$2") (pintype "passive"))
      (node (ref "C803") (pin "P$2") (pinfunction "2_P$2") (pintype "passive"))
      (node (ref "C804") (pin "P$2") (pinfunction "2_P$2") (pintype "passive"))
      (node (ref "C805") (pin "P$2") (pinfunction "2_P$2") (pintype "passive"))
      (node (ref "C806") (pin "P$1") (pinfunction "1_P$1") (pintype "passive"))
      (node (ref "C901") (pin "P$2") (pinfunction "2_P$2") (pintype "passive"))
      (node (ref "C902") (pin "P$2") (pinfunction "2_P$2") (pintype "passive"))
      (node (ref "C903") (pin "P$2") (pinfunction "2_P$2") (pintype "passive"))
      (node (ref "D201") (pin "A") (pinfunction "A_A") (pintype "passive"))
      (node (ref "D202") (pin "A") (pinfunction "A_A") (pintype "passive"))
      (node (ref "D203") (pin "A") (pinfunction "A_A") (pintype "passive"))
      (node (ref "D401") (pin "A") (pinfunction "A_A") (pintype "passive"))
      (node (ref "D402") (pin "A") (pinfunction "A_A") (pintype "passive"))
      (node (ref "D403") (pin "A") (pinfunction "A_A") (pintype "passive"))
      (node (ref "D404") (pin "A") (pinfunction "A_A") (pintype "passive"))
      (node (ref "D701") (pin "A") (pinfunction "A_A") (pintype "passive"))
      (node (ref "D801") (pin "A") (pinfunction "A_A") (pintype "passive"))
      (node (ref "D901") (pin "A") (pinfunction "A_A") (pintype "passive"))
      (node (ref "D902") (pin "A") (pinfunction "A_A") (pintype "passive"))
      (node (ref "D903") (pin "A") (pinfunction "A_A") (pintype "passive"))
      (node (ref "GND") (pin "P$1") (pinfunction "P$1_P$1") (pintype "passive"))
      (node (ref "GND.") (pin "P$1") (pinfunction "P$1_P$1") (pintype "passive"))
      (node (ref "J201") (pin "6") (pinfunction "6_6") (pintype "passive"))
      (node (ref "J202") (pin "6") (pinfunction "6_6") (pintype "passive"))
      (node (ref "J203") (pin "6") (pinfunction "6_6") (pintype "passive"))
      (node (ref "J204") (pin "6") (pinfunction "6_6") (pintype "passive"))
      (node (ref "J301") (pin "GND") (pinfunction "5_GND") (pintype "power_in"))
      (node (ref "J301") (pin "GND1") (pinfunction "GND1_GND1") (pintype "bidirectional"))
      (node (ref "J301") (pin "GND2") (pinfunction "GND2_GND2") (pintype "bidirectional"))
      (node (ref "J301") (pin "GND3") (pinfunction "GND3_GND3") (pintype "bidirectional"))
      (node (ref "J301") (pin "GND4") (pinfunction "GND4_GND4") (pintype "bidirectional"))
      (node (ref "J302") (pin "4") (pinfunction "4_4") (pintype "passive"))
      (node (ref "J401") (pin "4") (pinfunction "4_4") (pintype "passive"))
      (node (ref "J402") (pin "3") (pinfunction "3_3") (pintype "passive"))
      (node (ref "J403") (pin "7") (pinfunction "7_7") (pintype "passive"))
      (node (ref "J404") (pin "3") (pinfunction "3_3") (pintype "passive"))
      (node (ref "J404") (pin "5") (pinfunction "5_5") (pintype "passive"))
      (node (ref "J405") (pin "4") (pinfunction "4_4") (pintype "passive"))
      (node (ref "J601") (pin "5") (pinfunction "5_5") (pintype "passive"))
      (node (ref "J601") (pin "6") (pinfunction "6_6") (pintype "passive"))
      (node (ref "J701") (pin "2") (pinfunction "2_2") (pintype "passive"))
      (node (ref "J801") (pin "P$2") (pinfunction "P$2_P$2") (pintype "bidirectional"))
      (node (ref "J901") (pin "12") (pinfunction "S_12") (pintype "passive"))
      (node (ref "J901") (pin "15") (pinfunction "S_15") (pintype "passive"))
      (node (ref "J901") (pin "18") (pinfunction "S_18") (pintype "passive"))
      (node (ref "J901") (pin "21") (pinfunction "S_21") (pintype "passive"))
      (node (ref "J901") (pin "24") (pinfunction "S_24") (pintype "passive"))
      (node (ref "J901") (pin "27") (pinfunction "S_27") (pintype "passive"))
      (node (ref "J901") (pin "3") (pinfunction "S_3") (pintype "passive"))
      (node (ref "J901") (pin "30") (pinfunction "S_30") (pintype "passive"))
      (node (ref "J901") (pin "33") (pinfunction "S_33") (pintype "passive"))
      (node (ref "J901") (pin "36") (pinfunction "S_36") (pintype "passive"))
      (node (ref "J901") (pin "39") (pinfunction "S_39") (pintype "passive"))
      (node (ref "J901") (pin "42") (pinfunction "S_42") (pintype "passive"))
      (node (ref "J901") (pin "45") (pinfunction "S_45") (pintype "passive"))
      (node (ref "J901") (pin "48") (pinfunction "S_48") (pintype "passive"))
      (node (ref "J901") (pin "6") (pinfunction "S_6") (pintype "passive"))
      (node (ref "J901") (pin "9") (pinfunction "S_9") (pintype "passive"))
      (node (ref "JX301") (pin "3") (pinfunction "S_3") (pintype "passive"))
      (node (ref "JX301") (pin "5") (pinfunction "S_5") (pintype "passive"))
      (node (ref "JX301") (pin "9") (pinfunction "S_9") (pintype "passive"))
      (node (ref "JX801") (pin "3") (pinfunction "GND_3") (pintype "bidirectional"))
      (node (ref "JX802") (pin "3") (pinfunction "S_3") (pintype "passive"))
      (node (ref "JX802") (pin "5") (pinfunction "S_5") (pintype "passive"))
      (node (ref "JX802") (pin "9") (pinfunction "S_9") (pintype "passive"))
      (node (ref "L1101") (pin "P$3") (pinfunction "P$3_P$3") (pintype "bidirectional"))
      (node (ref "L1101") (pin "P$4") (pinfunction "P$3_P$4") (pintype "bidirectional"))
      (node (ref "L1101") (pin "P$5") (pinfunction "P$3_P$5") (pintype "bidirectional"))
      (node (ref "L1102") (pin "P$3") (pinfunction "P$3_P$3") (pintype "bidirectional"))
      (node (ref "L1102") (pin "P$4") (pinfunction "P$3_P$4") (pintype "bidirectional"))
      (node (ref "L1102") (pin "P$5") (pinfunction "P$3_P$5") (pintype "bidirectional"))
      (node (ref "L201") (pin "P$3") (pinfunction "P$3_P$3") (pintype "bidirectional"))
      (node (ref "L201") (pin "P$4") (pinfunction "P$3_P$4") (pintype "bidirectional"))
      (node (ref "L201") (pin "P$5") (pinfunction "P$3_P$5") (pintype "bidirectional"))
      (node (ref "L202") (pin "P$3") (pinfunction "P$3_P$3") (pintype "bidirectional"))
      (node (ref "L202") (pin "P$4") (pinfunction "P$3_P$4") (pintype "bidirectional"))
      (node (ref "L202") (pin "P$5") (pinfunction "P$3_P$5") (pintype "bidirectional"))
      (node (ref "L203") (pin "P$3") (pinfunction "P$3_P$3") (pintype "bidirectional"))
      (node (ref "L203") (pin "P$4") (pinfunction "P$3_P$4") (pintype "bidirectional"))
      (node (ref "L203") (pin "P$5") (pinfunction "P$3_P$5") (pintype "bidirectional"))
      (node (ref "L401") (pin "P$3") (pinfunction "P$3_P$3") (pintype "bidirectional"))
      (node (ref "L401") (pin "P$4") (pinfunction "P$3_P$4") (pintype "bidirectional"))
      (node (ref "L401") (pin "P$5") (pinfunction "P$3_P$5") (pintype "bidirectional"))
      (node (ref "L402") (pin "P$3") (pinfunction "P$3_P$3") (pintype "bidirectional"))
      (node (ref "L402") (pin "P$4") (pinfunction "P$3_P$4") (pintype "bidirectional"))
      (node (ref "L402") (pin "P$5") (pinfunction "P$3_P$5") (pintype "bidirectional"))
      (node (ref "L403") (pin "P$3") (pinfunction "P$3_P$3") (pintype "bidirectional"))
      (node (ref "L403") (pin "P$4") (pinfunction "P$3_P$4") (pintype "bidirectional"))
      (node (ref "L403") (pin "P$5") (pinfunction "P$3_P$5") (pintype "bidirectional"))
      (node (ref "L404") (pin "P$3") (pinfunction "P$3_P$3") (pintype "bidirectional"))
      (node (ref "L404") (pin "P$4") (pinfunction "P$3_P$4") (pintype "bidirectional"))
      (node (ref "L404") (pin "P$5") (pinfunction "P$3_P$5") (pintype "bidirectional"))
      (node (ref "L603") (pin "P$3") (pinfunction "P$3_P$3") (pintype "bidirectional"))
      (node (ref "L603") (pin "P$4") (pinfunction "P$3_P$4") (pintype "bidirectional"))
      (node (ref "L603") (pin "P$5") (pinfunction "P$3_P$5") (pintype "bidirectional"))
      (node (ref "L901") (pin "P$3") (pinfunction "P$3_P$3") (pintype "bidirectional"))
      (node (ref "L901") (pin "P$4") (pinfunction "P$3_P$4") (pintype "bidirectional"))
      (node (ref "L901") (pin "P$5") (pinfunction "P$3_P$5") (pintype "bidirectional"))
      (node (ref "R1001") (pin "P$1") (pinfunction "1_P$1") (pintype "passive"))
      (node (ref "R1002") (pin "P$1") (pinfunction "1_P$1") (pintype "passive"))
      (node (ref "R102") (pin "P$2") (pinfunction "2_P$2") (pintype "passive"))
      (node (ref "R1103") (pin "P$2") (pinfunction "2_P$2") (pintype "passive"))
      (node (ref "R1104") (pin "P$2") (pinfunction "2_P$2") (pintype "passive"))
      (node (ref "R1107") (pin "P$2") (pinfunction "2_P$2") (pintype "passive"))
      (node (ref "R1111") (pin "P$2") (pinfunction "2_P$2") (pintype "passive"))
      (node (ref "R1114") (pin "P$2") (pinfunction "2_P$2") (pintype "passive"))
      (node (ref "R1115") (pin "P$1") (pinfunction "1_P$1") (pintype "passive"))
      (node (ref "R403") (pin "P$1") (pinfunction "1_P$1") (pintype "passive"))
      (node (ref "R610") (pin "P$2") (pinfunction "2_P$2") (pintype "passive"))
      (node (ref "R611") (pin "P$1") (pinfunction "1_P$1") (pintype "passive"))
      (node (ref "R615") (pin "P$2") (pinfunction "2_P$2") (pintype "passive"))
      (node (ref "R616") (pin "P$2") (pinfunction "2_P$2") (pintype "passive"))
      (node (ref "R617") (pin "P$2") (pinfunction "2_P$2") (pintype "passive"))
      (node (ref "R621") (pin "1") (pinfunction "1_1") (pintype "passive"))
      (node (ref "R702") (pin "P$2") (pinfunction "2_P$2") (pintype "passive"))
      (node (ref "R704") (pin "P$1") (pinfunction "1_P$1") (pintype "passive"))
      (node (ref "R706") (pin "P$2") (pinfunction "2_P$2") (pintype "passive"))
      (node (ref "R708") (pin "P$1") (pinfunction "1_P$1") (pintype "passive"))
      (node (ref "R711") (pin "P$1") (pinfunction "1_P$1") (pintype "passive"))
      (node (ref "R713") (pin "P$2") (pinfunction "2_P$2") (pintype "passive"))
      (node (ref "R801") (pin "P$2") (pinfunction "2_P$2") (pintype "passive"))
      (node (ref "R802") (pin "P$2") (pinfunction "2_P$2") (pintype "passive"))
      (node (ref "R919") (pin "P$1") (pinfunction "1_P$1") (pintype "passive"))
      (node (ref "S601") (pin "B3") (pinfunction "2_B3") (pintype "passive"))
      (node (ref "S801") (pin "B3") (pinfunction "2_B3") (pintype "passive"))
      (node (ref "U1001") (pin "2") (pinfunction "VSS_2") (pintype "bidirectional"))
      (node (ref "U1001") (pin "5") (pinfunction "~{CE}_5") (pintype "bidirectional"))
      (node (ref "U1001") (pin "6") (pinfunction "VBAT_6") (pintype "bidirectional"))
      (node (ref "U1001") (pin "GND") (pinfunction "VSS_GND") (pintype "bidirectional"))
      (node (ref "U1001") (pin "P$2") (pinfunction "VSS_P$2") (pintype "bidirectional"))
      (node (ref "U1001") (pin "P$3") (pinfunction "VSS_P$3") (pintype "bidirectional"))
      (node (ref "U1002") (pin "2") (pinfunction "GND_2") (pintype "bidirectional"))
      (node (ref "U1002") (pin "GND") (pinfunction "GND_GND") (pintype "bidirectional"))
      (node (ref "U101") (pin "10") (pinfunction "VSS_10") (pintype "power_in"))
      (node (ref "U101") (pin "20") (pinfunction "VSSA_20") (pintype "power_in"))
      (node (ref "U101") (pin "27") (pinfunction "VSS_27") (pintype "power_in"))
      (node (ref "U101") (pin "74") (pinfunction "VSS_74") (pintype "power_in"))
      (node (ref "U101") (pin "99") (pinfunction "VSS_99") (pintype "power_in"))
      (node (ref "U102") (pin "4") (pinfunction "VSS_4") (pintype "bidirectional"))
      (node (ref "U1101") (pin "P$10") (pinfunction "GND_P$10") (pintype "bidirectional"))
      (node (ref "U1101") (pin "P$25") (pinfunction "GND_P$25") (pintype "bidirectional"))
      (node (ref "U201") (pin "11") (pinfunction "GND_11") (pintype "power_in"))
      (node (ref "U202") (pin "11") (pinfunction "GND_11") (pintype "power_in"))
      (node (ref "U301") (pin "6") (pinfunction "GND_6") (pintype "power_in"))
      (node (ref "U302") (pin "2") (pinfunction "GND_2") (pintype "bidirectional"))
      (node (ref "U401") (pin "2") (pinfunction "GND_2") (pintype "power_in"))
      (node (ref "U401") (pin "5") (pinfunction "SHDN_5") (pintype "input"))
      (node (ref "U401") (pin "8") (pinfunction "RS_8") (pintype "input"))
      (node (ref "U501") (pin "10") (pinfunction "RES_P10_GND_10") (pintype "bidirectional"))
      (node (ref "U501") (pin "11") (pinfunction "RES_P11_GND_11") (pintype "bidirectional"))
      (node (ref "U501") (pin "12") (pinfunction "RES_P12_GND_12") (pintype "bidirectional"))
      (node (ref "U501") (pin "13") (pinfunction "GND_13") (pintype "bidirectional"))
      (node (ref "U501") (pin "8") (pinfunction "RES_P8_GND_8") (pintype "bidirectional"))
      (node (ref "U501") (pin "9") (pinfunction "RES_P9_GND_9") (pintype "bidirectional"))
      (node (ref "U502") (pin "10") (pinfunction "GND_10") (pintype "bidirectional"))
      (node (ref "U502") (pin "11") (pinfunction "GND_11") (pintype "bidirectional"))
      (node (ref "U502") (pin "12") (pinfunction "GND_12") (pintype "bidirectional"))
      (node (ref "U502") (pin "13") (pinfunction "GND_13") (pintype "bidirectional"))
      (node (ref "U502") (pin "9") (pinfunction "GND_9") (pintype "bidirectional"))
      (node (ref "U504") (pin "10") (pinfunction "RSRV_10") (pintype "bidirectional"))
      (node (ref "U504") (pin "12") (pinfunction "GND_12") (pintype "bidirectional"))
      (node (ref "U504") (pin "13") (pinfunction "GND_13") (pintype "bidirectional"))
      (node (ref "U504") (pin "16") (pinfunction "GND_16") (pintype "bidirectional"))
      (node (ref "U504") (pin "5") (pinfunction "GND_5") (pintype "bidirectional"))
      (node (ref "U505") (pin "1") (pinfunction "CLKIN_1") (pintype "bidirectional"))
      (node (ref "U505") (pin "18") (pinfunction "GND_18") (pintype "bidirectional"))
      (node (ref "U506") (pin "2") (pinfunction "PS_2") (pintype "bidirectional"))
      (node (ref "U506") (pin "3") (pinfunction "GND_3") (pintype "bidirectional"))
      (node (ref "U601") (pin "2") (pinfunction "VSS_2") (pintype "bidirectional"))
      (node (ref "U601") (pin "6") (pinfunction "VBAT_6") (pintype "bidirectional"))
      (node (ref "U601") (pin "GND") (pinfunction "VSS_GND") (pintype "bidirectional"))
      (node (ref "U601") (pin "P$2") (pinfunction "VSS_P$2") (pintype "bidirectional"))
      (node (ref "U601") (pin "P$3") (pinfunction "VSS_P$3") (pintype "bidirectional"))
      (node (ref "U602") (pin "2") (pinfunction "VSS_2") (pintype "bidirectional"))
      (node (ref "U602") (pin "6") (pinfunction "VBAT_6") (pintype "bidirectional"))
      (node (ref "U602") (pin "GND") (pinfunction "VSS_GND") (pintype "bidirectional"))
      (node (ref "U602") (pin "P$2") (pinfunction "VSS_P$2") (pintype "bidirectional"))
      (node (ref "U602") (pin "P$3") (pinfunction "VSS_P$3") (pintype "bidirectional"))
      (node (ref "U603") (pin "2") (pinfunction "GND_2") (pintype "bidirectional"))
      (node (ref "U603") (pin "GND") (pinfunction "GND_GND") (pintype "bidirectional"))
      (node (ref "U701") (pin "5") (pinfunction "GND_5") (pintype "power_in"))
      (node (ref "U702") (pin "4") (pinfunction "GND_4") (pintype "power_in"))
      (node (ref "U801") (pin "23") (pinfunction "VSS_1_23") (pintype "power_in"))
      (node (ref "U801") (pin "35") (pinfunction "VSS_2_35") (pintype "power_in"))
      (node (ref "U801") (pin "47") (pinfunction "VSS_3_47") (pintype "power_in"))
      (node (ref "U801") (pin "8") (pinfunction "VSSA_8") (pintype "power_in"))
      (node (ref "U901") (pin "11") (pinfunction "GND_11") (pintype "power_in"))
      (node (ref "U902") (pin "11") (pinfunction "GND_11") (pintype "power_in"))
      (node (ref "U903") (pin "1") (pinfunction "~{1OE}_1") (pintype "input"))
      (node (ref "U903") (pin "4") (pinfunction "GND_4") (pintype "power_in"))
      (node (ref "X101") (pin "2") (pinfunction "NC_2_2") (pintype "power_in"))
      (node (ref "X101") (pin "4") (pinfunction "NC_4_4") (pintype "power_in"))
      (node (ref "X503") (pin "2") (pinfunction "S_2") (pintype "passive"))
      (node (ref "X801") (pin "2") (pinfunction "NC_2_2") (pintype "power_in"))
      (node (ref "X801") (pin "4") (pinfunction "NC_4_4") (pintype "power_in"))
    )
    (net (code "47") (name "GPIO_EXT_1") (class "Default")
      (node (ref "J403") (pin "6") (pinfunction "6_6") (pintype "passive"))
      (node (ref "U101") (pin "8") (pinfunction "PC14_8") (pintype "bidirectional"))
    )
    (net (code "48") (name "GYRO_DRDY") (class "Default")
      (node (ref "U101") (pin "35") (pinfunction "PB0_35") (pintype "bidirectional"))
      (node (ref "U501") (pin "6") (pinfunction "DRDY/INT2_6") (pintype "output"))
      (node (ref "U502") (pin "6") (pinfunction "DRDY/INT2_6") (pintype "bidirectional"))
      (node (ref "X503") (pin "5") (pinfunction "S_5") (pintype "passive"))
    )
    (net (code "49") (name "IO-BOOT0") (class "Default")
      (node (ref "IO-BOOT1101") (pin "P$1") (pinfunction "P$1_P$1") (pintype "passive"))
      (node (ref "R801") (pin "P$1") (pinfunction "1_P$1") (pintype "passive"))
      (node (ref "U801") (pin "44") (pinfunction "BOOT0_44") (pintype "input"))
    )
    (net (code "50") (name "IO-CH1") (class "Default")
      (node (ref "U801") (pin "10") (pinfunction "PA0_10") (pintype "bidirectional"))
      (node (ref "U902") (pin "9") (pinfunction "A8_9") (pintype "bidirectional"))
    )
    (net (code "51") (name "IO-CH2") (class "Default")
      (node (ref "U801") (pin "11") (pinfunction "PA1_11") (pintype "bidirectional"))
      (node (ref "U902") (pin "8") (pinfunction "A7_8") (pintype "bidirectional"))
    )
    (net (code "52") (name "IO-CH3") (class "Default")
      (node (ref "U801") (pin "45") (pinfunction "PB8_45") (pintype "bidirectional"))
      (node (ref "U902") (pin "7") (pinfunction "A6_7") (pintype "bidirectional"))
    )
    (net (code "53") (name "IO-CH4") (class "Default")
      (node (ref "U801") (pin "46") (pinfunction "PB9_46") (pintype "bidirectional"))
      (node (ref "U902") (pin "6") (pinfunction "A5_6") (pintype "bidirectional"))
    )
    (net (code "54") (name "IO-CH5") (class "Default")
      (node (ref "U801") (pin "16") (pinfunction "PA6_16") (pintype "bidirectional"))
      (node (ref "U902") (pin "5") (pinfunction "A4_5") (pintype "bidirectional"))
    )
    (net (code "55") (name "IO-CH6") (class "Default")
      (node (ref "U801") (pin "17") (pinfunction "PA7_17") (pintype "bidirectional"))
      (node (ref "U902") (pin "4") (pinfunction "A3_4") (pintype "bidirectional"))
    )
    (net (code "56") (name "IO-CH7") (class "Default")
      (node (ref "U801") (pin "18") (pinfunction "PB0_18") (pintype "bidirectional"))
      (node (ref "U902") (pin "3") (pinfunction "A2_3") (pintype "bidirectional"))
    )
    (net (code "57") (name "IO-CH8") (class "Default")
      (node (ref "U801") (pin "19") (pinfunction "PB1_19") (pintype "bidirectional"))
      (node (ref "U902") (pin "1") (pinfunction "A1_1") (pintype "bidirectional"))
    )
    (net (code "58") (name "IO-SWCLK") (class "Default")
      (node (ref "JX802") (pin "4") (pinfunction "S_4") (pintype "passive"))
      (node (ref "U801") (pin "37") (pinfunction "PA14_37") (pintype "bidirectional"))
    )
    (net (code "59") (name "IO-SWDIO") (class "Default")
      (node (ref "JX802") (pin "2") (pinfunction "S_2") (pintype "passive"))
      (node (ref "U801") (pin "34") (pinfunction "PA13_34") (pintype "bidirectional"))
    )
    (net (code "60") (name "IO-SWO") (class "Default")
      (node (ref "JX802") (pin "6") (pinfunction "S_6") (pintype "passive"))
      (node (ref "U801") (pin "39") (pinfunction "PB3_39") (pintype "bidirectional"))
    )
    (net (code "61") (name "IO-USART1_RX") (class "Default")
      (node (ref "J801") (pin "P$3") (pinfunction "P$3_P$3") (pintype "bidirectional"))
      (node (ref "JX801") (pin "2") (pinfunction "+5V_2") (pintype "bidirectional"))
      (node (ref "U801") (pin "31") (pinfunction "PA10_31") (pintype "bidirectional"))
    )
    (net (code "62") (name "IO-USART1_TX") (class "Default")
      (node (ref "JX801") (pin "1") (pinfunction "PPM_1") (pintype "bidirectional"))
      (node (ref "R101") (pin "P$2") (pinfunction "2_P$2") (pintype "passive"))
      (node (ref "U801") (pin "30") (pinfunction "PA9_30") (pintype "bidirectional"))
    )
    (net (code "63") (name "IO-VDD_3V3") (class "Default")
      (node (ref "C1003") (pin "P$1") (pinfunction "1_P$1") (pintype "passive"))
      (node (ref "C1004") (pin "P$1") (pinfunction "1_P$1") (pintype "passive"))
      (node (ref "C802") (pin "P$1") (pinfunction "1_P$1") (pintype "passive"))
      (node (ref "C803") (pin "P$1") (pinfunction "1_P$1") (pintype "passive"))
      (node (ref "C804") (pin "P$1") (pinfunction "1_P$1") (pintype "passive"))
      (node (ref "C901") (pin "P$1") (pinfunction "1_P$1") (pintype "passive"))
      (node (ref "C903") (pin "P$1") (pinfunction "1_P$1") (pintype "passive"))
      (node (ref "D701") (pin "C") (pinfunction "C_C") (pintype "passive"))
      (node (ref "J702") (pin "1") (pinfunction "1_1") (pintype "passive"))
      (node (ref "JX802") (pin "1") (pinfunction "S_1") (pintype "passive"))
      (node (ref "U1002") (pin "7") (pinfunction "VOUT2_7") (pintype "bidirectional"))
      (node (ref "U801") (pin "24") (pinfunction "VDD_1_24") (pintype "power_in"))
      (node (ref "U801") (pin "36") (pinfunction "VDD_2_36") (pintype "power_in"))
      (node (ref "U801") (pin "48") (pinfunction "VDD_3_48") (pintype "power_in"))
      (node (ref "U801") (pin "9") (pinfunction "VDDA_9") (pintype "power_in"))
      (node (ref "U902") (pin "10") (pinfunction "OE_10") (pintype "input"))
      (node (ref "U902") (pin "19") (pinfunction "VCCB_19") (pintype "input"))
      (node (ref "U902") (pin "2") (pinfunction "VCCA_2") (pintype "input"))
      (node (ref "U903") (pin "8") (pinfunction "VCC_8") (pintype "power_in"))
    )
    (net (code "64") (name "IO-VDD_5V5") (class "Default")
      (node (ref "C1001") (pin "P$1") (pinfunction "1_P$1") (pintype "passive"))
      (node (ref "C1005") (pin "P$1") (pinfunction "1_P$1") (pintype "passive"))
      (node (ref "D1001") (pin "3") (pinfunction "CC_3") (pintype "passive"))
      (node (ref "J901") (pin "2") (pinfunction "S_2") (pintype "passive"))
      (node (ref "LED702") (pin "A") (pinfunction "A_A") (pintype "passive"))
      (node (ref "LED703") (pin "A") (pinfunction "A_A") (pintype "passive"))
      (node (ref "LED705") (pin "A") (pinfunction "A_A") (pintype "passive"))
      (node (ref "U1002") (pin "1") (pinfunction "VIN_1") (pintype "bidirectional"))
      (node (ref "U1002") (pin "4") (pinfunction "EN2_4") (pintype "bidirectional"))
    )
    (net (code "65") (name "IO-~{RESET}") (class "Default")
      (node (ref "C801") (pin "P$2") (pinfunction "2_P$2") (pintype "passive"))
      (node (ref "S801") (pin "A1") (pinfunction "1_A1") (pintype "passive"))
      (node (ref "U1002") (pin "3") (pinfunction "POR2_3") (pintype "bidirectional"))
      (node (ref "U801") (pin "7") (pinfunction "NRST_7") (pintype "input"))
    )
    (net (code "66") (name "IO-~{VDD_SERVO_IN_FAULT}") (class "Default")
      (node (ref "U1001") (pin "4") (pinfunction "~{FAULT}_4") (pintype "bidirectional"))
      (node (ref "U801") (pin "38") (pinfunction "PA15_38") (pintype "bidirectional"))
    )
    (net (code "67") (name "MAG_DRDY") (class "Default")
      (node (ref "U101") (pin "36") (pinfunction "PB1_36") (pintype "bidirectional"))
      (node (ref "U504") (pin "9") (pinfunction "INT2_9") (pintype "bidirectional"))
      (node (ref "X503") (pin "4") (pinfunction "S_4") (pintype "passive"))
    )
    (net (code "68") (name "MPU_DRDY") (class "Default")
      (node (ref "U101") (pin "62") (pinfunction "PD15_62") (pintype "bidirectional"))
      (node (ref "U505") (pin "12") (pinfunction "INT_12") (pintype "bidirectional"))
    )
    (net (code "69") (name "Net-(C102-1)") (class "Default")
      (node (ref "C102") (pin "P$1") (pinfunction "1_P$1") (pintype "passive"))
      (node (ref "U101") (pin "12") (pinfunction "OSC_IN_12") (pintype "input"))
      (node (ref "X101") (pin "3") (pinfunction "3_3") (pintype "bidirectional"))
    )
    (net (code "70") (name "Net-(C103-2)") (class "Default")
      (node (ref "C103") (pin "P$2") (pinfunction "2_P$2") (pintype "passive"))
      (node (ref "U101") (pin "13") (pinfunction "OSC_OUT_13") (pintype "output"))
      (node (ref "X101") (pin "1") (pinfunction "1_1") (pintype "bidirectional"))
    )
    (net (code "71") (name "Net-(C504-1)") (class "Default")
      (node (ref "C504") (pin "P$1") (pinfunction "1_P$1") (pintype "passive"))
      (node (ref "U501") (pin "14") (pinfunction "PLLFILT_14") (pintype "bidirectional"))
    )
    (net (code "72") (name "Net-(C505-1)") (class "Default")
      (node (ref "C505") (pin "P$1") (pinfunction "1_P$1") (pintype "passive"))
      (node (ref "U502") (pin "14") (pinfunction "CAP_14") (pintype "bidirectional"))
    )
    (net (code "73") (name "Net-(C509-1)") (class "Default")
      (node (ref "C509") (pin "P$1") (pinfunction "1_P$1") (pintype "passive"))
      (node (ref "U504") (pin "15") (pinfunction "C1_15") (pintype "bidirectional"))
    )
    (net (code "74") (name "Net-(C510-1)") (class "Default")
      (node (ref "C510") (pin "P$1") (pinfunction "1_P$1") (pintype "passive"))
      (node (ref "U504") (pin "2") (pinfunction "SETC_2") (pintype "bidirectional"))
    )
    (net (code "75") (name "Net-(C510-2)") (class "Default")
      (node (ref "C510") (pin "P$2") (pinfunction "2_P$2") (pintype "passive"))
      (node (ref "U504") (pin "3") (pinfunction "SETP_3") (pintype "bidirectional"))
    )
    (net (code "76") (name "Net-(C512-1)") (class "Default")
      (node (ref "C512") (pin "P$1") (pinfunction "1_P$1") (pintype "passive"))
      (node (ref "U505") (pin "10") (pinfunction "REGOUT_10") (pintype "bidirectional"))
    )
    (net (code "77") (name "Net-(C515-1)") (class "Default")
      (node (ref "C515") (pin "P$1") (pinfunction "1_P$1") (pintype "passive"))
      (node (ref "U505") (pin "20") (pinfunction "CPOUT_20") (pintype "bidirectional"))
    )
    (net (code "78") (name "Net-(C601-1)") (class "Default")
      (node (ref "C601") (pin "P$1") (pinfunction "1_P$1") (pintype "passive"))
      (node (ref "C615") (pin "P$1") (pinfunction "1_P$1") (pintype "passive"))
      (node (ref "L603") (pin "P$2") (pinfunction "P$2_P$2") (pintype "bidirectional"))
      (node (ref "R603") (pin "P$1") (pinfunction "1_P$1") (pintype "passive"))
      (node (ref "U603") (pin "1") (pinfunction "VIN_1") (pintype "bidirectional"))
      (node (ref "U603") (pin "4") (pinfunction "EN2_4") (pintype "bidirectional"))
    )
    (net (code "79") (name "Net-(C602-2)") (class "Default")
      (node (ref "C602") (pin "P$2") (pinfunction "2_P$2") (pintype "passive"))
      (node (ref "U603") (pin "6") (pinfunction "CSET_6") (pintype "bidirectional"))
    )
    (net (code "80") (name "Net-(C611-1)") (class "Default")
      (node (ref "C611") (pin "P$1") (pinfunction "1_P$1") (pintype "passive"))
      (node (ref "U101") (pin "49") (pinfunction "VCAP_1_49") (pintype "power_in"))
    )
    (net (code "81") (name "Net-(C613-1)") (class "Default")
      (node (ref "C613") (pin "P$1") (pinfunction "1_P$1") (pintype "passive"))
      (node (ref "U101") (pin "73") (pinfunction "VCAP_2_73") (pintype "power_in"))
    )
    (net (code "82") (name "Net-(C703-1)") (class "Default")
      (node (ref "C703") (pin "P$1") (pinfunction "1_P$1") (pintype "passive"))
      (node (ref "J701") (pin "1") (pinfunction "1_1") (pintype "passive"))
      (node (ref "R703") (pin "P$1") (pinfunction "1_P$1") (pintype "passive"))
      (node (ref "U702") (pin "1") (pinfunction "OUT_1") (pintype "output"))
    )
    (net (code "83") (name "Net-(C704-1)") (class "Default")
      (node (ref "C704") (pin "P$1") (pinfunction "1_P$1") (pintype "passive"))
      (node (ref "R705") (pin "P$1") (pinfunction "1_P$1") (pintype "passive"))
      (node (ref "U702") (pin "6") (pinfunction "VCC_6") (pintype "bidirectional"))
    )
    (net (code "84") (name "Net-(C805-1)") (class "Default")
      (node (ref "C805") (pin "P$1") (pinfunction "1_P$1") (pintype "passive"))
      (node (ref "U801") (pin "5") (pinfunction "PD0/OSC<=_5") (pintype "bidirectional"))
      (node (ref "X801") (pin "3") (pinfunction "3_3") (pintype "bidirectional"))
    )
    (net (code "85") (name "Net-(C806-2)") (class "Default")
      (node (ref "C806") (pin "P$2") (pinfunction "2_P$2") (pintype "passive"))
      (node (ref "U801") (pin "6") (pinfunction "PD1/OSC=>_6") (pintype "bidirectional"))
      (node (ref "X801") (pin "1") (pinfunction "1_1") (pintype "bidirectional"))
    )
    (net (code "86") (name "Net-(C1002-1)") (class "Default")
      (node (ref "C1002") (pin "P$1") (pinfunction "1_P$1") (pintype "passive"))
      (node (ref "U1002") (pin "6") (pinfunction "CSET_6") (pintype "bidirectional"))
    )
    (net (code "87") (name "Net-(C1105-1)") (class "Default")
      (node (ref "C1105") (pin "P$1") (pinfunction "1_P$1") (pintype "passive"))
      (node (ref "U1101") (pin "P$18") (pinfunction "VS1_P$18") (pintype "bidirectional"))
      (node (ref "U1102") (pin "P$1") (pinfunction "S_P$1") (pintype "passive"))
      (node (ref "U1102") (pin "P$3") (pinfunction "S_P$3") (pintype "passive"))
    )
    (net (code "88") (name "Net-(C1106-1)") (class "Default")
      (node (ref "C1106") (pin "P$1") (pinfunction "1_P$1") (pintype "passive"))
      (node (ref "U1101") (pin "P$16") (pinfunction "VS2_P$16") (pintype "bidirectional"))
      (node (ref "U1103") (pin "P$1") (pinfunction "S_P$1") (pintype "passive"))
      (node (ref "U1103") (pin "P$3") (pinfunction "S_P$3") (pintype "passive"))
    )
    (net (code "89") (name "Net-(C1107-1)") (class "Default")
      (node (ref "C1107") (pin "P$1") (pinfunction "1_P$1") (pintype "passive"))
      (node (ref "U1101") (pin "P$14") (pinfunction "VS3_P$14") (pintype "bidirectional"))
      (node (ref "U1104") (pin "P$1") (pinfunction "S_P$1") (pintype "passive"))
      (node (ref "U1104") (pin "P$3") (pinfunction "S_P$3") (pintype "passive"))
    )
    (net (code "90") (name "Net-(C1108-1)") (class "Default")
      (node (ref "C1108") (pin "P$1") (pinfunction "1_P$1") (pintype "passive"))
      (node (ref "R1105") (pin "P$2") (pinfunction "2_P$2") (pintype "passive"))
      (node (ref "R1106") (pin "P$1") (pinfunction "1_P$1") (pintype "passive"))
      (node (ref "U1101") (pin "P$1") (pinfunction "UV1_P$1") (pintype "bidirectional"))
    )
    (net (code "91") (name "Net-(C1109-1)") (class "Default")
      (node (ref "C1109") (pin "P$1") (pinfunction "1_P$1") (pintype "passive"))
      (node (ref "R1109") (pin "P$2") (pinfunction "2_P$2") (pintype "passive"))
      (node (ref "R1110") (pin "P$1") (pinfunction "1_P$1") (pintype "passive"))
      (node (ref "U1101") (pin "P$3") (pinfunction "UV2_P$3") (pintype "bidirectional"))
    )
    (net (code "92") (name "Net-(C1110-1)") (class "Default")
      (node (ref "C1110") (pin "P$1") (pinfunction "1_P$1") (pintype "passive"))
      (node (ref "R1112") (pin "P$2") (pinfunction "2_P$2") (pintype "passive"))
      (node (ref "R1113") (pin "P$1") (pinfunction "1_P$1") (pintype "passive"))
      (node (ref "U1101") (pin "P$5") (pinfunction "UV3_P$5") (pintype "bidirectional"))
    )
    (net (code "93") (name "Net-(D201-PadC)") (class "Default")
      (node (ref "D201") (pin "C") (pinfunction "C_C") (pintype "passive"))
      (node (ref "J201") (pin "1") (pinfunction "1_1") (pintype "passive"))
      (node (ref "L201") (pin "P$2") (pinfunction "P$2_P$2") (pintype "bidirectional"))
    )
    (net (code "94") (name "Net-(D202-PadC)") (class "Default")
      (node (ref "D202") (pin "C") (pinfunction "C_C") (pintype "passive"))
      (node (ref "J202") (pin "1") (pinfunction "1_1") (pintype "passive"))
      (node (ref "L202") (pin "P$2") (pinfunction "P$2_P$2") (pintype "bidirectional"))
    )
    (net (code "95") (name "Net-(D203-PadC)") (class "Default")
      (node (ref "D203") (pin "C") (pinfunction "C_C") (pintype "passive"))
      (node (ref "J203") (pin "1") (pinfunction "1_1") (pintype "passive"))
      (node (ref "J204") (pin "1") (pinfunction "1_1") (pintype "passive"))
      (node (ref "L203") (pin "P$2") (pinfunction "P$2_P$2") (pintype "bidirectional"))
    )
    (net (code "96") (name "Net-(D401-PadC)") (class "Default")
      (node (ref "D401") (pin "C") (pinfunction "C_C") (pintype "passive"))
      (node (ref "J401") (pin "1") (pinfunction "1_1") (pintype "passive"))
      (node (ref "J402") (pin "1") (pinfunction "1_1") (pintype "passive"))
      (node (ref "L401") (pin "P$2") (pinfunction "P$2_P$2") (pintype "bidirectional"))
    )
    (net (code "97") (name "Net-(D402-PadC)") (class "Default")
      (node (ref "D402") (pin "C") (pinfunction "C_C") (pintype "passive"))
      (node (ref "J403") (pin "1") (pinfunction "1_1") (pintype "passive"))
      (node (ref "L402") (pin "P$2") (pinfunction "P$2_P$2") (pintype "bidirectional"))
    )
    (net (code "98") (name "Net-(D403-PadC)") (class "Default")
      (node (ref "D403") (pin "C") (pinfunction "C_C") (pintype "passive"))
      (node (ref "J404") (pin "1") (pinfunction "1_1") (pintype "passive"))
      (node (ref "L404") (pin "P$2") (pinfunction "P$2_P$2") (pintype "bidirectional"))
    )
    (net (code "99") (name "Net-(D404-PadC)") (class "Default")
      (node (ref "D404") (pin "C") (pinfunction "C_C") (pintype "passive"))
      (node (ref "J405") (pin "1") (pinfunction "1_1") (pintype "passive"))
      (node (ref "L403") (pin "P$2") (pinfunction "P$2_P$2") (pintype "bidirectional"))
    )
    (net (code "100") (name "Net-(D904-C)") (class "Default")
      (node (ref "D903") (pin "C") (pinfunction "C_C") (pintype "passive"))
      (node (ref "D904") (pin "CATHODE") (pinfunction "C_CATHODE") (pintype "passive"))
      (node (ref "L901") (pin "P$1") (pinfunction "P$1_P$1") (pintype "bidirectional"))
    )
    (net (code "101") (name "Net-(D1001-A1)") (class "Default")
      (node (ref "D1001") (pin "1") (pinfunction "A1_1") (pintype "passive"))
      (node (ref "F1001") (pin "2") (pinfunction "2_2") (pintype "bidirectional"))
    )
    (net (code "102") (name "Net-(D1001-A2)") (class "Default")
      (node (ref "D1001") (pin "2") (pinfunction "A2_2") (pintype "passive"))
      (node (ref "U1001") (pin "8") (pinfunction "OUT_8") (pintype "bidirectional"))
    )
    (net (code "103") (name "Net-(J301-2)") (class "Default")
      (node (ref "J301") (pin "D-") (pinfunction "2_D-") (pintype "bidirectional"))
      (node (ref "J302") (pin "3") (pinfunction "3_3") (pintype "passive"))
      (node (ref "U302") (pin "1") (pinfunction "D1I_1") (pintype "bidirectional"))
    )
    (net (code "104") (name "Net-(J301-3)") (class "Default")
      (node (ref "J301") (pin "D+") (pinfunction "3_D+") (pintype "bidirectional"))
      (node (ref "J302") (pin "2") (pinfunction "2_2") (pintype "passive"))
      (node (ref "U302") (pin "3") (pinfunction "D2I_3") (pintype "bidirectional"))
    )
    (net (code "105") (name "Net-(J901A-S)") (class "Default")
      (node (ref "J901") (pin "1") (pinfunction "S_1") (pintype "passive"))
      (node (ref "R909") (pin "P$2") (pinfunction "2_P$2") (pintype "passive"))
    )
    (net (code "106") (name "Net-(J901B-S)") (class "Default")
      (node (ref "J901") (pin "10") (pinfunction "S_10") (pintype "passive"))
      (node (ref "R914") (pin "P$2") (pinfunction "2_P$2") (pintype "passive"))
    )
    (net (code "107") (name "Net-(J901C-S)") (class "Default")
      (node (ref "J901") (pin "13") (pinfunction "S_13") (pintype "passive"))
      (node (ref "R906") (pin "P$2") (pinfunction "2_P$2") (pintype "passive"))
    )
    (net (code "108") (name "Net-(J901D-S)") (class "Default")
      (node (ref "J901") (pin "16") (pinfunction "S_16") (pintype "passive"))
      (node (ref "R915") (pin "P$2") (pinfunction "2_P$2") (pintype "passive"))
    )
    (net (code "109") (name "Net-(J901E-S)") (class "Default")
      (node (ref "J901") (pin "19") (pinfunction "S_19") (pintype "passive"))
      (node (ref "R907") (pin "P$2") (pinfunction "2_P$2") (pintype "passive"))
    )
    (net (code "110") (name "Net-(J901G-S)") (class "Default")
      (node (ref "J901") (pin "22") (pinfunction "S_22") (pintype "passive"))
      (node (ref "R916") (pin "P$2") (pinfunction "2_P$2") (pintype "passive"))
    )
    (net (code "111") (name "Net-(J901H-S)") (class "Default")
      (node (ref "J901") (pin "25") (pinfunction "S_25") (pintype "passive"))
      (node (ref "R908") (pin "P$2") (pinfunction "2_P$2") (pintype "passive"))
    )
    (net (code "112") (name "Net-(J901I-S)") (class "Default")
      (node (ref "J901") (pin "28") (pinfunction "S_28") (pintype "passive"))
      (node (ref "R917") (pin "P$2") (pinfunction "2_P$2") (pintype "passive"))
    )
    (net (code "113") (name "Net-(J901J-S)") (class "Default")
      (node (ref "J901") (pin "31") (pinfunction "S_31") (pintype "passive"))
      (node (ref "R902") (pin "P$2") (pinfunction "2_P$2") (pintype "passive"))
    )
    (net (code "114") (name "Net-(J901K-S)") (class "Default")
      (node (ref "J901") (pin "34") (pinfunction "S_34") (pintype "passive"))
      (node (ref "R911") (pin "P$2") (pinfunction "2_P$2") (pintype "passive"))
    )
    (net (code "115") (name "Net-(J901L-S)") (class "Default")
      (node (ref "J901") (pin "37") (pinfunction "S_37") (pintype "passive"))
      (node (ref "R903") (pin "P$2") (pinfunction "2_P$2") (pintype "passive"))
    )
    (net (code "116") (name "Net-(J901M-S)") (class "Default")
      (node (ref "J901") (pin "4") (pinfunction "S_4") (pintype "passive"))
      (node (ref "R910") (pin "P$2") (pinfunction "2_P$2") (pintype "passive"))
    )
    (net (code "117") (name "Net-(J901N-S)") (class "Default")
      (node (ref "J901") (pin "40") (pinfunction "S_40") (pintype "passive"))
      (node (ref "R912") (pin "P$2") (pinfunction "2_P$2") (pintype "passive"))
    )
    (net (code "118") (name "Net-(J901O-S)") (class "Default")
      (node (ref "J901") (pin "43") (pinfunction "S_43") (pintype "passive"))
      (node (ref "R904") (pin "P$2") (pinfunction "2_P$2") (pintype "passive"))
    )
    (net (code "119") (name "Net-(J901P-S)") (class "Default")
      (node (ref "J901") (pin "46") (pinfunction "S_46") (pintype "passive"))
      (node (ref "R913") (pin "P$2") (pinfunction "2_P$2") (pintype "passive"))
    )
    (net (code "120") (name "Net-(J901Q-S)") (class "Default")
      (node (ref "J901") (pin "7") (pinfunction "S_7") (pintype "passive"))
      (node (ref "R905") (pin "P$2") (pinfunction "2_P$2") (pintype "passive"))
    )
    (net (code "121") (name "Net-(L701-2)") (class "Default")
      (node (ref "L701") (pin "P$2") (pinfunction "2_P$2") (pintype "passive"))
      (node (ref "U702") (pin "5") (pinfunction "SW_5") (pintype "passive"))
    )
    (net (code "122") (name "Net-(R101-1)") (class "Default")
      (node (ref "R101") (pin "P$1") (pinfunction "1_P$1") (pintype "passive"))
      (node (ref "U101") (pin "69") (pinfunction "PA10_69") (pintype "bidirectional"))
    )
    (net (code "123") (name "Net-(R102-1)") (class "Default")
      (node (ref "R102") (pin "P$1") (pinfunction "1_P$1") (pintype "passive"))
      (node (ref "U101") (pin "37") (pinfunction "PB2_37") (pintype "bidirectional"))
    )
    (net (code "124") (name "Net-(R201-1)") (class "Default")
      (node (ref "R201") (pin "P$1") (pinfunction "1_P$1") (pintype "passive"))
      (node (ref "U201") (pin "20") (pinfunction "B1_20") (pintype "bidirectional"))
    )
    (net (code "125") (name "Net-(R202-1)") (class "Default")
      (node (ref "R202") (pin "P$1") (pinfunction "1_P$1") (pintype "passive"))
      (node (ref "U201") (pin "17") (pinfunction "B3_17") (pintype "bidirectional"))
    )
    (net (code "126") (name "Net-(R203-1)") (class "Default")
      (node (ref "R203") (pin "P$1") (pinfunction "1_P$1") (pintype "passive"))
      (node (ref "U201") (pin "15") (pinfunction "B5_15") (pintype "bidirectional"))
    )
    (net (code "127") (name "Net-(R204-1)") (class "Default")
      (node (ref "R204") (pin "P$1") (pinfunction "1_P$1") (pintype "passive"))
      (node (ref "U201") (pin "13") (pinfunction "B7_13") (pintype "bidirectional"))
    )
    (net (code "128") (name "Net-(R205-1)") (class "Default")
      (node (ref "R205") (pin "P$1") (pinfunction "1_P$1") (pintype "passive"))
      (node (ref "U202") (pin "17") (pinfunction "B3_17") (pintype "bidirectional"))
    )
    (net (code "129") (name "Net-(R206-1)") (class "Default")
      (node (ref "R206") (pin "P$1") (pinfunction "1_P$1") (pintype "passive"))
      (node (ref "U202") (pin "15") (pinfunction "B5_15") (pintype "bidirectional"))
    )
    (net (code "130") (name "Net-(R207-1)") (class "Default")
      (node (ref "R207") (pin "P$1") (pinfunction "1_P$1") (pintype "passive"))
      (node (ref "U202") (pin "13") (pinfunction "B7_13") (pintype "bidirectional"))
    )
    (net (code "131") (name "Net-(R208-1)") (class "Default")
      (node (ref "R208") (pin "P$1") (pinfunction "1_P$1") (pintype "passive"))
      (node (ref "U201") (pin "18") (pinfunction "B2_18") (pintype "bidirectional"))
    )
    (net (code "132") (name "Net-(R209-1)") (class "Default")
      (node (ref "R209") (pin "P$1") (pinfunction "1_P$1") (pintype "passive"))
      (node (ref "U201") (pin "16") (pinfunction "B4_16") (pintype "bidirectional"))
    )
    (net (code "133") (name "Net-(R210-1)") (class "Default")
      (node (ref "R210") (pin "P$1") (pinfunction "1_P$1") (pintype "passive"))
      (node (ref "U201") (pin "14") (pinfunction "B6_14") (pintype "bidirectional"))
    )
    (net (code "134") (name "Net-(R211-1)") (class "Default")
      (node (ref "R211") (pin "P$1") (pinfunction "1_P$1") (pintype "passive"))
      (node (ref "U201") (pin "12") (pinfunction "B8_12") (pintype "bidirectional"))
    )
    (net (code "135") (name "Net-(R212-1)") (class "Default")
      (node (ref "R212") (pin "P$1") (pinfunction "1_P$1") (pintype "passive"))
      (node (ref "U202") (pin "16") (pinfunction "B4_16") (pintype "bidirectional"))
    )
    (net (code "136") (name "Net-(R213-1)") (class "Default")
      (node (ref "R213") (pin "P$1") (pinfunction "1_P$1") (pintype "passive"))
      (node (ref "U202") (pin "14") (pinfunction "B6_14") (pintype "bidirectional"))
    )
    (net (code "137") (name "Net-(R214-1)") (class "Default")
      (node (ref "R214") (pin "P$1") (pinfunction "1_P$1") (pintype "passive"))
      (node (ref "U202") (pin "12") (pinfunction "B8_12") (pintype "bidirectional"))
    )
    (net (code "138") (name "Net-(R215-2)") (class "Default")
      (node (ref "J203") (pin "4") (pinfunction "4_4") (pintype "passive"))
      (node (ref "R215") (pin "P$2") (pinfunction "2_P$2") (pintype "passive"))
    )
    (net (code "139") (name "Net-(R216-2)") (class "Default")
      (node (ref "J203") (pin "5") (pinfunction "5_5") (pintype "passive"))
      (node (ref "R216") (pin "P$2") (pinfunction "2_P$2") (pintype "passive"))
    )
    (net (code "140") (name "Net-(R404-2)") (class "Default")
      (node (ref "J401") (pin "2") (pinfunction "2_2") (pintype "passive"))
      (node (ref "R404") (pin "P$2") (pinfunction "2_P$2") (pintype "passive"))
    )
    (net (code "141") (name "Net-(R405-2)") (class "Default")
      (node (ref "J401") (pin "3") (pinfunction "3_3") (pintype "passive"))
      (node (ref "R405") (pin "P$2") (pinfunction "2_P$2") (pintype "passive"))
    )
    (net (code "142") (name "Net-(R407-2)") (class "Default")
      (node (ref "J404") (pin "2") (pinfunction "2_2") (pintype "passive"))
      (node (ref "R407") (pin "P$2") (pinfunction "2_P$2") (pintype "passive"))
    )
    (net (code "143") (name "Net-(R408-2)") (class "Default")
      (node (ref "J404") (pin "4") (pinfunction "4_4") (pintype "passive"))
      (node (ref "R408") (pin "P$2") (pinfunction "2_P$2") (pintype "passive"))
    )
    (net (code "144") (name "Net-(R608-2)") (class "Default")
      (node (ref "D602") (pin "C") (pinfunction "C_C") (pintype "passive"))
      (node (ref "R608") (pin "P$2") (pinfunction "2_P$2") (pintype "passive"))
    )
    (net (code "145") (name "Net-(R616-1)") (class "Default")
      (node (ref "R616") (pin "P$1") (pinfunction "1_P$1") (pintype "passive"))
      (node (ref "U602") (pin "7") (pinfunction "ILIM_7") (pintype "bidirectional"))
    )
    (net (code "146") (name "Net-(R617-1)") (class "Default")
      (node (ref "R617") (pin "P$1") (pinfunction "1_P$1") (pintype "passive"))
      (node (ref "U601") (pin "7") (pinfunction "ILIM_7") (pintype "bidirectional"))
    )
    (net (code "147") (name "Net-(R701-1)") (class "Default")
      (node (ref "R701") (pin "P$1") (pinfunction "1_P$1") (pintype "passive"))
      (node (ref "U702") (pin "7") (pinfunction "+IN_7") (pintype "input"))
    )
    (net (code "148") (name "Net-(R702-1)") (class "Default")
      (node (ref "R702") (pin "P$1") (pinfunction "1_P$1") (pintype "passive"))
      (node (ref "R703") (pin "P$2") (pinfunction "2_P$2") (pintype "passive"))
      (node (ref "U702") (pin "8") (pinfunction "-IN_8") (pintype "input"))
    )
    (net (code "149") (name "Net-(R704-2)") (class "Default")
      (node (ref "R704") (pin "P$2") (pinfunction "2_P$2") (pintype "passive"))
      (node (ref "U701") (pin "6") (pinfunction "REXT_6") (pintype "bidirectional"))
    )
    (net (code "150") (name "Net-(R705-2)") (class "Default")
      (node (ref "R705") (pin "P$2") (pinfunction "2_P$2") (pintype "passive"))
      (node (ref "R706") (pin "P$1") (pinfunction "1_P$1") (pintype "passive"))
      (node (ref "U702") (pin "2") (pinfunction "FB_2") (pintype "bidirectional"))
    )
    (net (code "151") (name "Net-(R707-2)") (class "Default")
      (node (ref "R707") (pin "P$2") (pinfunction "2_P$2") (pintype "passive"))
      (node (ref "R735") (pin "P$1") (pinfunction "1_P$1") (pintype "passive"))
    )
    (net (code "152") (name "Net-(R708-2)") (class "Default")
      (node (ref "LED702") (pin "C") (pinfunction "C_C") (pintype "passive"))
      (node (ref "R708") (pin "P$2") (pinfunction "2_P$2") (pintype "passive"))
    )
    (net (code "153") (name "Net-(R709-2)") (class "Default")
      (node (ref "R709") (pin "P$2") (pinfunction "2_P$2") (pintype "passive"))
      (node (ref "R736") (pin "P$1") (pinfunction "1_P$1") (pintype "passive"))
    )
    (net (code "154") (name "Net-(R710-1)") (class "Default")
      (node (ref "J702") (pin "2") (pinfunction "2_2") (pintype "passive"))
      (node (ref "R710") (pin "P$1") (pinfunction "1_P$1") (pintype "passive"))
    )
    (net (code "155") (name "Net-(R711-2)") (class "Default")
      (node (ref "LED704") (pin "C") (pinfunction "C_C") (pintype "passive"))
      (node (ref "R711") (pin "P$2") (pinfunction "2_P$2") (pintype "passive"))
    )
    (net (code "156") (name "Net-(R712-2)") (class "Default")
      (node (ref "LED705") (pin "C") (pinfunction "C_C") (pintype "passive"))
      (node (ref "R712") (pin "P$2") (pinfunction "2_P$2") (pintype "passive"))
    )
    (net (code "157") (name "Net-(R735-2)") (class "Default")
      (node (ref "LED701") (pin "C") (pinfunction "C_C") (pintype "passive"))
      (node (ref "R735") (pin "P$2") (pinfunction "2_P$2") (pintype "passive"))
    )
    (net (code "158") (name "Net-(R736-2)") (class "Default")
      (node (ref "LED703") (pin "C") (pinfunction "C_C") (pintype "passive"))
      (node (ref "R736") (pin "P$2") (pinfunction "2_P$2") (pintype "passive"))
    )
    (net (code "159") (name "Net-(R802-1)") (class "Default")
      (node (ref "R802") (pin "P$1") (pinfunction "1_P$1") (pintype "passive"))
      (node (ref "U801") (pin "20") (pinfunction "PB2_20") (pintype "bidirectional"))
    )
    (net (code "160") (name "Net-(R803-1)") (class "Default")
      (node (ref "R803") (pin "P$1") (pinfunction "1_P$1") (pintype "passive"))
      (node (ref "U801") (pin "12") (pinfunction "PA2_12") (pintype "bidirectional"))
    )
    (net (code "161") (name "Net-(R804-1)") (class "Default")
      (node (ref "R804") (pin "P$1") (pinfunction "1_P$1") (pintype "passive"))
      (node (ref "U801") (pin "13") (pinfunction "PA3_13") (pintype "bidirectional"))
    )
    (net (code "162") (name "Net-(R901-2)") (class "Default")
      (node (ref "D902") (pin "C") (pinfunction "C_C") (pintype "passive"))
      (node (ref "R901") (pin "P$2") (pinfunction "2_P$2") (pintype "passive"))
      (node (ref "R910") (pin "P$1") (pinfunction "1_P$1") (pintype "passive"))
      (node (ref "U903") (pin "3") (pinfunction "2Y_3") (pintype "bidirectional"))
    )
    (net (code "163") (name "Net-(R902-1)") (class "Default")
      (node (ref "R902") (pin "P$1") (pinfunction "1_P$1") (pintype "passive"))
      (node (ref "U901") (pin "20") (pinfunction "B1_20") (pintype "bidirectional"))
    )
    (net (code "164") (name "Net-(R903-1)") (class "Default")
      (node (ref "R903") (pin "P$1") (pinfunction "1_P$1") (pintype "passive"))
      (node (ref "U901") (pin "17") (pinfunction "B3_17") (pintype "bidirectional"))
    )
    (net (code "165") (name "Net-(R904-1)") (class "Default")
      (node (ref "R904") (pin "P$1") (pinfunction "1_P$1") (pintype "passive"))
      (node (ref "U901") (pin "15") (pinfunction "B5_15") (pintype "bidirectional"))
    )
    (net (code "166") (name "Net-(R905-1)") (class "Default")
      (node (ref "R905") (pin "P$1") (pinfunction "1_P$1") (pintype "passive"))
      (node (ref "U902") (pin "20") (pinfunction "B1_20") (pintype "bidirectional"))
    )
    (net (code "167") (name "Net-(R906-1)") (class "Default")
      (node (ref "R906") (pin "P$1") (pinfunction "1_P$1") (pintype "passive"))
      (node (ref "U902") (pin "17") (pinfunction "B3_17") (pintype "bidirectional"))
    )
    (net (code "168") (name "Net-(R907-1)") (class "Default")
      (node (ref "R907") (pin "P$1") (pinfunction "1_P$1") (pintype "passive"))
      (node (ref "U902") (pin "15") (pinfunction "B5_15") (pintype "bidirectional"))
    )
    (net (code "169") (name "Net-(R908-1)") (class "Default")
      (node (ref "R908") (pin "P$1") (pinfunction "1_P$1") (pintype "passive"))
      (node (ref "U902") (pin "13") (pinfunction "B7_13") (pintype "bidirectional"))
    )
    (net (code "170") (name "Net-(R911-1)") (class "Default")
      (node (ref "R911") (pin "P$1") (pinfunction "1_P$1") (pintype "passive"))
      (node (ref "U901") (pin "18") (pinfunction "B2_18") (pintype "bidirectional"))
    )
    (net (code "171") (name "Net-(R912-1)") (class "Default")
      (node (ref "R912") (pin "P$1") (pinfunction "1_P$1") (pintype "passive"))
      (node (ref "U901") (pin "16") (pinfunction "B4_16") (pintype "bidirectional"))
    )
    (net (code "172") (name "Net-(R913-1)") (class "Default")
      (node (ref "R913") (pin "P$1") (pinfunction "1_P$1") (pintype "passive"))
      (node (ref "U901") (pin "14") (pinfunction "B6_14") (pintype "bidirectional"))
    )
    (net (code "173") (name "Net-(R914-1)") (class "Default")
      (node (ref "R914") (pin "P$1") (pinfunction "1_P$1") (pintype "passive"))
      (node (ref "U902") (pin "18") (pinfunction "B2_18") (pintype "bidirectional"))
    )
    (net (code "174") (name "Net-(R915-1)") (class "Default")
      (node (ref "R915") (pin "P$1") (pinfunction "1_P$1") (pintype "passive"))
      (node (ref "U902") (pin "16") (pinfunction "B4_16") (pintype "bidirectional"))
    )
    (net (code "175") (name "Net-(R916-1)") (class "Default")
      (node (ref "R916") (pin "P$1") (pinfunction "1_P$1") (pintype "passive"))
      (node (ref "U902") (pin "14") (pinfunction "B6_14") (pintype "bidirectional"))
    )
    (net (code "176") (name "Net-(R917-1)") (class "Default")
      (node (ref "R917") (pin "P$1") (pinfunction "1_P$1") (pintype "passive"))
      (node (ref "U902") (pin "12") (pinfunction "B8_12") (pintype "bidirectional"))
    )
    (net (code "177") (name "Net-(R918-2)") (class "Default")
      (node (ref "R918") (pin "P$2") (pinfunction "2_P$2") (pintype "passive"))
      (node (ref "R922") (pin "P$1") (pinfunction "1_P$1") (pintype "passive"))
    )
    (net (code "178") (name "Net-(R1001-2)") (class "Default")
      (node (ref "R1001") (pin "P$2") (pinfunction "2_P$2") (pintype "passive"))
      (node (ref "U1001") (pin "7") (pinfunction "ILIM_7") (pintype "bidirectional"))
    )
    (net (code "179") (name "Net-(R1101-2)") (class "Default")
      (node (ref "L1101") (pin "P$2") (pinfunction "P$2_P$2") (pintype "bidirectional"))
      (node (ref "R1101") (pin "P$2") (pinfunction "2_P$2") (pintype "passive"))
    )
    (net (code "180") (name "Net-(R1102-2)") (class "Default")
      (node (ref "L1102") (pin "P$2") (pinfunction "P$2_P$2") (pintype "bidirectional"))
      (node (ref "R1102") (pin "P$2") (pinfunction "2_P$2") (pintype "passive"))
    )
    (net (code "181") (name "Net-(R1103-1)") (class "Default")
      (node (ref "J601") (pin "4") (pinfunction "4_4") (pintype "passive"))
      (node (ref "L1102") (pin "P$1") (pinfunction "P$1_P$1") (pintype "bidirectional"))
      (node (ref "R1103") (pin "P$1") (pinfunction "1_P$1") (pintype "passive"))
    )
    (net (code "182") (name "Net-(R1104-1)") (class "Default")
      (node (ref "J601") (pin "3") (pinfunction "3_3") (pintype "passive"))
      (node (ref "L1101") (pin "P$1") (pinfunction "P$1_P$1") (pintype "bidirectional"))
      (node (ref "R1104") (pin "P$1") (pinfunction "1_P$1") (pintype "passive"))
    )
    (net (code "183") (name "Net-(R1106-2)") (class "Default")
      (node (ref "R1106") (pin "P$2") (pinfunction "2_P$2") (pintype "passive"))
      (node (ref "R1107") (pin "P$1") (pinfunction "1_P$1") (pintype "passive"))
      (node (ref "U1101") (pin "P$2") (pinfunction "OV1_P$2") (pintype "bidirectional"))
    )
    (net (code "184") (name "Net-(R1110-2)") (class "Default")
      (node (ref "R1110") (pin "P$2") (pinfunction "2_P$2") (pintype "passive"))
      (node (ref "R1111") (pin "P$1") (pinfunction "1_P$1") (pintype "passive"))
      (node (ref "U1101") (pin "P$4") (pinfunction "OV2_P$4") (pintype "bidirectional"))
    )
    (net (code "185") (name "Net-(R1113-2)") (class "Default")
      (node (ref "R1113") (pin "P$2") (pinfunction "2_P$2") (pintype "passive"))
      (node (ref "R1114") (pin "P$1") (pinfunction "1_P$1") (pintype "passive"))
      (node (ref "U1101") (pin "P$6") (pinfunction "OV3_P$6") (pintype "bidirectional"))
    )
    (net (code "186") (name "Net-(R1115-2)") (class "Default")
      (node (ref "R1115") (pin "P$2") (pinfunction "2_P$2") (pintype "passive"))
      (node (ref "U1101") (pin "P$24") (pinfunction "HYS_P$24") (pintype "bidirectional"))
    )
    (net (code "187") (name "Net-(U701-OUT0)") (class "Default")
      (node (ref "U701") (pin "9") (pinfunction "OUT0_9") (pintype "open_collector"))
      (node (ref "U703") (pin "C1") (pinfunction "C_C1") (pintype "passive"))
    )
    (net (code "188") (name "Net-(U701-OUT1)") (class "Default")
      (node (ref "U701") (pin "8") (pinfunction "OUT1_8") (pintype "open_collector"))
      (node (ref "U703") (pin "C2") (pinfunction "C_C2") (pintype "passive"))
    )
    (net (code "189") (name "Net-(U701-OUT2)") (class "Default")
      (node (ref "U701") (pin "7") (pinfunction "OUT2_7") (pintype "open_collector"))
      (node (ref "U703") (pin "C3") (pinfunction "C_C3") (pintype "passive"))
    )
    (net (code "190") (name "Net-(U1101-G1)") (class "Default")
      (node (ref "U1101") (pin "P$17") (pinfunction "G1_P$17") (pintype "bidirectional"))
      (node (ref "U1102") (pin "P$2") (pinfunction "G_P$2") (pintype "passive"))
      (node (ref "U1102") (pin "P$4") (pinfunction "G_P$4") (pintype "passive"))
    )
    (net (code "191") (name "Net-(U1101-G2)") (class "Default")
      (node (ref "U1101") (pin "P$15") (pinfunction "G2_P$15") (pintype "bidirectional"))
      (node (ref "U1103") (pin "P$2") (pinfunction "G_P$2") (pintype "passive"))
      (node (ref "U1103") (pin "P$4") (pinfunction "G_P$4") (pintype "passive"))
    )
    (net (code "192") (name "Net-(U1101-G3)") (class "Default")
      (node (ref "U1101") (pin "P$13") (pinfunction "G3_P$13") (pintype "bidirectional"))
      (node (ref "U1104") (pin "P$2") (pinfunction "G_P$2") (pintype "passive"))
      (node (ref "U1104") (pin "P$4") (pinfunction "G_P$4") (pintype "passive"))
    )
    (net (code "193") (name "OTG_FS_DM") (class "Default")
      (node (ref "U101") (pin "70") (pinfunction "PA11_70") (pintype "bidirectional"))
      (node (ref "U302") (pin "6") (pinfunction "D1O_6") (pintype "bidirectional"))
    )
    (net (code "194") (name "OTG_FS_DP") (class "Default")
      (node (ref "U101") (pin "71") (pinfunction "PA12_71") (pintype "bidirectional"))
      (node (ref "U302") (pin "4") (pinfunction "D2O_4") (pintype "bidirectional"))
    )
    (net (code "195") (name "PPM_INPUT") (class "Default")
      (node (ref "D901") (pin "C") (pinfunction "C_C") (pintype "passive"))
      (node (ref "R909") (pin "P$1") (pinfunction "1_P$1") (pintype "passive"))
      (node (ref "U801") (pin "29") (pinfunction "PA8_29") (pintype "bidirectional"))
      (node (ref "U903") (pin "2") (pinfunction "1A_2") (pintype "bidirectional"))
    )
    (net (code "196") (name "PRESSURE_SENS") (class "Default")
      (node (ref "C401") (pin "P$1") (pinfunction "1_P$1") (pintype "passive"))
      (node (ref "R403") (pin "P$2") (pinfunction "2_P$2") (pintype "passive"))
      (node (ref "R406") (pin "P$1") (pinfunction "1_P$1") (pintype "passive"))
      (node (ref "U101") (pin "34") (pinfunction "PC5_34") (pintype "bidirectional"))
    )
    (net (code "197") (name "PRESSURE_SENS_IN") (class "Default")
      (node (ref "ADC_PR") (pin "P$1") (pinfunction "P$1_P$1") (pintype "passive"))
      (node (ref "J402") (pin "2") (pinfunction "2_2") (pintype "passive"))
      (node (ref "R406") (pin "P$2") (pinfunction "2_P$2") (pintype "passive"))
    )
    (net (code "198") (name "RSSI_IN") (class "Default")
      (node (ref "R901") (pin "P$1") (pinfunction "1_P$1") (pintype "passive"))
      (node (ref "U801") (pin "15") (pinfunction "PA5_15") (pintype "bidirectional"))
      (node (ref "U801") (pin "33") (pinfunction "PA12_33") (pintype "bidirectional"))
    )
    (net (code "199") (name "SAFETY") (class "Default")
      (node (ref "J702") (pin "3") (pinfunction "3_3") (pintype "passive"))
      (node (ref "R713") (pin "P$1") (pinfunction "1_P$1") (pintype "passive"))
      (node (ref "U801") (pin "41") (pinfunction "PB5_41") (pintype "bidirectional"))
    )
    (net (code "200") (name "SBUS_INPUT") (class "Default")
      (node (ref "U801") (pin "22") (pinfunction "PB11_22") (pintype "bidirectional"))
      (node (ref "U903") (pin "6") (pinfunction "1Y_6") (pintype "bidirectional"))
    )
    (net (code "201") (name "SBUS_OUTPUT") (class "Default")
      (node (ref "U801") (pin "21") (pinfunction "PB10_21") (pintype "bidirectional"))
      (node (ref "U903") (pin "5") (pinfunction "2A_5") (pintype "bidirectional"))
    )
    (net (code "202") (name "SDIO_CK") (class "Default")
      (node (ref "U101") (pin "80") (pinfunction "PC12_80") (pintype "bidirectional"))
      (node (ref "U301") (pin "5") (pinfunction "CLK_5") (pintype "bidirectional"))
    )
    (net (code "203") (name "SDIO_CMD") (class "Default")
      (node (ref "R303") (pin "P$1") (pinfunction "1_P$1") (pintype "passive"))
      (node (ref "U101") (pin "83") (pinfunction "PD2_83") (pintype "bidirectional"))
      (node (ref "U301") (pin "3") (pinfunction "CMD_3") (pintype "bidirectional"))
    )
    (net (code "204") (name "SDIO_D0") (class "Default")
      (node (ref "R304") (pin "P$1") (pinfunction "1_P$1") (pintype "passive"))
      (node (ref "U101") (pin "65") (pinfunction "PC8_65") (pintype "bidirectional"))
      (node (ref "U301") (pin "7") (pinfunction "D0_7") (pintype "bidirectional"))
    )
    (net (code "205") (name "SDIO_D1") (class "Default")
      (node (ref "R305") (pin "P$1") (pinfunction "1_P$1") (pintype "passive"))
      (node (ref "U101") (pin "66") (pinfunction "PC9_66") (pintype "bidirectional"))
      (node (ref "U301") (pin "8") (pinfunction "D1_8") (pintype "bidirectional"))
    )
    (net (code "206") (name "SDIO_D2") (class "Default")
      (node (ref "R301") (pin "P$1") (pinfunction "1_P$1") (pintype "passive"))
      (node (ref "U101") (pin "78") (pinfunction "PC10_78") (pintype "bidirectional"))
      (node (ref "U301") (pin "1") (pinfunction "D2_1") (pintype "bidirectional"))
    )
    (net (code "207") (name "SDIO_D3") (class "Default")
      (node (ref "R302") (pin "P$1") (pinfunction "1_P$1") (pintype "passive"))
      (node (ref "U101") (pin "79") (pinfunction "PC11_79") (pintype "bidirectional"))
      (node (ref "U301") (pin "2") (pinfunction "D3_2") (pintype "bidirectional"))
    )
    (net (code "208") (name "SERIAL1_CTS") (class "Default")
      (node (ref "J201") (pin "4") (pinfunction "4_4") (pintype "passive"))
      (node (ref "R211") (pin "P$2") (pinfunction "2_P$2") (pintype "passive"))
    )
    (net (code "209") (name "SERIAL1_RTS") (class "Default")
      (node (ref "J201") (pin "5") (pinfunction "5_5") (pintype "passive"))
      (node (ref "R204") (pin "P$2") (pinfunction "2_P$2") (pintype "passive"))
    )
    (net (code "210") (name "SERIAL1_RX") (class "Default")
      (node (ref "J201") (pin "3") (pinfunction "3_3") (pintype "passive"))
      (node (ref "R203") (pin "P$2") (pinfunction "2_P$2") (pintype "passive"))
      (node (ref "S1RX") (pin "P$1") (pinfunction "P$1_P$1") (pintype "passive"))
    )
    (net (code "211") (name "SERIAL1_TX") (class "Default")
      (node (ref "J201") (pin "2") (pinfunction "2_2") (pintype "passive"))
      (node (ref "R210") (pin "P$2") (pinfunction "2_P$2") (pintype "passive"))
      (node (ref "S1TX") (pin "P$1") (pinfunction "P$1_P$1") (pintype "passive"))
    )
    (net (code "212") (name "SERIAL2_CTS") (class "Default")
      (node (ref "J202") (pin "4") (pinfunction "4_4") (pintype "passive"))
      (node (ref "R208") (pin "P$2") (pinfunction "2_P$2") (pintype "passive"))
    )
    (net (code "213") (name "SERIAL2_RTS") (class "Default")
      (node (ref "J202") (pin "5") (pinfunction "5_5") (pintype "passive"))
      (node (ref "R201") (pin "P$2") (pinfunction "2_P$2") (pintype "passive"))
    )
    (net (code "214") (name "SERIAL2_RX") (class "Default")
      (node (ref "J202") (pin "3") (pinfunction "3_3") (pintype "passive"))
      (node (ref "R202") (pin "P$2") (pinfunction "2_P$2") (pintype "passive"))
      (node (ref "S2RX") (pin "P$1") (pinfunction "P$1_P$1") (pintype "passive"))
    )
    (net (code "215") (name "SERIAL2_TX") (class "Default")
      (node (ref "J202") (pin "2") (pinfunction "2_2") (pintype "passive"))
      (node (ref "R209") (pin "P$2") (pinfunction "2_P$2") (pintype "passive"))
      (node (ref "S2TX") (pin "P$1") (pinfunction "P$1_P$1") (pintype "passive"))
    )
    (net (code "216") (name "SERIAL3_RX") (class "Default")
      (node (ref "J203") (pin "3") (pinfunction "3_3") (pintype "passive"))
      (node (ref "R207") (pin "P$2") (pinfunction "2_P$2") (pintype "passive"))
      (node (ref "S3RX") (pin "P$1") (pinfunction "P$1_P$1") (pintype "passive"))
    )
    (net (code "217") (name "SERIAL3_TX") (class "Default")
      (node (ref "J203") (pin "2") (pinfunction "2_2") (pintype "passive"))
      (node (ref "R214") (pin "P$2") (pinfunction "2_P$2") (pintype "passive"))
      (node (ref "S3TX") (pin "P$1") (pinfunction "P$1_P$1") (pintype "passive"))
    )
    (net (code "218") (name "SERIAL4_RX") (class "Default")
      (node (ref "J204") (pin "3") (pinfunction "3_3") (pintype "passive"))
      (node (ref "R206") (pin "P$2") (pinfunction "2_P$2") (pintype "passive"))
      (node (ref "S4RX") (pin "P$1") (pinfunction "P$1_P$1") (pintype "passive"))
    )
    (net (code "219") (name "SERIAL4_TX") (class "Default")
      (node (ref "J204") (pin "2") (pinfunction "2_2") (pintype "passive"))
      (node (ref "R213") (pin "P$2") (pinfunction "2_P$2") (pintype "passive"))
      (node (ref "S4TX") (pin "P$1") (pinfunction "P$1_P$1") (pintype "passive"))
    )
    (net (code "220") (name "SERIAL5_RX") (class "Default")
      (node (ref "J204") (pin "5") (pinfunction "5_5") (pintype "passive"))
      (node (ref "R205") (pin "P$2") (pinfunction "2_P$2") (pintype "passive"))
      (node (ref "S5_RX") (pin "P$1") (pinfunction "P$1_P$1") (pintype "passive"))
    )
    (net (code "221") (name "SERIAL5_TX") (class "Default")
      (node (ref "J204") (pin "4") (pinfunction "4_4") (pintype "passive"))
      (node (ref "R212") (pin "P$2") (pinfunction "2_P$2") (pintype "passive"))
      (node (ref "S5_TX") (pin "P$1") (pinfunction "P$1_P$1") (pintype "passive"))
    )
    (net (code "222") (name "SERIAL_FMU_TO_IO") (class "Default")
      (node (ref "R804") (pin "P$2") (pinfunction "2_P$2") (pintype "passive"))
      (node (ref "U101") (pin "63") (pinfunction "PC6_63") (pintype "bidirectional"))
    )
    (net (code "223") (name "SERIAL_IO_TO_FMU") (class "Default")
      (node (ref "R803") (pin "P$2") (pinfunction "2_P$2") (pintype "passive"))
      (node (ref "U101") (pin "64") (pinfunction "PC7_64") (pintype "bidirectional"))
    )
    (net (code "224") (name "SPI_EXT_MISO") (class "Default")
      (node (ref "J403") (pin "3") (pinfunction "3_3") (pintype "passive"))
      (node (ref "U101") (pin "4") (pinfunction "PE5_4") (pintype "bidirectional"))
    )
    (net (code "225") (name "SPI_EXT_MOSI") (class "Default")
      (node (ref "J403") (pin "4") (pinfunction "4_4") (pintype "passive"))
      (node (ref "U101") (pin "5") (pinfunction "PE6_5") (pintype "bidirectional"))
    )
    (net (code "226") (name "SPI_EXT_SCK") (class "Default")
      (node (ref "J403") (pin "2") (pinfunction "2_2") (pintype "passive"))
      (node (ref "U101") (pin "1") (pinfunction "PE2_1") (pintype "bidirectional"))
    )
    (net (code "227") (name "SPI_INT_MISO") (class "Default")
      (node (ref "U101") (pin "31") (pinfunction "PA6_31") (pintype "bidirectional"))
      (node (ref "U501") (pin "4") (pinfunction "SDO/SA0_4") (pintype "bidirectional"))
      (node (ref "U502") (pin "4") (pinfunction "SDO/SA0_4") (pintype "bidirectional"))
      (node (ref "U504") (pin "7") (pinfunction "SDO/SA0_7") (pintype "bidirectional"))
      (node (ref "U505") (pin "9") (pinfunction "AD0/SDO_9") (pintype "bidirectional"))
      (node (ref "U506") (pin "6") (pinfunction "SDO_6") (pintype "bidirectional"))
      (node (ref "X503") (pin "9") (pinfunction "S_9") (pintype "passive"))
    )
    (net (code "228") (name "SPI_INT_MOSI") (class "Default")
      (node (ref "U101") (pin "32") (pinfunction "PA7_32") (pintype "bidirectional"))
      (node (ref "U501") (pin "3") (pinfunction "SDA/SDI/SDO_3") (pintype "bidirectional"))
      (node (ref "U502") (pin "3") (pinfunction "SDA/SDI/SDO_3") (pintype "bidirectional"))
      (node (ref "U504") (pin "6") (pinfunction "SDA/SDI/SDO_6") (pintype "bidirectional"))
      (node (ref "U505") (pin "24") (pinfunction "SDA/SDI_24") (pintype "bidirectional"))
      (node (ref "U506") (pin "7") (pinfunction "SDI/SDA_7") (pintype "bidirectional"))
      (node (ref "X503") (pin "8") (pinfunction "S_8") (pintype "passive"))
    )
    (net (code "229") (name "SPI_INT_SCK") (class "Default")
      (node (ref "U101") (pin "30") (pinfunction "PA5_30") (pintype "bidirectional"))
      (node (ref "U501") (pin "2") (pinfunction "SCL/SPC_2") (pintype "input"))
      (node (ref "U502") (pin "2") (pinfunction "SCL/SPC_2") (pintype "bidirectional"))
      (node (ref "U504") (pin "4") (pinfunction "SCL/SPC_4") (pintype "bidirectional"))
      (node (ref "U505") (pin "23") (pinfunction "SCL/SCLK_23") (pintype "bidirectional"))
      (node (ref "U506") (pin "8") (pinfunction "SCLK_8") (pintype "bidirectional"))
      (node (ref "X503") (pin "10") (pinfunction "S_10") (pintype "passive"))
    )
    (net (code "230") (name "VBAT") (class "Default")
      (node (ref "B601") (pin "1") (pinfunction "POS_1") (pintype "bidirectional"))
      (node (ref "R608") (pin "P$1") (pinfunction "1_P$1") (pintype "passive"))
      (node (ref "U101") (pin "6") (pinfunction "VBAT_6") (pintype "power_in"))
      (node (ref "U801") (pin "1") (pinfunction "VBAT_1") (pintype "power_in"))
    )
    (net (code "231") (name "VBUS") (class "Default")
      (node (ref "C1103") (pin "P$1") (pinfunction "1_P$1") (pintype "passive"))
      (node (ref "J301") (pin "VBUS") (pinfunction "1_VBUS") (pintype "power_in"))
      (node (ref "J302") (pin "1") (pinfunction "1_1") (pintype "passive"))
      (node (ref "R1112") (pin "P$1") (pinfunction "1_P$1") (pintype "passive"))
      (node (ref "U101") (pin "68") (pinfunction "PA9_68") (pintype "bidirectional"))
      (node (ref "U1101") (pin "P$19") (pinfunction "V3_P$19") (pintype "bidirectional"))
      (node (ref "U1104") (pin "P$7") (pinfunction "D_P$7") (pintype "passive"))
      (node (ref "U1104") (pin "P$8") (pinfunction "D_P$8") (pintype "passive"))
      (node (ref "U302") (pin "5") (pinfunction "VBUS_5") (pintype "bidirectional"))
      (node (ref "VBUS") (pin "P$1") (pinfunction "P$1_P$1") (pintype "passive"))
    )
    (net (code "232") (name "VDD_3V3_SENSORS") (class "Default")
      (node (ref "C501") (pin "P$1") (pinfunction "1_P$1") (pintype "passive"))
      (node (ref "C502") (pin "P$1") (pinfunction "1_P$1") (pintype "passive"))
      (node (ref "C503") (pin "P$1") (pinfunction "1_P$1") (pintype "passive"))
      (node (ref "C506") (pin "P$1") (pinfunction "1_P$1") (pintype "passive"))
      (node (ref "C507") (pin "P$1") (pinfunction "1_P$1") (pintype "passive"))
      (node (ref "C508") (pin "P$1") (pinfunction "1_P$1") (pintype "passive"))
      (node (ref "C511") (pin "P$1") (pinfunction "1_P$1") (pintype "passive"))
      (node (ref "C513") (pin "P$1") (pinfunction "1_P$1") (pintype "passive"))
      (node (ref "C514") (pin "P$1") (pinfunction "1_P$1") (pintype "passive"))
      (node (ref "C605") (pin "P$1") (pinfunction "1_P$1") (pintype "passive"))
      (node (ref "C617") (pin "P$1") (pinfunction "1_P$1") (pintype "passive"))
      (node (ref "R621") (pin "2") (pinfunction "2_2") (pintype "passive"))
      (node (ref "U501") (pin "1") (pinfunction "VDD_IO_1") (pintype "bidirectional"))
      (node (ref "U501") (pin "15") (pinfunction "RES_P15_VDD_15") (pintype "bidirectional"))
      (node (ref "U501") (pin "16") (pinfunction "VDD_16") (pintype "bidirectional"))
      (node (ref "U502") (pin "1") (pinfunction "VDD_IO_1") (pintype "bidirectional"))
      (node (ref "U502") (pin "15") (pinfunction "VDD_15") (pintype "bidirectional"))
      (node (ref "U502") (pin "16") (pinfunction "VDD_16") (pintype "bidirectional"))
      (node (ref "U504") (pin "1") (pinfunction "VDD_IO_1") (pintype "bidirectional"))
      (node (ref "U504") (pin "14") (pinfunction "VDD_14") (pintype "bidirectional"))
      (node (ref "U505") (pin "13") (pinfunction "VDD_13") (pintype "bidirectional"))
      (node (ref "U506") (pin "1") (pinfunction "VDD_1") (pintype "bidirectional"))
      (node (ref "U603") (pin "8") (pinfunction "VOUT1_8") (pintype "bidirectional"))
      (node (ref "VDDA_3V1101") (pin "P$1") (pinfunction "P$1_P$1") (pintype "passive"))
      (node (ref "X503") (pin "1") (pinfunction "S_1") (pintype "passive"))
    )
    (net (code "233") (name "VDD_3V3_SENSORS_EN") (class "Default")
      (node (ref "R603") (pin "P$2") (pinfunction "2_P$2") (pintype "passive"))
      (node (ref "R635") (pin "P$2") (pinfunction "2_P$2") (pintype "passive"))
      (node (ref "U101") (pin "2") (pinfunction "PE3_2") (pintype "bidirectional"))
      (node (ref "U603") (pin "5") (pinfunction "EN1_5") (pintype "bidirectional"))
    )
    (net (code "234") (name "VDD_3V3_SPEKTRUM") (class "Default")
      (node (ref "C1008") (pin "P$1") (pinfunction "1_P$1") (pintype "passive"))
      (node (ref "D801") (pin "C") (pinfunction "C_C") (pintype "passive"))
      (node (ref "J801") (pin "P$1") (pinfunction "P$1_P$1") (pintype "bidirectional"))
      (node (ref "U1002") (pin "8") (pinfunction "VOUT1_8") (pintype "bidirectional"))
    )
    (net (code "235") (name "VDD_3V3_SPEKTRUM_EN") (class "Default")
      (node (ref "R1002") (pin "P$2") (pinfunction "2_P$2") (pintype "passive"))
      (node (ref "U1002") (pin "5") (pinfunction "EN1_5") (pintype "bidirectional"))
      (node (ref "U801") (pin "2") (pinfunction "PC13_2") (pintype "bidirectional"))
    )
    (net (code "236") (name "VDD_5V_BRICK") (class "Default")
      (node (ref "C1101") (pin "P$1") (pinfunction "1_P$1") (pintype "passive"))
      (node (ref "J601") (pin "1") (pinfunction "1_1") (pintype "passive"))
      (node (ref "J601") (pin "2") (pinfunction "2_2") (pintype "passive"))
      (node (ref "R1105") (pin "P$1") (pinfunction "1_P$1") (pintype "passive"))
      (node (ref "U1101") (pin "P$21") (pinfunction "V1_P$21") (pintype "bidirectional"))
      (node (ref "U1102") (pin "P$7") (pinfunction "D_P$7") (pintype "passive"))
      (node (ref "U1102") (pin "P$8") (pinfunction "D_P$8") (pintype "passive"))
      (node (ref "VDD_5V_BRICK") (pin "P$1") (pinfunction "P$1_P$1") (pintype "passive"))
    )
    (net (code "237") (name "VDD_5V_HIPOWER") (class "Default")
      (node (ref "C614") (pin "P$1") (pinfunction "1_P$1") (pintype "passive"))
      (node (ref "L201") (pin "P$1") (pinfunction "P$1_P$1") (pintype "bidirectional"))
      (node (ref "U601") (pin "8") (pinfunction "OUT_8") (pintype "bidirectional"))
    )
    (net (code "238") (name "VDD_5V_IN") (class "Default")
      (node (ref "C1104") (pin "P$1") (pinfunction "1_P$1") (pintype "passive"))
      (node (ref "C702") (pin "P$1") (pinfunction "1_P$1") (pintype "passive"))
      (node (ref "F1001") (pin "1") (pinfunction "1_1") (pintype "bidirectional"))
      (node (ref "L603") (pin "P$1") (pinfunction "P$1_P$1") (pintype "bidirectional"))
      (node (ref "L701") (pin "P$1") (pinfunction "1_P$1") (pintype "passive"))
      (node (ref "LED701") (pin "A") (pinfunction "A_A") (pintype "passive"))
      (node (ref "LED704") (pin "A") (pinfunction "A_A") (pintype "passive"))
      (node (ref "R609") (pin "P$2") (pinfunction "2_P$2") (pintype "passive"))
      (node (ref "RN1101") (pin "5") (pinfunction "2_5") (pintype "passive"))
      (node (ref "RN1101") (pin "6") (pinfunction "2_6") (pintype "passive"))
      (node (ref "RN1101") (pin "7") (pinfunction "2_7") (pintype "passive"))
      (node (ref "U1101") (pin "P$12") (pinfunction "VOUT_P$12") (pintype "bidirectional"))
      (node (ref "U1102") (pin "P$5") (pinfunction "D_P$5") (pintype "passive"))
      (node (ref "U1102") (pin "P$6") (pinfunction "D_P$6") (pintype "passive"))
      (node (ref "U1103") (pin "P$5") (pinfunction "D_P$5") (pintype "passive"))
      (node (ref "U1103") (pin "P$6") (pinfunction "D_P$6") (pintype "passive"))
      (node (ref "U1104") (pin "P$5") (pinfunction "D_P$5") (pintype "passive"))
      (node (ref "U1104") (pin "P$6") (pinfunction "D_P$6") (pintype "passive"))
      (node (ref "U601") (pin "1") (pinfunction "IN_1") (pintype "bidirectional"))
      (node (ref "U602") (pin "1") (pinfunction "IN_1") (pintype "bidirectional"))
      (node (ref "U702") (pin "3") (pinfunction "VIN_3") (pintype "power_in"))
      (node (ref "U703") (pin "A1") (pinfunction "A_A1") (pintype "passive"))
      (node (ref "U703") (pin "A2") (pinfunction "A_A2") (pintype "passive"))
      (node (ref "U703") (pin "A3") (pinfunction "A_A3") (pintype "passive"))
      (node (ref "VDD_5V_IN") (pin "P$1") (pinfunction "P$1_P$1") (pintype "passive"))
    )
    (net (code "239") (name "VDD_5V_PERIPH") (class "Default")
      (node (ref "C618") (pin "P$1") (pinfunction "1_P$1") (pintype "passive"))
      (node (ref "L202") (pin "P$1") (pinfunction "P$1_P$1") (pintype "bidirectional"))
      (node (ref "L203") (pin "P$1") (pinfunction "P$1_P$1") (pintype "bidirectional"))
      (node (ref "L401") (pin "P$1") (pinfunction "P$1_P$1") (pintype "bidirectional"))
      (node (ref "L402") (pin "P$1") (pinfunction "P$1_P$1") (pintype "bidirectional"))
      (node (ref "L403") (pin "P$1") (pinfunction "P$1_P$1") (pintype "bidirectional"))
      (node (ref "L404") (pin "P$1") (pinfunction "P$1_P$1") (pintype "bidirectional"))
      (node (ref "U602") (pin "8") (pinfunction "OUT_8") (pintype "bidirectional"))
    )
    (net (code "240") (name "VDD_5V_SENS") (class "Default")
      (node (ref "R609") (pin "P$1") (pinfunction "1_P$1") (pintype "passive"))
      (node (ref "R610") (pin "P$1") (pinfunction "1_P$1") (pintype "passive"))
      (node (ref "U101") (pin "29") (pinfunction "PA4_29") (pintype "bidirectional"))
    )
    (net (code "241") (name "VDD_SERVO") (class "Default")
      (node (ref "C1102") (pin "P$1") (pinfunction "1_P$1") (pintype "passive"))
      (node (ref "D904") (pin "ANODE") (pinfunction "A_ANODE") (pintype "passive"))
      (node (ref "J901") (pin "11") (pinfunction "S_11") (pintype "passive"))
      (node (ref "J901") (pin "14") (pinfunction "S_14") (pintype "passive"))
      (node (ref "J901") (pin "17") (pinfunction "S_17") (pintype "passive"))
      (node (ref "J901") (pin "20") (pinfunction "S_20") (pintype "passive"))
      (node (ref "J901") (pin "23") (pinfunction "S_23") (pintype "passive"))
      (node (ref "J901") (pin "26") (pinfunction "S_26") (pintype "passive"))
      (node (ref "J901") (pin "29") (pinfunction "S_29") (pintype "passive"))
      (node (ref "J901") (pin "32") (pinfunction "S_32") (pintype "passive"))
      (node (ref "J901") (pin "35") (pinfunction "S_35") (pintype "passive"))
      (node (ref "J901") (pin "38") (pinfunction "S_38") (pintype "passive"))
      (node (ref "J901") (pin "41") (pinfunction "S_41") (pintype "passive"))
      (node (ref "J901") (pin "44") (pinfunction "S_44") (pintype "passive"))
      (node (ref "J901") (pin "47") (pinfunction "S_47") (pintype "passive"))
      (node (ref "J901") (pin "5") (pinfunction "S_5") (pintype "passive"))
      (node (ref "J901") (pin "8") (pinfunction "S_8") (pintype "passive"))
      (node (ref "R1109") (pin "P$1") (pinfunction "1_P$1") (pintype "passive"))
      (node (ref "R922") (pin "P$2") (pinfunction "2_P$2") (pintype "passive"))
      (node (ref "U1101") (pin "P$20") (pinfunction "V2_P$20") (pintype "bidirectional"))
      (node (ref "U1103") (pin "P$7") (pinfunction "D_P$7") (pintype "passive"))
      (node (ref "U1103") (pin "P$8") (pinfunction "D_P$8") (pintype "passive"))
      (node (ref "VDD_SERVO") (pin "P$1") (pinfunction "P$1_P$1") (pintype "passive"))
    )
    (net (code "242") (name "VDD_SERVO_IN") (class "Default")
      (node (ref "L901") (pin "P$2") (pinfunction "P$2_P$2") (pintype "bidirectional"))
      (node (ref "U1001") (pin "1") (pinfunction "IN_1") (pintype "bidirectional"))
    )
    (net (code "243") (name "VDD_SERVO_SENS") (class "Default")
      (node (ref "R918") (pin "P$1") (pinfunction "1_P$1") (pintype "passive"))
      (node (ref "R919") (pin "P$2") (pinfunction "2_P$2") (pintype "passive"))
      (node (ref "U801") (pin "14") (pinfunction "PA4_14") (pintype "bidirectional"))
    )
    (net (code "244") (name "unconnected-(J301-4-PadID)") (class "Default")
      (node (ref "J301") (pin "ID") (pinfunction "4_ID") (pintype "passive"))
    )
    (net (code "245") (name "unconnected-(JX301A-S-Pad10)") (class "Default")
      (node (ref "JX301") (pin "10") (pinfunction "S_10") (pintype "passive"))
    )
    (net (code "246") (name "unconnected-(JX301F-S-Pad8)") (class "Default")
      (node (ref "JX301") (pin "8") (pinfunction "S_8") (pintype "passive"))
    )
    (net (code "247") (name "unconnected-(JX802A-S-Pad10)") (class "Default")
      (node (ref "JX802") (pin "10") (pinfunction "S_10") (pintype "passive"))
    )
    (net (code "248") (name "unconnected-(JX802F-S-Pad8)") (class "Default")
      (node (ref "JX802") (pin "8") (pinfunction "S_8") (pintype "passive"))
    )
    (net (code "249") (name "unconnected-(U101I-PC1-Pad16)") (class "Default")
      (node (ref "U101") (pin "16") (pinfunction "PC1_16") (pintype "bidirectional"))
    )
    (net (code "250") (name "unconnected-(U202-A1-Pad1)") (class "Default")
      (node (ref "U202") (pin "1") (pinfunction "A1_1") (pintype "bidirectional"))
    )
    (net (code "251") (name "unconnected-(U202-A2-Pad3)") (class "Default")
      (node (ref "U202") (pin "3") (pinfunction "A2_3") (pintype "bidirectional"))
    )
    (net (code "252") (name "unconnected-(U202-B1-Pad20)") (class "Default")
      (node (ref "U202") (pin "20") (pinfunction "B1_20") (pintype "bidirectional"))
    )
    (net (code "253") (name "unconnected-(U202-B2-Pad18)") (class "Default")
      (node (ref "U202") (pin "18") (pinfunction "B2_18") (pintype "bidirectional"))
    )
    (net (code "254") (name "unconnected-(U501-INT1-Pad7)") (class "Default")
      (node (ref "U501") (pin "7") (pinfunction "INT1_7") (pintype "output"))
    )
    (net (code "255") (name "unconnected-(U502-DEN-Pad8)") (class "Default")
      (node (ref "U502") (pin "8") (pinfunction "DEN_8") (pintype "bidirectional"))
    )
    (net (code "256") (name "unconnected-(U502-INT1-Pad7)") (class "Default")
      (node (ref "U502") (pin "7") (pinfunction "INT1_7") (pintype "bidirectional"))
    )
    (net (code "257") (name "unconnected-(U505-AUX_CL-Pad7)") (class "Default")
      (node (ref "U505") (pin "7") (pinfunction "AUX_CL_7") (pintype "bidirectional"))
    )
    (net (code "258") (name "unconnected-(U505-AUX_DA-Pad6)") (class "Default")
      (node (ref "U505") (pin "6") (pinfunction "AUX_DA_6") (pintype "bidirectional"))
    )
    (net (code "259") (name "unconnected-(U505-CLKOUT-Pad22)") (class "Default")
      (node (ref "U505") (pin "22") (pinfunction "CLKOUT_22") (pintype "bidirectional"))
    )
    (net (code "260") (name "unconnected-(U505-FSYNC-Pad11)") (class "Default")
      (node (ref "U505") (pin "11") (pinfunction "FSYNC_11") (pintype "bidirectional"))
    )
    (net (code "261") (name "unconnected-(U505-NC1-Pad2)") (class "Default")
      (node (ref "U505") (pin "2") (pinfunction "NC1_2") (pintype "bidirectional"))
    )
    (net (code "262") (name "unconnected-(U505-NC2-Pad3)") (class "Default")
      (node (ref "U505") (pin "3") (pinfunction "NC2_3") (pintype "bidirectional"))
    )
    (net (code "263") (name "unconnected-(U505-NC3-Pad4)") (class "Default")
      (node (ref "U505") (pin "4") (pinfunction "NC3_4") (pintype "bidirectional"))
    )
    (net (code "264") (name "unconnected-(U505-NC4-Pad5)") (class "Default")
      (node (ref "U505") (pin "5") (pinfunction "NC4_5") (pintype "bidirectional"))
    )
    (net (code "265") (name "unconnected-(U505-NC5-Pad14)") (class "Default")
      (node (ref "U505") (pin "14") (pinfunction "NC5_14") (pintype "bidirectional"))
    )
    (net (code "266") (name "unconnected-(U505-NC6-Pad15)") (class "Default")
      (node (ref "U505") (pin "15") (pinfunction "NC6_15") (pintype "bidirectional"))
    )
    (net (code "267") (name "unconnected-(U505-NC7-Pad16)") (class "Default")
      (node (ref "U505") (pin "16") (pinfunction "NC7_16") (pintype "bidirectional"))
    )
    (net (code "268") (name "unconnected-(U505-NC8-Pad17)") (class "Default")
      (node (ref "U505") (pin "17") (pinfunction "NC8_17") (pintype "bidirectional"))
    )
    (net (code "269") (name "unconnected-(U505-RESV1-Pad19)") (class "Default")
      (node (ref "U505") (pin "19") (pinfunction "RESV1_19") (pintype "bidirectional"))
    )
    (net (code "270") (name "unconnected-(U505-RESV2-Pad21)") (class "Default")
      (node (ref "U505") (pin "21") (pinfunction "RESV2_21") (pintype "bidirectional"))
    )
    (net (code "271") (name "unconnected-(U506-CSB1-Pad4)") (class "Default")
      (node (ref "U506") (pin "4") (pinfunction "CSB1_4") (pintype "bidirectional"))
    )
    (net (code "272") (name "unconnected-(U801B-PA11-Pad32)") (class "Default")
      (node (ref "U801") (pin "32") (pinfunction "PA11_32") (pintype "bidirectional"))
    )
    (net (code "273") (name "unconnected-(U801D-PB12-Pad25)") (class "Default")
      (node (ref "U801") (pin "25") (pinfunction "PB12_25") (pintype "bidirectional"))
    )
    (net (code "274") (name "unconnected-(U801E-PB6-Pad42)") (class "Default")
      (node (ref "U801") (pin "42") (pinfunction "PB6_42") (pintype "bidirectional"))
    )
    (net (code "275") (name "unconnected-(U801E-PB7-Pad43)") (class "Default")
      (node (ref "U801") (pin "43") (pinfunction "PB7_43") (pintype "bidirectional"))
    )
    (net (code "276") (name "unconnected-(U801F-PC14-Pad3)") (class "Default")
      (node (ref "U801") (pin "3") (pinfunction "PC14_3") (pintype "bidirectional"))
    )
    (net (code "277") (name "unconnected-(U801F-PC15-Pad4)") (class "Default")
      (node (ref "U801") (pin "4") (pinfunction "PC15_4") (pintype "bidirectional"))
    )
    (net (code "278") (name "unconnected-(U901-A7-Pad8)") (class "Default")
      (node (ref "U901") (pin "8") (pinfunction "A7_8") (pintype "bidirectional"))
    )
    (net (code "279") (name "unconnected-(U901-A8-Pad9)") (class "Default")
      (node (ref "U901") (pin "9") (pinfunction "A8_9") (pintype "bidirectional"))
    )
    (net (code "280") (name "unconnected-(U901-B7-Pad13)") (class "Default")
      (node (ref "U901") (pin "13") (pinfunction "B7_13") (pintype "bidirectional"))
    )
    (net (code "281") (name "unconnected-(U901-B8-Pad12)") (class "Default")
      (node (ref "U901") (pin "12") (pinfunction "B8_12") (pintype "bidirectional"))
    )
    (net (code "282") (name "unconnected-(U1101-CAS-PadP$11)") (class "Default")
      (node (ref "U1101") (pin "P$11") (pinfunction "CAS_P$11") (pintype "bidirectional"))
    )
    (net (code "283") (name "unconnected-(U1101-EN-PadP$22)") (class "Default")
      (node (ref "U1101") (pin "P$22") (pinfunction "EN_P$22") (pintype "bidirectional"))
    )
    (net (code "284") (name "unconnected-(U1101-~{SHDN}-PadP$23)") (class "Default")
      (node (ref "U1101") (pin "P$23") (pinfunction "~{SHDN}_P$23") (pintype "bidirectional"))
    )
    (net (code "285") (name "~{ACCEL_MAG_CS}") (class "Default")
      (node (ref "U101") (pin "9") (pinfunction "PC15_9") (pintype "bidirectional"))
      (node (ref "U504") (pin "8") (pinfunction "CS_8") (pintype "bidirectional"))
      (node (ref "X503") (pin "6") (pinfunction "S_6") (pintype "passive"))
    )
    (net (code "286") (name "~{BARO_CS}") (class "Default")
      (node (ref "U101") (pin "88") (pinfunction "PD7_88") (pintype "bidirectional"))
      (node (ref "U506") (pin "5") (pinfunction "CSB2_5") (pintype "bidirectional"))
    )
    (net (code "287") (name "~{FMU-LED_AMBER}") (class "Default")
      (node (ref "R707") (pin "P$1") (pinfunction "1_P$1") (pintype "passive"))
      (node (ref "U101") (pin "43") (pinfunction "PE12_43") (pintype "bidirectional"))
    )
    (net (code "288") (name "~{FRAM_CS}") (class "Default")
      (node (ref "U101") (pin "57") (pinfunction "PD10_57") (pintype "bidirectional"))
      (node (ref "U102") (pin "1") (pinfunction "~{S}_1") (pintype "bidirectional"))
    )
    (net (code "289") (name "~{GYRO_CS}") (class "Default")
      (node (ref "U101") (pin "7") (pinfunction "PC13_7") (pintype "bidirectional"))
      (node (ref "U501") (pin "5") (pinfunction "CS_5") (pintype "input"))
      (node (ref "U502") (pin "5") (pinfunction "CS_5") (pintype "bidirectional"))
      (node (ref "X503") (pin "7") (pinfunction "S_7") (pintype "passive"))
    )
    (net (code "290") (name "~{IO-LED_AMBER}") (class "Default")
      (node (ref "R709") (pin "P$1") (pinfunction "1_P$1") (pintype "passive"))
      (node (ref "U801") (pin "28") (pinfunction "PB15_28") (pintype "bidirectional"))
    )
    (net (code "291") (name "~{IO-LED_BLUE}") (class "Default")
      (node (ref "R712") (pin "P$1") (pinfunction "1_P$1") (pintype "passive"))
      (node (ref "U801") (pin "27") (pinfunction "PB14_27") (pintype "bidirectional"))
    )
    (net (code "292") (name "~{IO-LED_SAFETY}") (class "Default")
      (node (ref "R710") (pin "P$2") (pinfunction "2_P$2") (pintype "passive"))
      (node (ref "U801") (pin "26") (pinfunction "PB13_26") (pintype "bidirectional"))
    )
    (net (code "293") (name "~{MPU_CS}") (class "Default")
      (node (ref "U101") (pin "17") (pinfunction "PC2_17") (pintype "bidirectional"))
      (node (ref "U505") (pin "8") (pinfunction "/CS_8") (pintype "bidirectional"))
    )
    (net (code "294") (name "~{SBUS_OUTPUT_EN}") (class "Default")
      (node (ref "U801") (pin "40") (pinfunction "PB4_40") (pintype "bidirectional"))
      (node (ref "U903") (pin "7") (pinfunction "~{2OE}_7") (pintype "input"))
    )
    (net (code "295") (name "~{SPI_EXT_NSS}") (class "Default")
      (node (ref "J403") (pin "5") (pinfunction "5_5") (pintype "passive"))
      (node (ref "U101") (pin "3") (pinfunction "PE4_3") (pintype "bidirectional"))
    )
    (net (code "296") (name "~{VBUS_VALID}") (class "Default")
      (node (ref "!VBUS_VALID") (pin "P$1") (pinfunction "P$1_P$1") (pintype "passive"))
      (node (ref "RN1101") (pin "2") (pinfunction "1_2") (pintype "passive"))
      (node (ref "U101") (pin "15") (pinfunction "PC0_15") (pintype "bidirectional"))
      (node (ref "U1101") (pin "P$9") (pinfunction "~{VALID3}_P$9") (pintype "bidirectional"))
    )
    (net (code "297") (name "~{VDD_5V_HIPOWER_OC}") (class "Default")
      (node (ref "R602") (pin "P$1") (pinfunction "1_P$1") (pintype "passive"))
      (node (ref "U101") (pin "41") (pinfunction "PE10_41") (pintype "bidirectional"))
      (node (ref "U601") (pin "4") (pinfunction "~{FAULT}_4") (pintype "bidirectional"))
    )
    (net (code "298") (name "~{VDD_5V_PERIPH_EN}") (class "Default")
      (node (ref "R615") (pin "P$1") (pinfunction "1_P$1") (pintype "passive"))
      (node (ref "U101") (pin "67") (pinfunction "PA8_67") (pintype "bidirectional"))
      (node (ref "U601") (pin "5") (pinfunction "~{CE}_5") (pintype "bidirectional"))
      (node (ref "U602") (pin "5") (pinfunction "~{CE}_5") (pintype "bidirectional"))
    )
    (net (code "299") (name "~{VDD_5V_PERIPH_OC}") (class "Default")
      (node (ref "R604") (pin "P$1") (pinfunction "1_P$1") (pintype "passive"))
      (node (ref "U101") (pin "46") (pinfunction "PE15_46") (pintype "bidirectional"))
      (node (ref "U602") (pin "4") (pinfunction "~{FAULT}_4") (pintype "bidirectional"))
    )
    (net (code "300") (name "~{VDD_BRICK_VALID}") (class "Default")
      (node (ref "!VDD_BRICK_VALID") (pin "P$1") (pinfunction "P$1_P$1") (pintype "passive"))
      (node (ref "RN1101") (pin "4") (pinfunction "1_4") (pintype "passive"))
      (node (ref "U101") (pin "91") (pinfunction "PB5_91") (pintype "bidirectional"))
      (node (ref "U1101") (pin "P$7") (pinfunction "~{VALID1}_P$7") (pintype "bidirectional"))
    )
    (net (code "301") (name "~{VDD_SERVO_VALID}") (class "Default")
      (node (ref "!VDD_SERVO_VALID") (pin "P$1") (pinfunction "P$1_P$1") (pintype "passive"))
      (node (ref "RN1101") (pin "3") (pinfunction "1_3") (pintype "passive"))
      (node (ref "U101") (pin "93") (pinfunction "PB7_93") (pintype "bidirectional"))
      (node (ref "U1101") (pin "P$8") (pinfunction "~{VALID2}_P$8") (pintype "bidirectional"))
    )
  )
)
